# bornhack_stoplicht_ws2812_smd_405_cap_r1.net
KiCad netlist of a schematic drawn in EAGLE
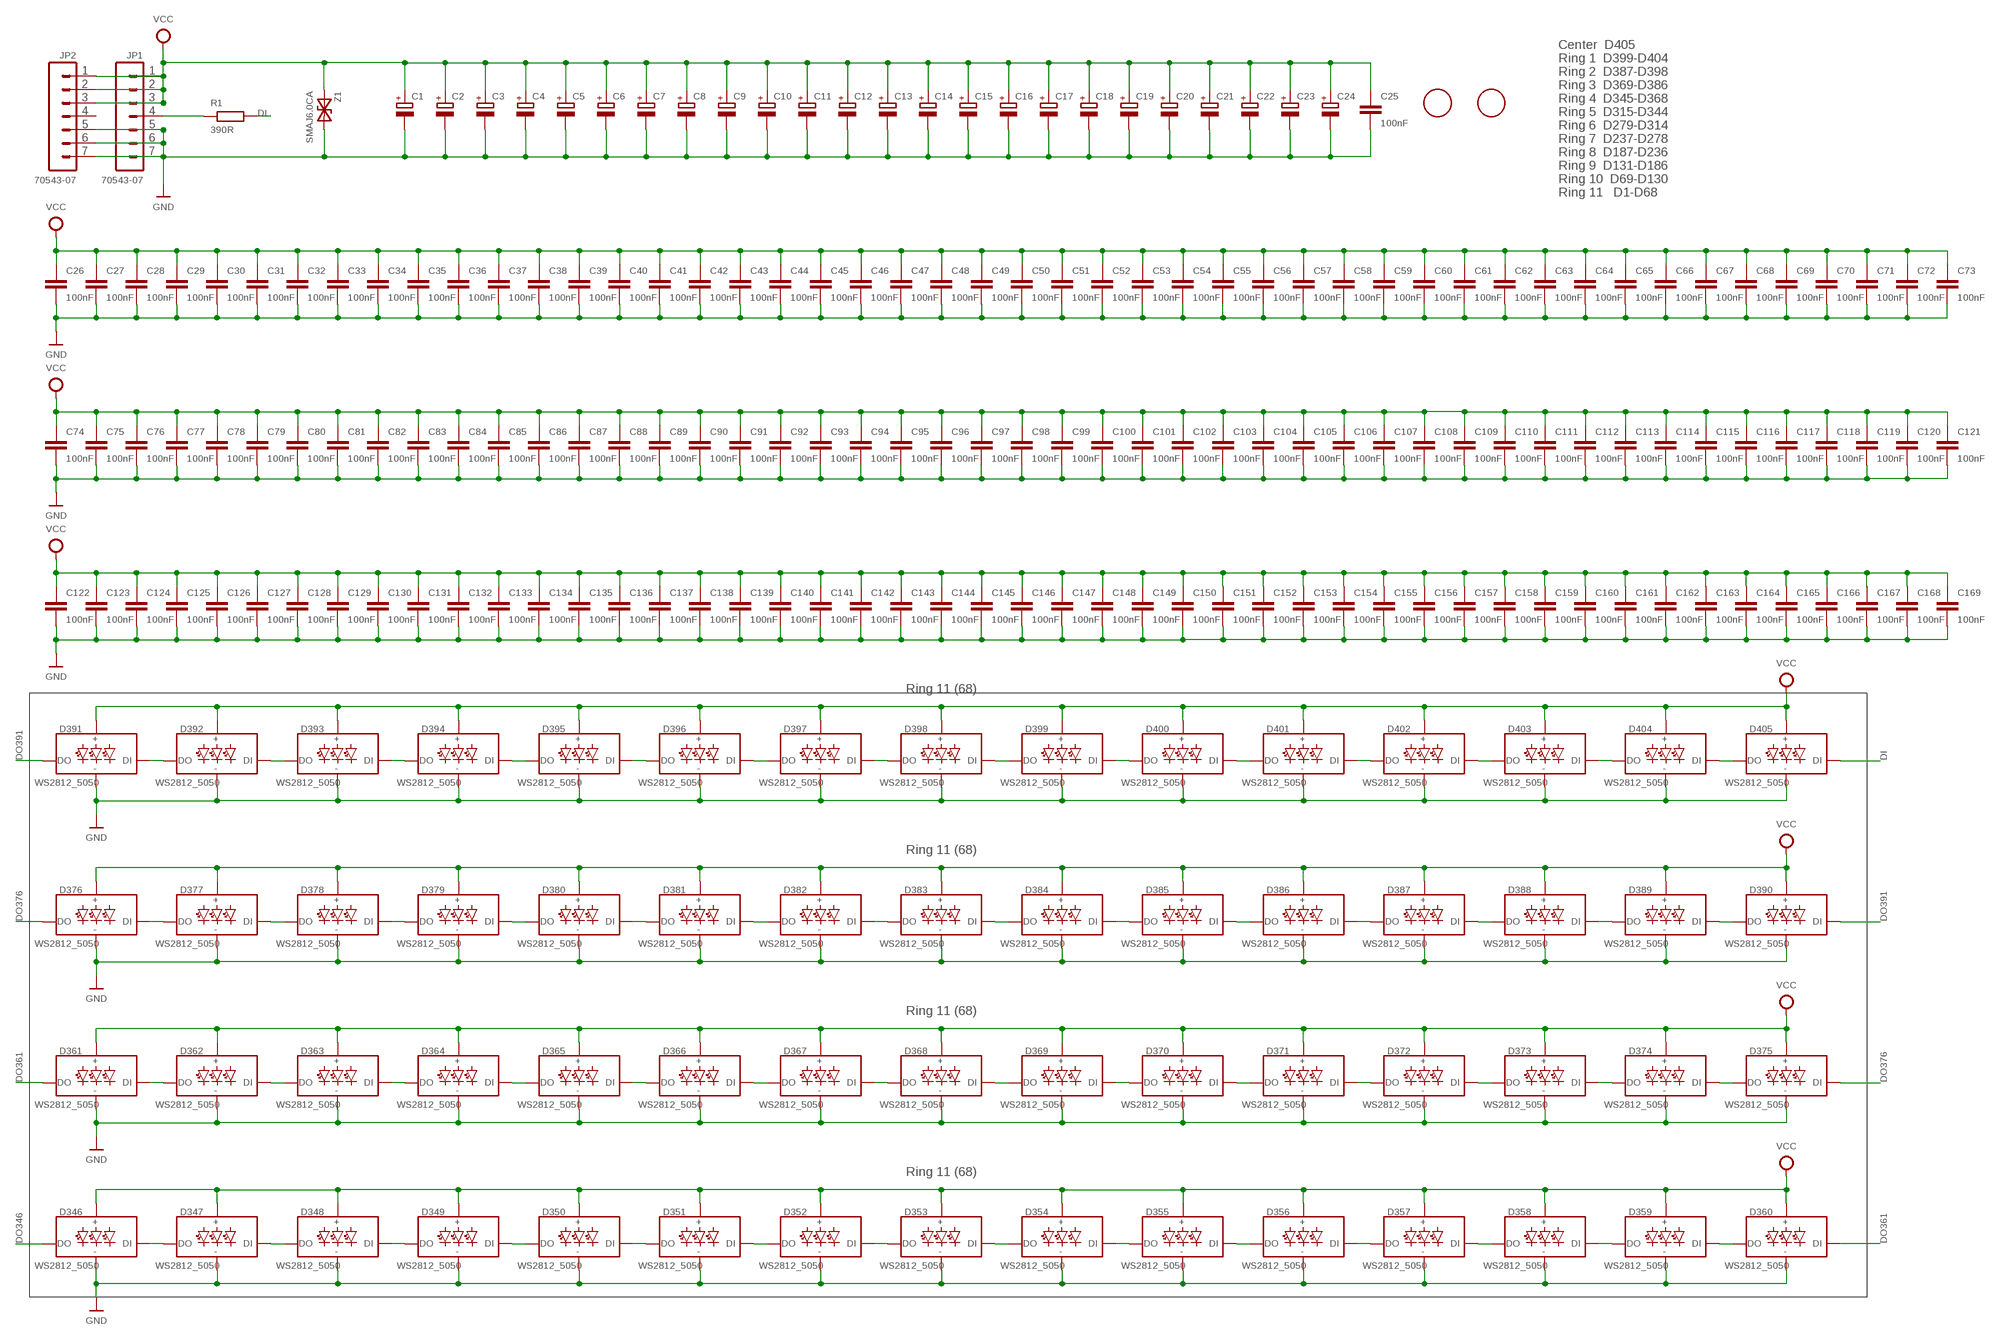
[diagram p0: schematic, sheet 1]
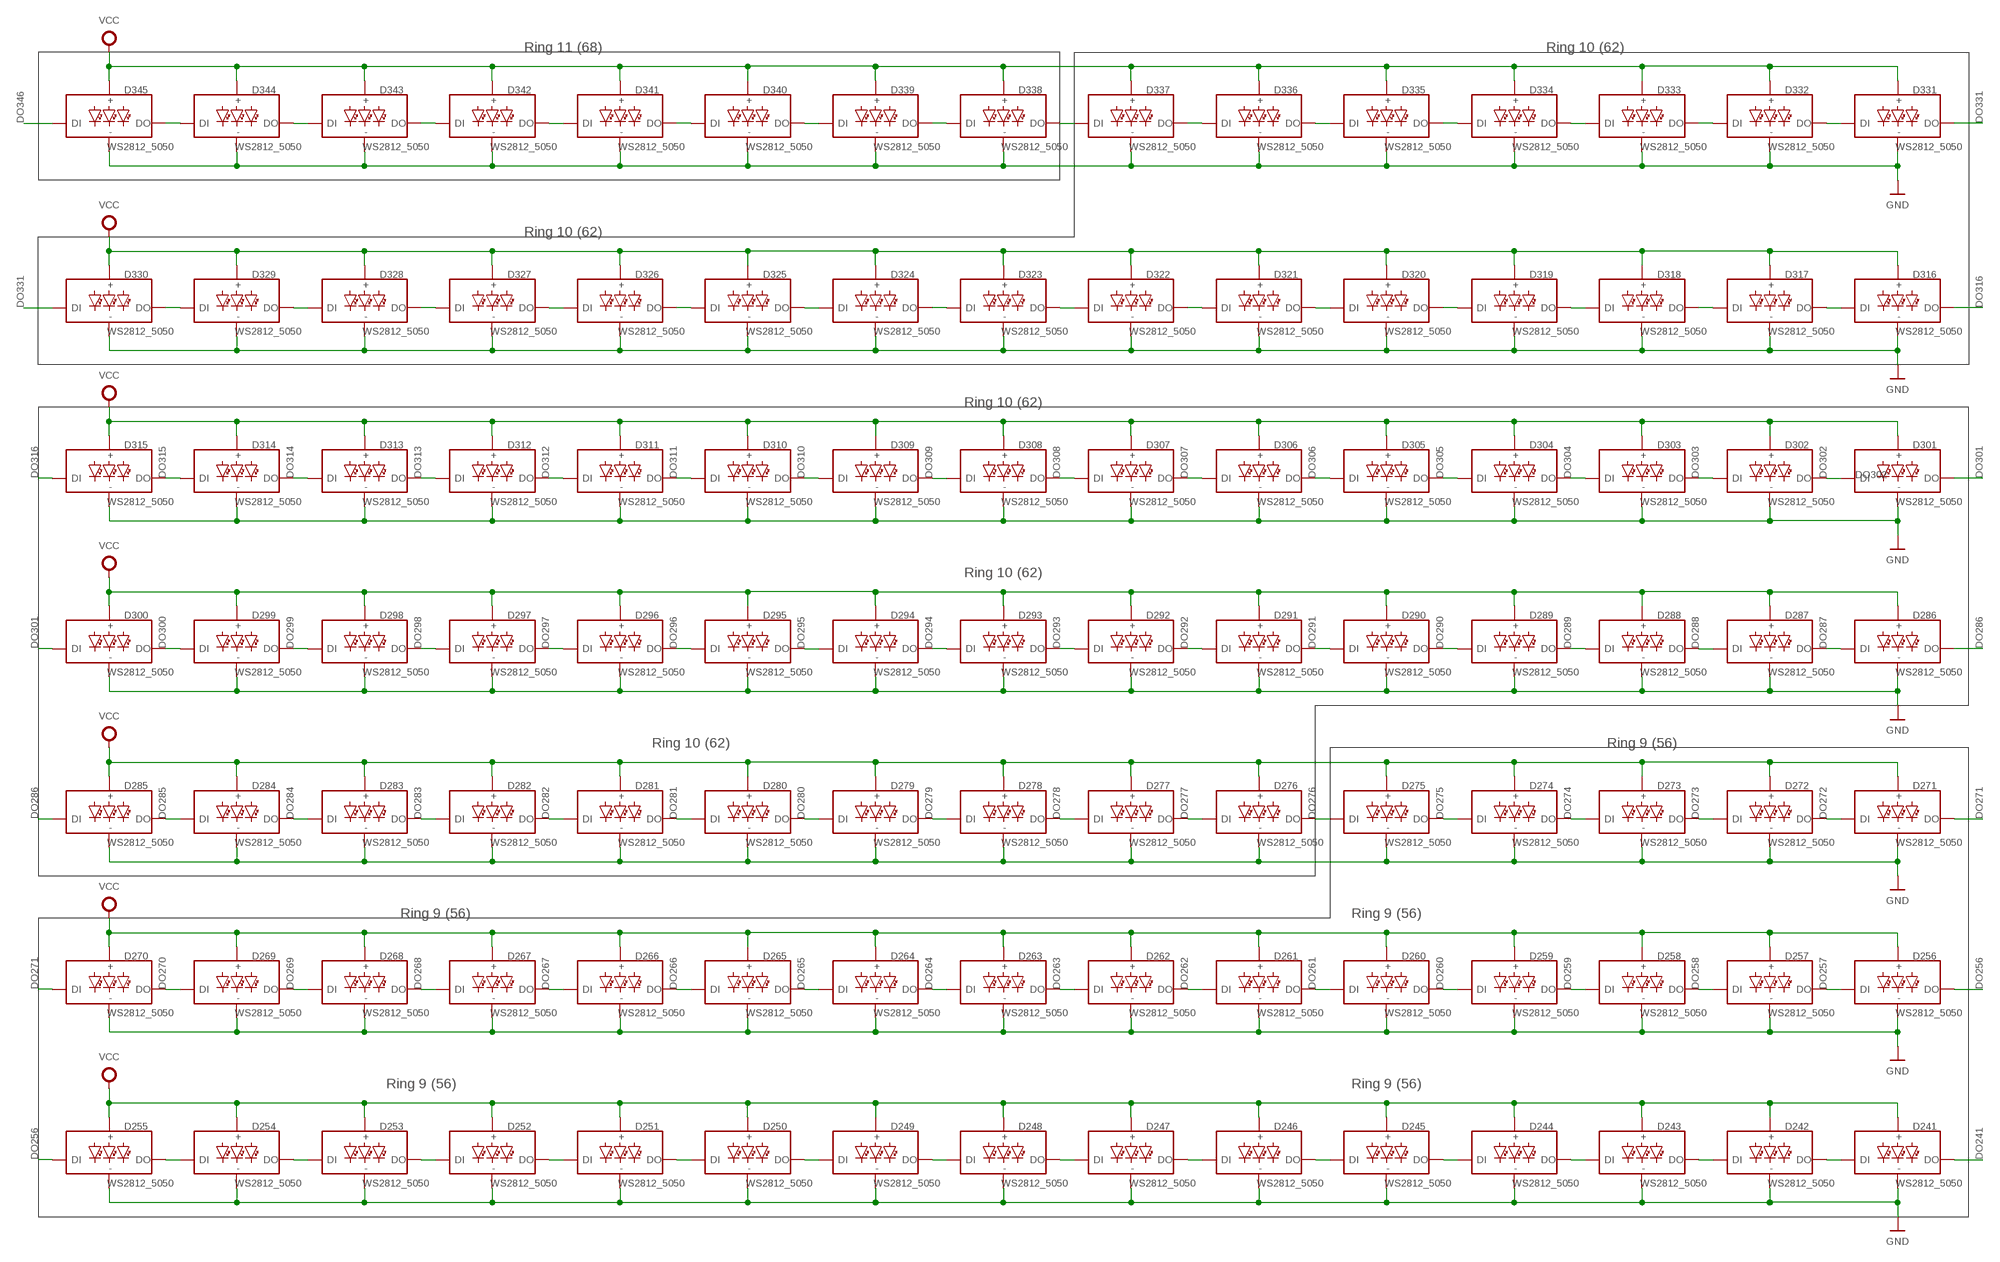
[diagram p1: schematic, sheet 2]
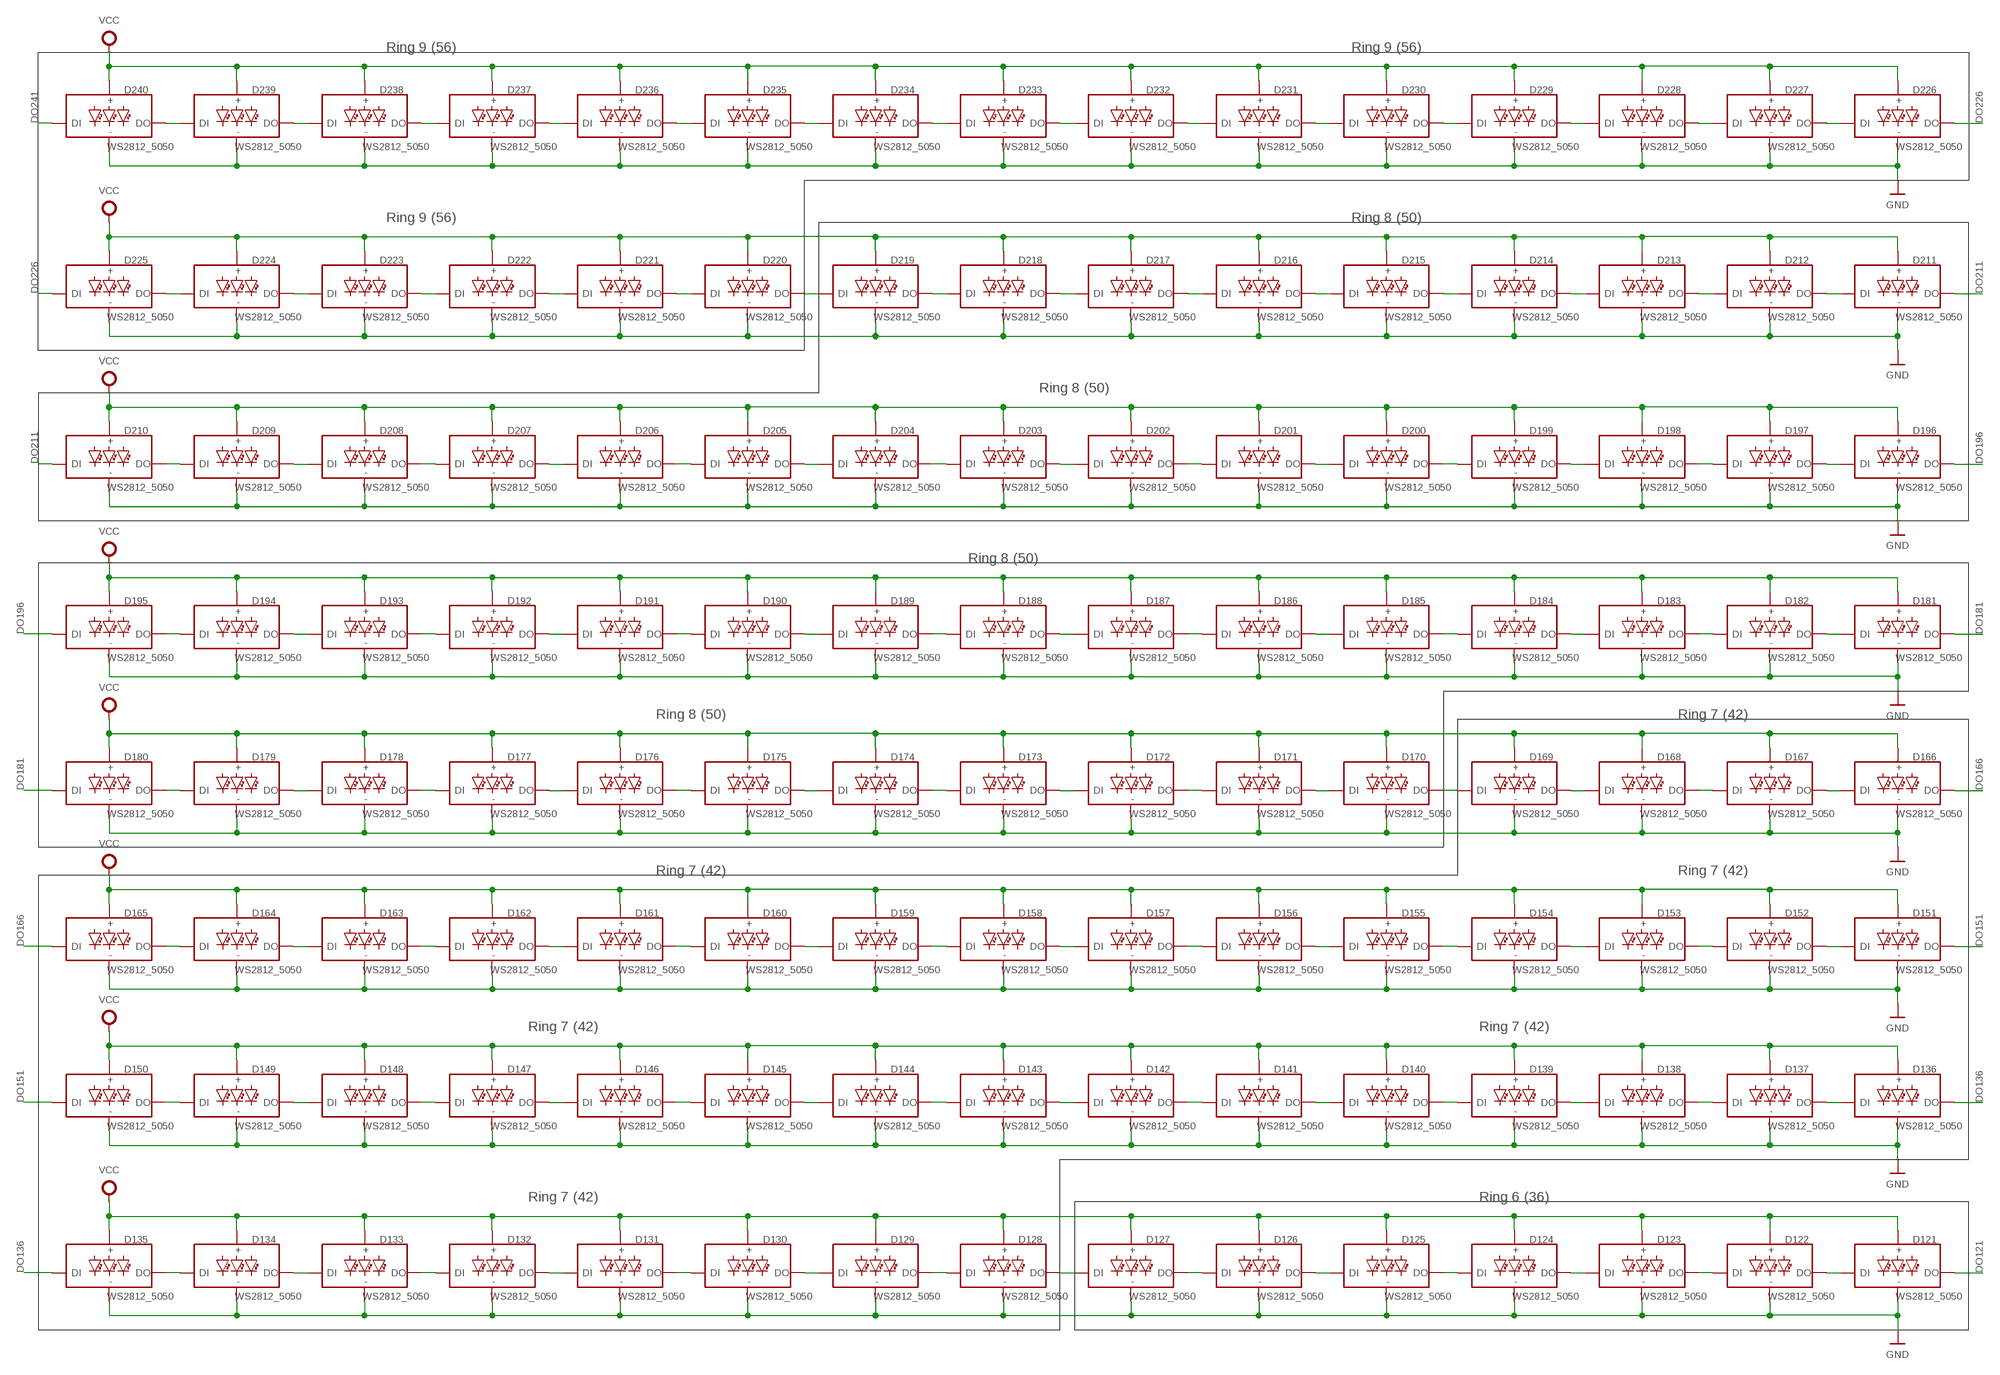
[diagram p2: schematic, sheet 3]
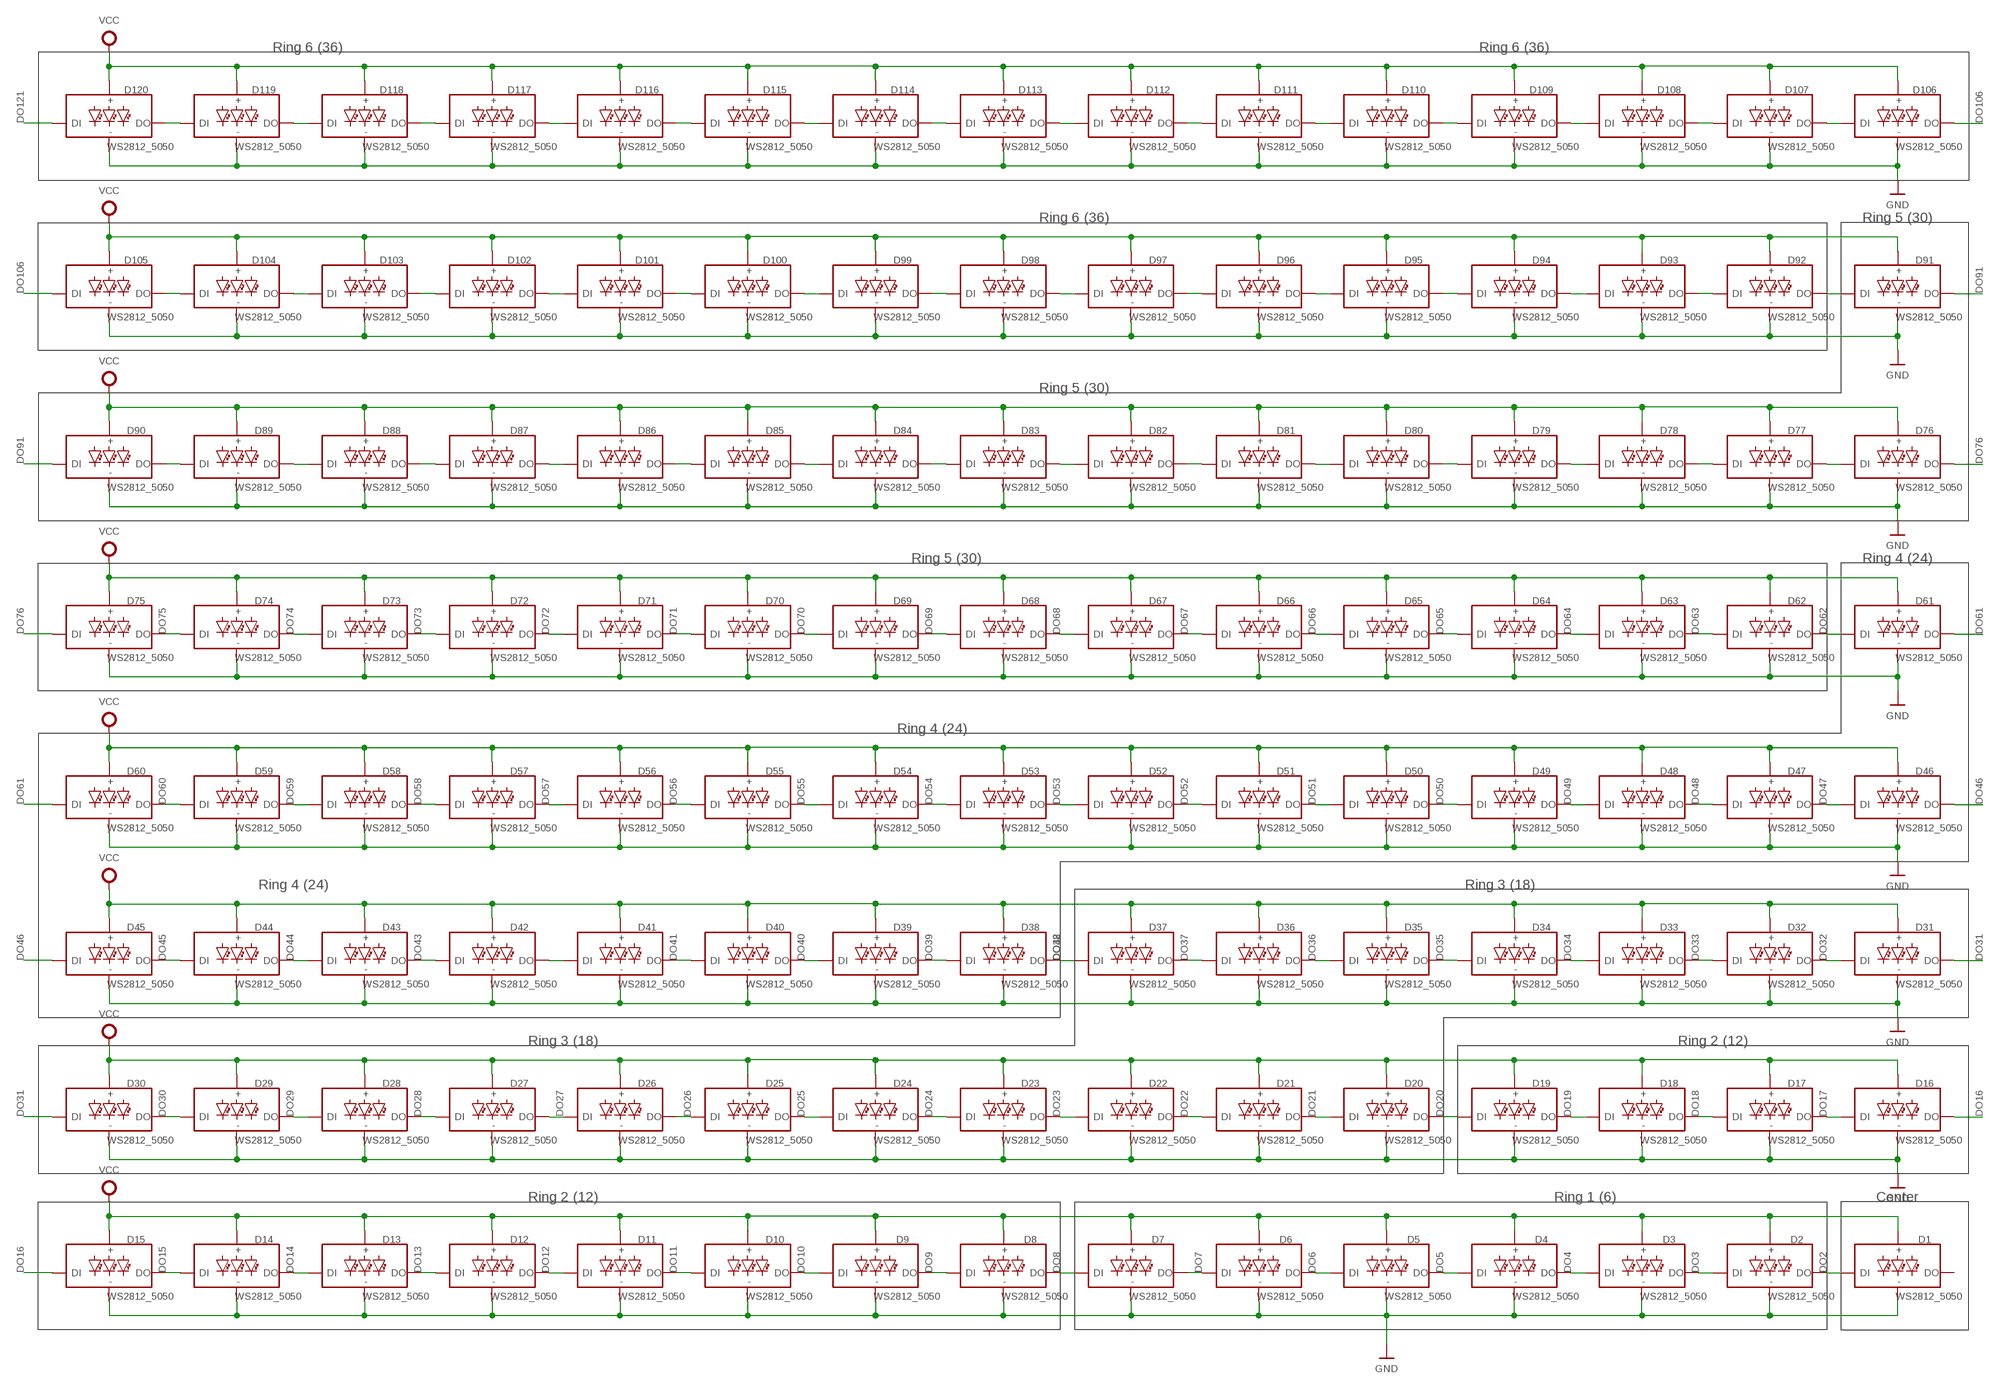
[diagram p3: schematic, sheet 4]

(export (version "E")
  (design (tool "Eeschema 10.0.6"))
  (components
    (comp (ref "C1")
      (value "CPOL-EUE2.5-6")
      (footprint "eagle-import:E2,5-6")
      (libsource (lib "eagle-import") (part "CPOL-EUE2.5-6"))
    )
    (comp (ref "C2")
      (value "CPOL-EUE2.5-6")
      (footprint "eagle-import:E2,5-6")
      (libsource (lib "eagle-import") (part "CPOL-EUE2.5-6"))
    )
    (comp (ref "C3")
      (value "CPOL-EUE2.5-6")
      (footprint "eagle-import:E2,5-6")
      (libsource (lib "eagle-import") (part "CPOL-EUE2.5-6"))
    )
    (comp (ref "C4")
      (value "CPOL-EUE2.5-6")
      (footprint "eagle-import:E2,5-6")
      (libsource (lib "eagle-import") (part "CPOL-EUE2.5-6"))
    )
    (comp (ref "C5")
      (value "CPOL-EUE2.5-6")
      (footprint "eagle-import:E2,5-6")
      (libsource (lib "eagle-import") (part "CPOL-EUE2.5-6"))
    )
    (comp (ref "C6")
      (value "CPOL-EUE2.5-6")
      (footprint "eagle-import:E2,5-6")
      (libsource (lib "eagle-import") (part "CPOL-EUE2.5-6"))
    )
    (comp (ref "C7")
      (value "CPOL-EUE2.5-6")
      (footprint "eagle-import:E2,5-6")
      (libsource (lib "eagle-import") (part "CPOL-EUE2.5-6"))
    )
    (comp (ref "C8")
      (value "CPOL-EUE2.5-6")
      (footprint "eagle-import:E2,5-6")
      (libsource (lib "eagle-import") (part "CPOL-EUE2.5-6"))
    )
    (comp (ref "C9")
      (value "CPOL-EUE2.5-6")
      (footprint "eagle-import:E2,5-6")
      (libsource (lib "eagle-import") (part "CPOL-EUE2.5-6"))
    )
    (comp (ref "C10")
      (value "CPOL-EUE2.5-6")
      (footprint "eagle-import:E2,5-6")
      (libsource (lib "eagle-import") (part "CPOL-EUE2.5-6"))
    )
    (comp (ref "C11")
      (value "CPOL-EUE2.5-6")
      (footprint "eagle-import:E2,5-6")
      (libsource (lib "eagle-import") (part "CPOL-EUE2.5-6"))
    )
    (comp (ref "C12")
      (value "CPOL-EUE2.5-6")
      (footprint "eagle-import:E2,5-6")
      (libsource (lib "eagle-import") (part "CPOL-EUE2.5-6"))
    )
    (comp (ref "C13")
      (value "CPOL-EUE2.5-6")
      (footprint "eagle-import:E2,5-6")
      (libsource (lib "eagle-import") (part "CPOL-EUE2.5-6"))
    )
    (comp (ref "C14")
      (value "CPOL-EUE2.5-6")
      (footprint "eagle-import:E2,5-6")
      (libsource (lib "eagle-import") (part "CPOL-EUE2.5-6"))
    )
    (comp (ref "C15")
      (value "CPOL-EUE2.5-6")
      (footprint "eagle-import:E2,5-6")
      (libsource (lib "eagle-import") (part "CPOL-EUE2.5-6"))
    )
    (comp (ref "C16")
      (value "CPOL-EUE2.5-6")
      (footprint "eagle-import:E2,5-6")
      (libsource (lib "eagle-import") (part "CPOL-EUE2.5-6"))
    )
    (comp (ref "C17")
      (value "CPOL-EUE2.5-6")
      (footprint "eagle-import:E2,5-6")
      (libsource (lib "eagle-import") (part "CPOL-EUE2.5-6"))
    )
    (comp (ref "C18")
      (value "CPOL-EUE2.5-6")
      (footprint "eagle-import:E2,5-6")
      (libsource (lib "eagle-import") (part "CPOL-EUE2.5-6"))
    )
    (comp (ref "C19")
      (value "CPOL-EUE2.5-6")
      (footprint "eagle-import:E2,5-6")
      (libsource (lib "eagle-import") (part "CPOL-EUE2.5-6"))
    )
    (comp (ref "C20")
      (value "CPOL-EUE2.5-6")
      (footprint "eagle-import:E2,5-6")
      (libsource (lib "eagle-import") (part "CPOL-EUE2.5-6"))
    )
    (comp (ref "C21")
      (value "CPOL-EUE2.5-6")
      (footprint "eagle-import:E2,5-6")
      (libsource (lib "eagle-import") (part "CPOL-EUE2.5-6"))
    )
    (comp (ref "C22")
      (value "CPOL-EUE2.5-6")
      (footprint "eagle-import:E2,5-6")
      (libsource (lib "eagle-import") (part "CPOL-EUE2.5-6"))
    )
    (comp (ref "C23")
      (value "CPOL-EUE2.5-6")
      (footprint "eagle-import:E2,5-6")
      (libsource (lib "eagle-import") (part "CPOL-EUE2.5-6"))
    )
    (comp (ref "C24")
      (value "CPOL-EUE2.5-6")
      (footprint "eagle-import:E2,5-6")
      (libsource (lib "eagle-import") (part "CPOL-EUE2.5-6"))
    )
    (comp (ref "C25")
      (value "100nF")
      (footprint "eagle-import:C0603K")
      (libsource (lib "eagle-import") (part "C-EUC0603K"))
    )
    (comp (ref "C26")
      (value "100nF")
      (footprint "eagle-import:C0603K")
      (libsource (lib "eagle-import") (part "C-EUC0603K"))
    )
    (comp (ref "C27")
      (value "100nF")
      (footprint "eagle-import:C0603K")
      (libsource (lib "eagle-import") (part "C-EUC0603K"))
    )
    (comp (ref "C28")
      (value "100nF")
      (footprint "eagle-import:C0603K")
      (libsource (lib "eagle-import") (part "C-EUC0603K"))
    )
    (comp (ref "C29")
      (value "100nF")
      (footprint "eagle-import:C0603K")
      (libsource (lib "eagle-import") (part "C-EUC0603K"))
    )
    (comp (ref "C30")
      (value "100nF")
      (footprint "eagle-import:C0603K")
      (libsource (lib "eagle-import") (part "C-EUC0603K"))
    )
    (comp (ref "C31")
      (value "100nF")
      (footprint "eagle-import:C0603K")
      (libsource (lib "eagle-import") (part "C-EUC0603K"))
    )
    (comp (ref "C32")
      (value "100nF")
      (footprint "eagle-import:C0603K")
      (libsource (lib "eagle-import") (part "C-EUC0603K"))
    )
    (comp (ref "C33")
      (value "100nF")
      (footprint "eagle-import:C0603K")
      (libsource (lib "eagle-import") (part "C-EUC0603K"))
    )
    (comp (ref "C34")
      (value "100nF")
      (footprint "eagle-import:C0603K")
      (libsource (lib "eagle-import") (part "C-EUC0603K"))
    )
    (comp (ref "C35")
      (value "100nF")
      (footprint "eagle-import:C0603K")
      (libsource (lib "eagle-import") (part "C-EUC0603K"))
    )
    (comp (ref "C36")
      (value "100nF")
      (footprint "eagle-import:C0603K")
      (libsource (lib "eagle-import") (part "C-EUC0603K"))
    )
    (comp (ref "C37")
      (value "100nF")
      (footprint "eagle-import:C0603K")
      (libsource (lib "eagle-import") (part "C-EUC0603K"))
    )
    (comp (ref "C38")
      (value "100nF")
      (footprint "eagle-import:C0603K")
      (libsource (lib "eagle-import") (part "C-EUC0603K"))
    )
    (comp (ref "C39")
      (value "100nF")
      (footprint "eagle-import:C0603K")
      (libsource (lib "eagle-import") (part "C-EUC0603K"))
    )
    (comp (ref "C40")
      (value "100nF")
      (footprint "eagle-import:C0603K")
      (libsource (lib "eagle-import") (part "C-EUC0603K"))
    )
    (comp (ref "C41")
      (value "100nF")
      (footprint "eagle-import:C0603K")
      (libsource (lib "eagle-import") (part "C-EUC0603K"))
    )
    (comp (ref "C42")
      (value "100nF")
      (footprint "eagle-import:C0603K")
      (libsource (lib "eagle-import") (part "C-EUC0603K"))
    )
    (comp (ref "C43")
      (value "100nF")
      (footprint "eagle-import:C0603K")
      (libsource (lib "eagle-import") (part "C-EUC0603K"))
    )
    (comp (ref "C44")
      (value "100nF")
      (footprint "eagle-import:C0603K")
      (libsource (lib "eagle-import") (part "C-EUC0603K"))
    )
    (comp (ref "C45")
      (value "100nF")
      (footprint "eagle-import:C0603K")
      (libsource (lib "eagle-import") (part "C-EUC0603K"))
    )
    (comp (ref "C46")
      (value "100nF")
      (footprint "eagle-import:C0603K")
      (libsource (lib "eagle-import") (part "C-EUC0603K"))
    )
    (comp (ref "C47")
      (value "100nF")
      (footprint "eagle-import:C0603K")
      (libsource (lib "eagle-import") (part "C-EUC0603K"))
    )
    (comp (ref "C48")
      (value "100nF")
      (footprint "eagle-import:C0603K")
      (libsource (lib "eagle-import") (part "C-EUC0603K"))
    )
    (comp (ref "C49")
      (value "100nF")
      (footprint "eagle-import:C0603K")
      (libsource (lib "eagle-import") (part "C-EUC0603K"))
    )
    (comp (ref "C50")
      (value "100nF")
      (footprint "eagle-import:C0603K")
      (libsource (lib "eagle-import") (part "C-EUC0603K"))
    )
    (comp (ref "C51")
      (value "100nF")
      (footprint "eagle-import:C0603K")
      (libsource (lib "eagle-import") (part "C-EUC0603K"))
    )
    (comp (ref "C52")
      (value "100nF")
      (footprint "eagle-import:C0603K")
      (libsource (lib "eagle-import") (part "C-EUC0603K"))
    )
    (comp (ref "C53")
      (value "100nF")
      (footprint "eagle-import:C0603K")
      (libsource (lib "eagle-import") (part "C-EUC0603K"))
    )
    (comp (ref "C54")
      (value "100nF")
      (footprint "eagle-import:C0603K")
      (libsource (lib "eagle-import") (part "C-EUC0603K"))
    )
    (comp (ref "C55")
      (value "100nF")
      (footprint "eagle-import:C0603K")
      (libsource (lib "eagle-import") (part "C-EUC0603K"))
    )
    (comp (ref "C56")
      (value "100nF")
      (footprint "eagle-import:C0603K")
      (libsource (lib "eagle-import") (part "C-EUC0603K"))
    )
    (comp (ref "C57")
      (value "100nF")
      (footprint "eagle-import:C0603K")
      (libsource (lib "eagle-import") (part "C-EUC0603K"))
    )
    (comp (ref "C58")
      (value "100nF")
      (footprint "eagle-import:C0603K")
      (libsource (lib "eagle-import") (part "C-EUC0603K"))
    )
    (comp (ref "C59")
      (value "100nF")
      (footprint "eagle-import:C0603K")
      (libsource (lib "eagle-import") (part "C-EUC0603K"))
    )
    (comp (ref "C60")
      (value "100nF")
      (footprint "eagle-import:C0603K")
      (libsource (lib "eagle-import") (part "C-EUC0603K"))
    )
    (comp (ref "C61")
      (value "100nF")
      (footprint "eagle-import:C0603K")
      (libsource (lib "eagle-import") (part "C-EUC0603K"))
    )
    (comp (ref "C62")
      (value "100nF")
      (footprint "eagle-import:C0603K")
      (libsource (lib "eagle-import") (part "C-EUC0603K"))
    )
    (comp (ref "C63")
      (value "100nF")
      (footprint "eagle-import:C0603K")
      (libsource (lib "eagle-import") (part "C-EUC0603K"))
    )
    (comp (ref "C64")
      (value "100nF")
      (footprint "eagle-import:C0603K")
      (libsource (lib "eagle-import") (part "C-EUC0603K"))
    )
    (comp (ref "C65")
      (value "100nF")
      (footprint "eagle-import:C0603K")
      (libsource (lib "eagle-import") (part "C-EUC0603K"))
    )
    (comp (ref "C66")
      (value "100nF")
      (footprint "eagle-import:C0603K")
      (libsource (lib "eagle-import") (part "C-EUC0603K"))
    )
    (comp (ref "C67")
      (value "100nF")
      (footprint "eagle-import:C0603K")
      (libsource (lib "eagle-import") (part "C-EUC0603K"))
    )
    (comp (ref "C68")
      (value "100nF")
      (footprint "eagle-import:C0603K")
      (libsource (lib "eagle-import") (part "C-EUC0603K"))
    )
    (comp (ref "C69")
      (value "100nF")
      (footprint "eagle-import:C0603K")
      (libsource (lib "eagle-import") (part "C-EUC0603K"))
    )
    (comp (ref "C70")
      (value "100nF")
      (footprint "eagle-import:C0603K")
      (libsource (lib "eagle-import") (part "C-EUC0603K"))
    )
    (comp (ref "C71")
      (value "100nF")
      (footprint "eagle-import:C0603K")
      (libsource (lib "eagle-import") (part "C-EUC0603K"))
    )
    (comp (ref "C72")
      (value "100nF")
      (footprint "eagle-import:C0603K")
      (libsource (lib "eagle-import") (part "C-EUC0603K"))
    )
    (comp (ref "C73")
      (value "100nF")
      (footprint "eagle-import:C0603K")
      (libsource (lib "eagle-import") (part "C-EUC0603K"))
    )
    (comp (ref "C74")
      (value "100nF")
      (footprint "eagle-import:C0603K")
      (libsource (lib "eagle-import") (part "C-EUC0603K"))
    )
    (comp (ref "C75")
      (value "100nF")
      (footprint "eagle-import:C0603K")
      (libsource (lib "eagle-import") (part "C-EUC0603K"))
    )
    (comp (ref "C76")
      (value "100nF")
      (footprint "eagle-import:C0603K")
      (libsource (lib "eagle-import") (part "C-EUC0603K"))
    )
    (comp (ref "C77")
      (value "100nF")
      (footprint "eagle-import:C0603K")
      (libsource (lib "eagle-import") (part "C-EUC0603K"))
    )
    (comp (ref "C78")
      (value "100nF")
      (footprint "eagle-import:C0603K")
      (libsource (lib "eagle-import") (part "C-EUC0603K"))
    )
    (comp (ref "C79")
      (value "100nF")
      (footprint "eagle-import:C0603K")
      (libsource (lib "eagle-import") (part "C-EUC0603K"))
    )
    (comp (ref "C80")
      (value "100nF")
      (footprint "eagle-import:C0603K")
      (libsource (lib "eagle-import") (part "C-EUC0603K"))
    )
    (comp (ref "C81")
      (value "100nF")
      (footprint "eagle-import:C0603K")
      (libsource (lib "eagle-import") (part "C-EUC0603K"))
    )
    (comp (ref "C82")
      (value "100nF")
      (footprint "eagle-import:C0603K")
      (libsource (lib "eagle-import") (part "C-EUC0603K"))
    )
    (comp (ref "C83")
      (value "100nF")
      (footprint "eagle-import:C0603K")
      (libsource (lib "eagle-import") (part "C-EUC0603K"))
    )
    (comp (ref "C84")
      (value "100nF")
      (footprint "eagle-import:C0603K")
      (libsource (lib "eagle-import") (part "C-EUC0603K"))
    )
    (comp (ref "C85")
      (value "100nF")
      (footprint "eagle-import:C0603K")
      (libsource (lib "eagle-import") (part "C-EUC0603K"))
    )
    (comp (ref "C86")
      (value "100nF")
      (footprint "eagle-import:C0603K")
      (libsource (lib "eagle-import") (part "C-EUC0603K"))
    )
    (comp (ref "C87")
      (value "100nF")
      (footprint "eagle-import:C0603K")
      (libsource (lib "eagle-import") (part "C-EUC0603K"))
    )
    (comp (ref "C88")
      (value "100nF")
      (footprint "eagle-import:C0603K")
      (libsource (lib "eagle-import") (part "C-EUC0603K"))
    )
    (comp (ref "C89")
      (value "100nF")
      (footprint "eagle-import:C0603K")
      (libsource (lib "eagle-import") (part "C-EUC0603K"))
    )
    (comp (ref "C90")
      (value "100nF")
      (footprint "eagle-import:C0603K")
      (libsource (lib "eagle-import") (part "C-EUC0603K"))
    )
    (comp (ref "C91")
      (value "100nF")
      (footprint "eagle-import:C0603K")
      (libsource (lib "eagle-import") (part "C-EUC0603K"))
    )
    (comp (ref "C92")
      (value "100nF")
      (footprint "eagle-import:C0603K")
      (libsource (lib "eagle-import") (part "C-EUC0603K"))
    )
    (comp (ref "C93")
      (value "100nF")
      (footprint "eagle-import:C0603K")
      (libsource (lib "eagle-import") (part "C-EUC0603K"))
    )
    (comp (ref "C94")
      (value "100nF")
      (footprint "eagle-import:C0603K")
      (libsource (lib "eagle-import") (part "C-EUC0603K"))
    )
    (comp (ref "C95")
      (value "100nF")
      (footprint "eagle-import:C0603K")
      (libsource (lib "eagle-import") (part "C-EUC0603K"))
    )
    (comp (ref "C96")
      (value "100nF")
      (footprint "eagle-import:C0603K")
      (libsource (lib "eagle-import") (part "C-EUC0603K"))
    )
    (comp (ref "C97")
      (value "100nF")
      (footprint "eagle-import:C0603K")
      (libsource (lib "eagle-import") (part "C-EUC0603K"))
    )
    (comp (ref "C98")
      (value "100nF")
      (footprint "eagle-import:C0603K")
      (libsource (lib "eagle-import") (part "C-EUC0603K"))
    )
    (comp (ref "C99")
      (value "100nF")
      (footprint "eagle-import:C0603K")
      (libsource (lib "eagle-import") (part "C-EUC0603K"))
    )
    (comp (ref "C100")
      (value "100nF")
      (footprint "eagle-import:C0603K")
      (libsource (lib "eagle-import") (part "C-EUC0603K"))
    )
    (comp (ref "C101")
      (value "100nF")
      (footprint "eagle-import:C0603K")
      (libsource (lib "eagle-import") (part "C-EUC0603K"))
    )
    (comp (ref "C102")
      (value "100nF")
      (footprint "eagle-import:C0603K")
      (libsource (lib "eagle-import") (part "C-EUC0603K"))
    )
    (comp (ref "C103")
      (value "100nF")
      (footprint "eagle-import:C0603K")
      (libsource (lib "eagle-import") (part "C-EUC0603K"))
    )
    (comp (ref "C104")
      (value "100nF")
      (footprint "eagle-import:C0603K")
      (libsource (lib "eagle-import") (part "C-EUC0603K"))
    )
    (comp (ref "C105")
      (value "100nF")
      (footprint "eagle-import:C0603K")
      (libsource (lib "eagle-import") (part "C-EUC0603K"))
    )
    (comp (ref "C106")
      (value "100nF")
      (footprint "eagle-import:C0603K")
      (libsource (lib "eagle-import") (part "C-EUC0603K"))
    )
    (comp (ref "C107")
      (value "100nF")
      (footprint "eagle-import:C0603K")
      (libsource (lib "eagle-import") (part "C-EUC0603K"))
    )
    (comp (ref "C108")
      (value "100nF")
      (footprint "eagle-import:C0603K")
      (libsource (lib "eagle-import") (part "C-EUC0603K"))
    )
    (comp (ref "C109")
      (value "100nF")
      (footprint "eagle-import:C0603K")
      (libsource (lib "eagle-import") (part "C-EUC0603K"))
    )
    (comp (ref "C110")
      (value "100nF")
      (footprint "eagle-import:C0603K")
      (libsource (lib "eagle-import") (part "C-EUC0603K"))
    )
    (comp (ref "C111")
      (value "100nF")
      (footprint "eagle-import:C0603K")
      (libsource (lib "eagle-import") (part "C-EUC0603K"))
    )
    (comp (ref "C112")
      (value "100nF")
      (footprint "eagle-import:C0603K")
      (libsource (lib "eagle-import") (part "C-EUC0603K"))
    )
    (comp (ref "C113")
      (value "100nF")
      (footprint "eagle-import:C0603K")
      (libsource (lib "eagle-import") (part "C-EUC0603K"))
    )
    (comp (ref "C114")
      (value "100nF")
      (footprint "eagle-import:C0603K")
      (libsource (lib "eagle-import") (part "C-EUC0603K"))
    )
    (comp (ref "C115")
      (value "100nF")
      (footprint "eagle-import:C0603K")
      (libsource (lib "eagle-import") (part "C-EUC0603K"))
    )
    (comp (ref "C116")
      (value "100nF")
      (footprint "eagle-import:C0603K")
      (libsource (lib "eagle-import") (part "C-EUC0603K"))
    )
    (comp (ref "C117")
      (value "100nF")
      (footprint "eagle-import:C0603K")
      (libsource (lib "eagle-import") (part "C-EUC0603K"))
    )
    (comp (ref "C118")
      (value "100nF")
      (footprint "eagle-import:C0603K")
      (libsource (lib "eagle-import") (part "C-EUC0603K"))
    )
    (comp (ref "C119")
      (value "100nF")
      (footprint "eagle-import:C0603K")
      (libsource (lib "eagle-import") (part "C-EUC0603K"))
    )
    (comp (ref "C120")
      (value "100nF")
      (footprint "eagle-import:C0603K")
      (libsource (lib "eagle-import") (part "C-EUC0603K"))
    )
    (comp (ref "C121")
      (value "100nF")
      (footprint "eagle-import:C0603K")
      (libsource (lib "eagle-import") (part "C-EUC0603K"))
    )
    (comp (ref "C122")
      (value "100nF")
      (footprint "eagle-import:C0603K")
      (libsource (lib "eagle-import") (part "C-EUC0603K"))
    )
    (comp (ref "C123")
      (value "100nF")
      (footprint "eagle-import:C0603K")
      (libsource (lib "eagle-import") (part "C-EUC0603K"))
    )
    (comp (ref "C124")
      (value "100nF")
      (footprint "eagle-import:C0603K")
      (libsource (lib "eagle-import") (part "C-EUC0603K"))
    )
    (comp (ref "C125")
      (value "100nF")
      (footprint "eagle-import:C0603K")
      (libsource (lib "eagle-import") (part "C-EUC0603K"))
    )
    (comp (ref "C126")
      (value "100nF")
      (footprint "eagle-import:C0603K")
      (libsource (lib "eagle-import") (part "C-EUC0603K"))
    )
    (comp (ref "C127")
      (value "100nF")
      (footprint "eagle-import:C0603K")
      (libsource (lib "eagle-import") (part "C-EUC0603K"))
    )
    (comp (ref "C128")
      (value "100nF")
      (footprint "eagle-import:C0603K")
      (libsource (lib "eagle-import") (part "C-EUC0603K"))
    )
    (comp (ref "C129")
      (value "100nF")
      (footprint "eagle-import:C0603K")
      (libsource (lib "eagle-import") (part "C-EUC0603K"))
    )
    (comp (ref "C130")
      (value "100nF")
      (footprint "eagle-import:C0603K")
      (libsource (lib "eagle-import") (part "C-EUC0603K"))
    )
    (comp (ref "C131")
      (value "100nF")
      (footprint "eagle-import:C0603K")
      (libsource (lib "eagle-import") (part "C-EUC0603K"))
    )
    (comp (ref "C132")
      (value "100nF")
      (footprint "eagle-import:C0603K")
      (libsource (lib "eagle-import") (part "C-EUC0603K"))
    )
    (comp (ref "C133")
      (value "100nF")
      (footprint "eagle-import:C0603K")
      (libsource (lib "eagle-import") (part "C-EUC0603K"))
    )
    (comp (ref "C134")
      (value "100nF")
      (footprint "eagle-import:C0603K")
      (libsource (lib "eagle-import") (part "C-EUC0603K"))
    )
    (comp (ref "C135")
      (value "100nF")
      (footprint "eagle-import:C0603K")
      (libsource (lib "eagle-import") (part "C-EUC0603K"))
    )
    (comp (ref "C136")
      (value "100nF")
      (footprint "eagle-import:C0603K")
      (libsource (lib "eagle-import") (part "C-EUC0603K"))
    )
    (comp (ref "C137")
      (value "100nF")
      (footprint "eagle-import:C0603K")
      (libsource (lib "eagle-import") (part "C-EUC0603K"))
    )
    (comp (ref "C138")
      (value "100nF")
      (footprint "eagle-import:C0603K")
      (libsource (lib "eagle-import") (part "C-EUC0603K"))
    )
    (comp (ref "C139")
      (value "100nF")
      (footprint "eagle-import:C0603K")
      (libsource (lib "eagle-import") (part "C-EUC0603K"))
    )
    (comp (ref "C140")
      (value "100nF")
      (footprint "eagle-import:C0603K")
      (libsource (lib "eagle-import") (part "C-EUC0603K"))
    )
    (comp (ref "C141")
      (value "100nF")
      (footprint "eagle-import:C0603K")
      (libsource (lib "eagle-import") (part "C-EUC0603K"))
    )
    (comp (ref "C142")
      (value "100nF")
      (footprint "eagle-import:C0603K")
      (libsource (lib "eagle-import") (part "C-EUC0603K"))
    )
    (comp (ref "C143")
      (value "100nF")
      (footprint "eagle-import:C0603K")
      (libsource (lib "eagle-import") (part "C-EUC0603K"))
    )
    (comp (ref "C144")
      (value "100nF")
      (footprint "eagle-import:C0603K")
      (libsource (lib "eagle-import") (part "C-EUC0603K"))
    )
    (comp (ref "C145")
      (value "100nF")
      (footprint "eagle-import:C0603K")
      (libsource (lib "eagle-import") (part "C-EUC0603K"))
    )
    (comp (ref "C146")
      (value "100nF")
      (footprint "eagle-import:C0603K")
      (libsource (lib "eagle-import") (part "C-EUC0603K"))
    )
    (comp (ref "C147")
      (value "100nF")
      (footprint "eagle-import:C0603K")
      (libsource (lib "eagle-import") (part "C-EUC0603K"))
    )
    (comp (ref "C148")
      (value "100nF")
      (footprint "eagle-import:C0603K")
      (libsource (lib "eagle-import") (part "C-EUC0603K"))
    )
    (comp (ref "C149")
      (value "100nF")
      (footprint "eagle-import:C0603K")
      (libsource (lib "eagle-import") (part "C-EUC0603K"))
    )
    (comp (ref "C150")
      (value "100nF")
      (footprint "eagle-import:C0603K")
      (libsource (lib "eagle-import") (part "C-EUC0603K"))
    )
    (comp (ref "C151")
      (value "100nF")
      (footprint "eagle-import:C0603K")
      (libsource (lib "eagle-import") (part "C-EUC0603K"))
    )
    (comp (ref "C152")
      (value "100nF")
      (footprint "eagle-import:C0603K")
      (libsource (lib "eagle-import") (part "C-EUC0603K"))
    )
    (comp (ref "C153")
      (value "100nF")
      (footprint "eagle-import:C0603K")
      (libsource (lib "eagle-import") (part "C-EUC0603K"))
    )
    (comp (ref "C154")
      (value "100nF")
      (footprint "eagle-import:C0603K")
      (libsource (lib "eagle-import") (part "C-EUC0603K"))
    )
    (comp (ref "C155")
      (value "100nF")
      (footprint "eagle-import:C0603K")
      (libsource (lib "eagle-import") (part "C-EUC0603K"))
    )
    (comp (ref "C156")
      (value "100nF")
      (footprint "eagle-import:C0603K")
      (libsource (lib "eagle-import") (part "C-EUC0603K"))
    )
    (comp (ref "C157")
      (value "100nF")
      (footprint "eagle-import:C0603K")
      (libsource (lib "eagle-import") (part "C-EUC0603K"))
    )
    (comp (ref "C158")
      (value "100nF")
      (footprint "eagle-import:C0603K")
      (libsource (lib "eagle-import") (part "C-EUC0603K"))
    )
    (comp (ref "C159")
      (value "100nF")
      (footprint "eagle-import:C0603K")
      (libsource (lib "eagle-import") (part "C-EUC0603K"))
    )
    (comp (ref "C160")
      (value "100nF")
      (footprint "eagle-import:C0603K")
      (libsource (lib "eagle-import") (part "C-EUC0603K"))
    )
    (comp (ref "C161")
      (value "100nF")
      (footprint "eagle-import:C0603K")
      (libsource (lib "eagle-import") (part "C-EUC0603K"))
    )
    (comp (ref "C162")
      (value "100nF")
      (footprint "eagle-import:C0603K")
      (libsource (lib "eagle-import") (part "C-EUC0603K"))
    )
    (comp (ref "C163")
      (value "100nF")
      (footprint "eagle-import:C0603K")
      (libsource (lib "eagle-import") (part "C-EUC0603K"))
    )
    (comp (ref "C164")
      (value "100nF")
      (footprint "eagle-import:C0603K")
      (libsource (lib "eagle-import") (part "C-EUC0603K"))
    )
    (comp (ref "C165")
      (value "100nF")
      (footprint "eagle-import:C0603K")
      (libsource (lib "eagle-import") (part "C-EUC0603K"))
    )
    (comp (ref "C166")
      (value "100nF")
      (footprint "eagle-import:C0603K")
      (libsource (lib "eagle-import") (part "C-EUC0603K"))
    )
    (comp (ref "C167")
      (value "100nF")
      (footprint "eagle-import:C0603K")
      (libsource (lib "eagle-import") (part "C-EUC0603K"))
    )
    (comp (ref "C168")
      (value "100nF")
      (footprint "eagle-import:C0603K")
      (libsource (lib "eagle-import") (part "C-EUC0603K"))
    )
    (comp (ref "C169")
      (value "100nF")
      (footprint "eagle-import:C0603K")
      (libsource (lib "eagle-import") (part "C-EUC0603K"))
    )
    (comp (ref "D346")
      (value "WS2812_5050")
      (footprint "eagle-import:WS2812-5X5-4PIN")
      (libsource (lib "eagle-import") (part "led-rs_WS2812_5050"))
    )
    (comp (ref "D347")
      (value "WS2812_5050")
      (footprint "eagle-import:WS2812-5X5-4PIN")
      (libsource (lib "eagle-import") (part "led-rs_WS2812_5050"))
    )
    (comp (ref "D348")
      (value "WS2812_5050")
      (footprint "eagle-import:WS2812-5X5-4PIN")
      (libsource (lib "eagle-import") (part "led-rs_WS2812_5050"))
    )
    (comp (ref "D349")
      (value "WS2812_5050")
      (footprint "eagle-import:WS2812-5X5-4PIN")
      (libsource (lib "eagle-import") (part "led-rs_WS2812_5050"))
    )
    (comp (ref "D350")
      (value "WS2812_5050")
      (footprint "eagle-import:WS2812-5X5-4PIN")
      (libsource (lib "eagle-import") (part "led-rs_WS2812_5050"))
    )
    (comp (ref "D351")
      (value "WS2812_5050")
      (footprint "eagle-import:WS2812-5X5-4PIN")
      (libsource (lib "eagle-import") (part "led-rs_WS2812_5050"))
    )
    (comp (ref "D352")
      (value "WS2812_5050")
      (footprint "eagle-import:WS2812-5X5-4PIN")
      (libsource (lib "eagle-import") (part "led-rs_WS2812_5050"))
    )
    (comp (ref "D353")
      (value "WS2812_5050")
      (footprint "eagle-import:WS2812-5X5-4PIN")
      (libsource (lib "eagle-import") (part "led-rs_WS2812_5050"))
    )
    (comp (ref "D354")
      (value "WS2812_5050")
      (footprint "eagle-import:WS2812-5X5-4PIN")
      (libsource (lib "eagle-import") (part "led-rs_WS2812_5050"))
    )
    (comp (ref "D355")
      (value "WS2812_5050")
      (footprint "eagle-import:WS2812-5X5-4PIN")
      (libsource (lib "eagle-import") (part "led-rs_WS2812_5050"))
    )
    (comp (ref "D356")
      (value "WS2812_5050")
      (footprint "eagle-import:WS2812-5X5-4PIN")
      (libsource (lib "eagle-import") (part "led-rs_WS2812_5050"))
    )
    (comp (ref "D357")
      (value "WS2812_5050")
      (footprint "eagle-import:WS2812-5X5-4PIN")
      (libsource (lib "eagle-import") (part "led-rs_WS2812_5050"))
    )
    (comp (ref "D358")
      (value "WS2812_5050")
      (footprint "eagle-import:WS2812-5X5-4PIN")
      (libsource (lib "eagle-import") (part "led-rs_WS2812_5050"))
    )
    (comp (ref "D359")
      (value "WS2812_5050")
      (footprint "eagle-import:WS2812-5X5-4PIN")
      (libsource (lib "eagle-import") (part "led-rs_WS2812_5050"))
    )
    (comp (ref "D360")
      (value "WS2812_5050")
      (footprint "eagle-import:WS2812-5X5-4PIN")
      (libsource (lib "eagle-import") (part "led-rs_WS2812_5050"))
    )
    (comp (ref "D361")
      (value "WS2812_5050")
      (footprint "eagle-import:WS2812-5X5-4PIN")
      (libsource (lib "eagle-import") (part "led-rs_WS2812_5050"))
    )
    (comp (ref "D362")
      (value "WS2812_5050")
      (footprint "eagle-import:WS2812-5X5-4PIN")
      (libsource (lib "eagle-import") (part "led-rs_WS2812_5050"))
    )
    (comp (ref "D363")
      (value "WS2812_5050")
      (footprint "eagle-import:WS2812-5X5-4PIN")
      (libsource (lib "eagle-import") (part "led-rs_WS2812_5050"))
    )
    (comp (ref "D364")
      (value "WS2812_5050")
      (footprint "eagle-import:WS2812-5X5-4PIN")
      (libsource (lib "eagle-import") (part "led-rs_WS2812_5050"))
    )
    (comp (ref "D365")
      (value "WS2812_5050")
      (footprint "eagle-import:WS2812-5X5-4PIN")
      (libsource (lib "eagle-import") (part "led-rs_WS2812_5050"))
    )
    (comp (ref "D366")
      (value "WS2812_5050")
      (footprint "eagle-import:WS2812-5X5-4PIN")
      (libsource (lib "eagle-import") (part "led-rs_WS2812_5050"))
    )
    (comp (ref "D367")
      (value "WS2812_5050")
      (footprint "eagle-import:WS2812-5X5-4PIN")
      (libsource (lib "eagle-import") (part "led-rs_WS2812_5050"))
    )
    (comp (ref "D368")
      (value "WS2812_5050")
      (footprint "eagle-import:WS2812-5X5-4PIN")
      (libsource (lib "eagle-import") (part "led-rs_WS2812_5050"))
    )
    (comp (ref "D369")
      (value "WS2812_5050")
      (footprint "eagle-import:WS2812-5X5-4PIN")
      (libsource (lib "eagle-import") (part "led-rs_WS2812_5050"))
    )
    (comp (ref "D370")
      (value "WS2812_5050")
      (footprint "eagle-import:WS2812-5X5-4PIN")
      (libsource (lib "eagle-import") (part "led-rs_WS2812_5050"))
    )
    (comp (ref "D371")
      (value "WS2812_5050")
      (footprint "eagle-import:WS2812-5X5-4PIN")
      (libsource (lib "eagle-import") (part "led-rs_WS2812_5050"))
    )
    (comp (ref "D372")
      (value "WS2812_5050")
      (footprint "eagle-import:WS2812-5X5-4PIN")
      (libsource (lib "eagle-import") (part "led-rs_WS2812_5050"))
    )
    (comp (ref "D373")
      (value "WS2812_5050")
      (footprint "eagle-import:WS2812-5X5-4PIN")
      (libsource (lib "eagle-import") (part "led-rs_WS2812_5050"))
    )
    (comp (ref "D374")
      (value "WS2812_5050")
      (footprint "eagle-import:WS2812-5X5-4PIN")
      (libsource (lib "eagle-import") (part "led-rs_WS2812_5050"))
    )
    (comp (ref "D375")
      (value "WS2812_5050")
      (footprint "eagle-import:WS2812-5X5-4PIN")
      (libsource (lib "eagle-import") (part "led-rs_WS2812_5050"))
    )
    (comp (ref "D376")
      (value "WS2812_5050")
      (footprint "eagle-import:WS2812-5X5-4PIN")
      (libsource (lib "eagle-import") (part "led-rs_WS2812_5050"))
    )
    (comp (ref "D377")
      (value "WS2812_5050")
      (footprint "eagle-import:WS2812-5X5-4PIN")
      (libsource (lib "eagle-import") (part "led-rs_WS2812_5050"))
    )
    (comp (ref "D378")
      (value "WS2812_5050")
      (footprint "eagle-import:WS2812-5X5-4PIN")
      (libsource (lib "eagle-import") (part "led-rs_WS2812_5050"))
    )
    (comp (ref "D379")
      (value "WS2812_5050")
      (footprint "eagle-import:WS2812-5X5-4PIN")
      (libsource (lib "eagle-import") (part "led-rs_WS2812_5050"))
    )
    (comp (ref "D380")
      (value "WS2812_5050")
      (footprint "eagle-import:WS2812-5X5-4PIN")
      (libsource (lib "eagle-import") (part "led-rs_WS2812_5050"))
    )
    (comp (ref "D381")
      (value "WS2812_5050")
      (footprint "eagle-import:WS2812-5X5-4PIN")
      (libsource (lib "eagle-import") (part "led-rs_WS2812_5050"))
    )
    (comp (ref "D382")
      (value "WS2812_5050")
      (footprint "eagle-import:WS2812-5X5-4PIN")
      (libsource (lib "eagle-import") (part "led-rs_WS2812_5050"))
    )
    (comp (ref "D383")
      (value "WS2812_5050")
      (footprint "eagle-import:WS2812-5X5-4PIN")
      (libsource (lib "eagle-import") (part "led-rs_WS2812_5050"))
    )
    (comp (ref "D384")
      (value "WS2812_5050")
      (footprint "eagle-import:WS2812-5X5-4PIN")
      (libsource (lib "eagle-import") (part "led-rs_WS2812_5050"))
    )
    (comp (ref "D385")
      (value "WS2812_5050")
      (footprint "eagle-import:WS2812-5X5-4PIN")
      (libsource (lib "eagle-import") (part "led-rs_WS2812_5050"))
    )
    (comp (ref "D386")
      (value "WS2812_5050")
      (footprint "eagle-import:WS2812-5X5-4PIN")
      (libsource (lib "eagle-import") (part "led-rs_WS2812_5050"))
    )
    (comp (ref "D387")
      (value "WS2812_5050")
      (footprint "eagle-import:WS2812-5X5-4PIN")
      (libsource (lib "eagle-import") (part "led-rs_WS2812_5050"))
    )
    (comp (ref "D388")
      (value "WS2812_5050")
      (footprint "eagle-import:WS2812-5X5-4PIN")
      (libsource (lib "eagle-import") (part "led-rs_WS2812_5050"))
    )
    (comp (ref "D389")
      (value "WS2812_5050")
      (footprint "eagle-import:WS2812-5X5-4PIN")
      (libsource (lib "eagle-import") (part "led-rs_WS2812_5050"))
    )
    (comp (ref "D390")
      (value "WS2812_5050")
      (footprint "eagle-import:WS2812-5X5-4PIN")
      (libsource (lib "eagle-import") (part "led-rs_WS2812_5050"))
    )
    (comp (ref "D391")
      (value "WS2812_5050")
      (footprint "eagle-import:WS2812-5X5-4PIN")
      (libsource (lib "eagle-import") (part "led-rs_WS2812_5050"))
    )
    (comp (ref "D392")
      (value "WS2812_5050")
      (footprint "eagle-import:WS2812-5X5-4PIN")
      (libsource (lib "eagle-import") (part "led-rs_WS2812_5050"))
    )
    (comp (ref "D393")
      (value "WS2812_5050")
      (footprint "eagle-import:WS2812-5X5-4PIN")
      (libsource (lib "eagle-import") (part "led-rs_WS2812_5050"))
    )
    (comp (ref "D394")
      (value "WS2812_5050")
      (footprint "eagle-import:WS2812-5X5-4PIN")
      (libsource (lib "eagle-import") (part "led-rs_WS2812_5050"))
    )
    (comp (ref "D395")
      (value "WS2812_5050")
      (footprint "eagle-import:WS2812-5X5-4PIN")
      (libsource (lib "eagle-import") (part "led-rs_WS2812_5050"))
    )
    (comp (ref "D396")
      (value "WS2812_5050")
      (footprint "eagle-import:WS2812-5X5-4PIN")
      (libsource (lib "eagle-import") (part "led-rs_WS2812_5050"))
    )
    (comp (ref "D397")
      (value "WS2812_5050")
      (footprint "eagle-import:WS2812-5X5-4PIN")
      (libsource (lib "eagle-import") (part "led-rs_WS2812_5050"))
    )
    (comp (ref "D398")
      (value "WS2812_5050")
      (footprint "eagle-import:WS2812-5X5-4PIN")
      (libsource (lib "eagle-import") (part "led-rs_WS2812_5050"))
    )
    (comp (ref "D399")
      (value "WS2812_5050")
      (footprint "eagle-import:WS2812-5X5-4PIN")
      (libsource (lib "eagle-import") (part "led-rs_WS2812_5050"))
    )
    (comp (ref "D400")
      (value "WS2812_5050")
      (footprint "eagle-import:WS2812-5X5-4PIN")
      (libsource (lib "eagle-import") (part "led-rs_WS2812_5050"))
    )
    (comp (ref "D401")
      (value "WS2812_5050")
      (footprint "eagle-import:WS2812-5X5-4PIN")
      (libsource (lib "eagle-import") (part "led-rs_WS2812_5050"))
    )
    (comp (ref "D402")
      (value "WS2812_5050")
      (footprint "eagle-import:WS2812-5X5-4PIN")
      (libsource (lib "eagle-import") (part "led-rs_WS2812_5050"))
    )
    (comp (ref "D403")
      (value "WS2812_5050")
      (footprint "eagle-import:WS2812-5X5-4PIN")
      (libsource (lib "eagle-import") (part "led-rs_WS2812_5050"))
    )
    (comp (ref "D404")
      (value "WS2812_5050")
      (footprint "eagle-import:WS2812-5X5-4PIN")
      (libsource (lib "eagle-import") (part "led-rs_WS2812_5050"))
    )
    (comp (ref "D405")
      (value "WS2812_5050")
      (footprint "eagle-import:WS2812-5X5-4PIN")
      (libsource (lib "eagle-import") (part "led-rs_WS2812_5050"))
    )
    (comp (ref "JP1")
      (value "70543-07")
      (footprint "eagle-import:70543-07")
      (libsource (lib "eagle-import") (part "70543-07"))
    )
    (comp (ref "JP2")
      (value "70543-07")
      (footprint "eagle-import:70543-07")
      (libsource (lib "eagle-import") (part "70543-07"))
    )
    (comp (ref "R1")
      (value "390R")
      (footprint "eagle-import:R0805")
      (libsource (lib "eagle-import") (part "R-EUR0805"))
    )
    (comp (ref "U2")
      (value "FIDUCIAL")
      (footprint "eagle-import:FIDUCIAL_1MM")
      (libsource (lib "eagle-import") (part "FIDUCIAL"))
    )
    (comp (ref "U4")
      (value "FIDUCIAL")
      (footprint "eagle-import:FIDUCIAL_1MM")
      (libsource (lib "eagle-import") (part "FIDUCIAL"))
    )
    (comp (ref "Z1")
      (value "SMAJ6.0CA")
      (footprint "eagle-import:DO214AC")
      (libsource (lib "eagle-import") (part "SMAJCA6.0"))
    )
    (comp (ref "D241")
      (value "WS2812_5050")
      (footprint "eagle-import:WS2812-5X5-4PIN")
      (libsource (lib "eagle-import") (part "led-rs_WS2812_5050"))
    )
    (comp (ref "D242")
      (value "WS2812_5050")
      (footprint "eagle-import:WS2812-5X5-4PIN")
      (libsource (lib "eagle-import") (part "led-rs_WS2812_5050"))
    )
    (comp (ref "D243")
      (value "WS2812_5050")
      (footprint "eagle-import:WS2812-5X5-4PIN")
      (libsource (lib "eagle-import") (part "led-rs_WS2812_5050"))
    )
    (comp (ref "D244")
      (value "WS2812_5050")
      (footprint "eagle-import:WS2812-5X5-4PIN")
      (libsource (lib "eagle-import") (part "led-rs_WS2812_5050"))
    )
    (comp (ref "D245")
      (value "WS2812_5050")
      (footprint "eagle-import:WS2812-5X5-4PIN")
      (libsource (lib "eagle-import") (part "led-rs_WS2812_5050"))
    )
    (comp (ref "D246")
      (value "WS2812_5050")
      (footprint "eagle-import:WS2812-5X5-4PIN")
      (libsource (lib "eagle-import") (part "led-rs_WS2812_5050"))
    )
    (comp (ref "D247")
      (value "WS2812_5050")
      (footprint "eagle-import:WS2812-5X5-4PIN")
      (libsource (lib "eagle-import") (part "led-rs_WS2812_5050"))
    )
    (comp (ref "D248")
      (value "WS2812_5050")
      (footprint "eagle-import:WS2812-5X5-4PIN")
      (libsource (lib "eagle-import") (part "led-rs_WS2812_5050"))
    )
    (comp (ref "D249")
      (value "WS2812_5050")
      (footprint "eagle-import:WS2812-5X5-4PIN")
      (libsource (lib "eagle-import") (part "led-rs_WS2812_5050"))
    )
    (comp (ref "D250")
      (value "WS2812_5050")
      (footprint "eagle-import:WS2812-5X5-4PIN")
      (libsource (lib "eagle-import") (part "led-rs_WS2812_5050"))
    )
    (comp (ref "D251")
      (value "WS2812_5050")
      (footprint "eagle-import:WS2812-5X5-4PIN")
      (libsource (lib "eagle-import") (part "led-rs_WS2812_5050"))
    )
    (comp (ref "D252")
      (value "WS2812_5050")
      (footprint "eagle-import:WS2812-5X5-4PIN")
      (libsource (lib "eagle-import") (part "led-rs_WS2812_5050"))
    )
    (comp (ref "D253")
      (value "WS2812_5050")
      (footprint "eagle-import:WS2812-5X5-4PIN")
      (libsource (lib "eagle-import") (part "led-rs_WS2812_5050"))
    )
    (comp (ref "D254")
      (value "WS2812_5050")
      (footprint "eagle-import:WS2812-5X5-4PIN")
      (libsource (lib "eagle-import") (part "led-rs_WS2812_5050"))
    )
    (comp (ref "D255")
      (value "WS2812_5050")
      (footprint "eagle-import:WS2812-5X5-4PIN")
      (libsource (lib "eagle-import") (part "led-rs_WS2812_5050"))
    )
    (comp (ref "D256")
      (value "WS2812_5050")
      (footprint "eagle-import:WS2812-5X5-4PIN")
      (libsource (lib "eagle-import") (part "led-rs_WS2812_5050"))
    )
    (comp (ref "D257")
      (value "WS2812_5050")
      (footprint "eagle-import:WS2812-5X5-4PIN")
      (libsource (lib "eagle-import") (part "led-rs_WS2812_5050"))
    )
    (comp (ref "D258")
      (value "WS2812_5050")
      (footprint "eagle-import:WS2812-5X5-4PIN")
      (libsource (lib "eagle-import") (part "led-rs_WS2812_5050"))
    )
    (comp (ref "D259")
      (value "WS2812_5050")
      (footprint "eagle-import:WS2812-5X5-4PIN")
      (libsource (lib "eagle-import") (part "led-rs_WS2812_5050"))
    )
    (comp (ref "D260")
      (value "WS2812_5050")
      (footprint "eagle-import:WS2812-5X5-4PIN")
      (libsource (lib "eagle-import") (part "led-rs_WS2812_5050"))
    )
    (comp (ref "D261")
      (value "WS2812_5050")
      (footprint "eagle-import:WS2812-5X5-4PIN")
      (libsource (lib "eagle-import") (part "led-rs_WS2812_5050"))
    )
    (comp (ref "D262")
      (value "WS2812_5050")
      (footprint "eagle-import:WS2812-5X5-4PIN")
      (libsource (lib "eagle-import") (part "led-rs_WS2812_5050"))
    )
    (comp (ref "D263")
      (value "WS2812_5050")
      (footprint "eagle-import:WS2812-5X5-4PIN")
      (libsource (lib "eagle-import") (part "led-rs_WS2812_5050"))
    )
    (comp (ref "D264")
      (value "WS2812_5050")
      (footprint "eagle-import:WS2812-5X5-4PIN")
      (libsource (lib "eagle-import") (part "led-rs_WS2812_5050"))
    )
    (comp (ref "D265")
      (value "WS2812_5050")
      (footprint "eagle-import:WS2812-5X5-4PIN")
      (libsource (lib "eagle-import") (part "led-rs_WS2812_5050"))
    )
    (comp (ref "D266")
      (value "WS2812_5050")
      (footprint "eagle-import:WS2812-5X5-4PIN")
      (libsource (lib "eagle-import") (part "led-rs_WS2812_5050"))
    )
    (comp (ref "D267")
      (value "WS2812_5050")
      (footprint "eagle-import:WS2812-5X5-4PIN")
      (libsource (lib "eagle-import") (part "led-rs_WS2812_5050"))
    )
    (comp (ref "D268")
      (value "WS2812_5050")
      (footprint "eagle-import:WS2812-5X5-4PIN")
      (libsource (lib "eagle-import") (part "led-rs_WS2812_5050"))
    )
    (comp (ref "D269")
      (value "WS2812_5050")
      (footprint "eagle-import:WS2812-5X5-4PIN")
      (libsource (lib "eagle-import") (part "led-rs_WS2812_5050"))
    )
    (comp (ref "D270")
      (value "WS2812_5050")
      (footprint "eagle-import:WS2812-5X5-4PIN")
      (libsource (lib "eagle-import") (part "led-rs_WS2812_5050"))
    )
    (comp (ref "D271")
      (value "WS2812_5050")
      (footprint "eagle-import:WS2812-5X5-4PIN")
      (libsource (lib "eagle-import") (part "led-rs_WS2812_5050"))
    )
    (comp (ref "D272")
      (value "WS2812_5050")
      (footprint "eagle-import:WS2812-5X5-4PIN")
      (libsource (lib "eagle-import") (part "led-rs_WS2812_5050"))
    )
    (comp (ref "D273")
      (value "WS2812_5050")
      (footprint "eagle-import:WS2812-5X5-4PIN")
      (libsource (lib "eagle-import") (part "led-rs_WS2812_5050"))
    )
    (comp (ref "D274")
      (value "WS2812_5050")
      (footprint "eagle-import:WS2812-5X5-4PIN")
      (libsource (lib "eagle-import") (part "led-rs_WS2812_5050"))
    )
    (comp (ref "D275")
      (value "WS2812_5050")
      (footprint "eagle-import:WS2812-5X5-4PIN")
      (libsource (lib "eagle-import") (part "led-rs_WS2812_5050"))
    )
    (comp (ref "D276")
      (value "WS2812_5050")
      (footprint "eagle-import:WS2812-5X5-4PIN")
      (libsource (lib "eagle-import") (part "led-rs_WS2812_5050"))
    )
    (comp (ref "D277")
      (value "WS2812_5050")
      (footprint "eagle-import:WS2812-5X5-4PIN")
      (libsource (lib "eagle-import") (part "led-rs_WS2812_5050"))
    )
    (comp (ref "D278")
      (value "WS2812_5050")
      (footprint "eagle-import:WS2812-5X5-4PIN")
      (libsource (lib "eagle-import") (part "led-rs_WS2812_5050"))
    )
    (comp (ref "D279")
      (value "WS2812_5050")
      (footprint "eagle-import:WS2812-5X5-4PIN")
      (libsource (lib "eagle-import") (part "led-rs_WS2812_5050"))
    )
    (comp (ref "D280")
      (value "WS2812_5050")
      (footprint "eagle-import:WS2812-5X5-4PIN")
      (libsource (lib "eagle-import") (part "led-rs_WS2812_5050"))
    )
    (comp (ref "D281")
      (value "WS2812_5050")
      (footprint "eagle-import:WS2812-5X5-4PIN")
      (libsource (lib "eagle-import") (part "led-rs_WS2812_5050"))
    )
    (comp (ref "D282")
      (value "WS2812_5050")
      (footprint "eagle-import:WS2812-5X5-4PIN")
      (libsource (lib "eagle-import") (part "led-rs_WS2812_5050"))
    )
    (comp (ref "D283")
      (value "WS2812_5050")
      (footprint "eagle-import:WS2812-5X5-4PIN")
      (libsource (lib "eagle-import") (part "led-rs_WS2812_5050"))
    )
    (comp (ref "D284")
      (value "WS2812_5050")
      (footprint "eagle-import:WS2812-5X5-4PIN")
      (libsource (lib "eagle-import") (part "led-rs_WS2812_5050"))
    )
    (comp (ref "D285")
      (value "WS2812_5050")
      (footprint "eagle-import:WS2812-5X5-4PIN")
      (libsource (lib "eagle-import") (part "led-rs_WS2812_5050"))
    )
    (comp (ref "D286")
      (value "WS2812_5050")
      (footprint "eagle-import:WS2812-5X5-4PIN")
      (libsource (lib "eagle-import") (part "led-rs_WS2812_5050"))
    )
    (comp (ref "D287")
      (value "WS2812_5050")
      (footprint "eagle-import:WS2812-5X5-4PIN")
      (libsource (lib "eagle-import") (part "led-rs_WS2812_5050"))
    )
    (comp (ref "D288")
      (value "WS2812_5050")
      (footprint "eagle-import:WS2812-5X5-4PIN")
      (libsource (lib "eagle-import") (part "led-rs_WS2812_5050"))
    )
    (comp (ref "D289")
      (value "WS2812_5050")
      (footprint "eagle-import:WS2812-5X5-4PIN")
      (libsource (lib "eagle-import") (part "led-rs_WS2812_5050"))
    )
    (comp (ref "D290")
      (value "WS2812_5050")
      (footprint "eagle-import:WS2812-5X5-4PIN")
      (libsource (lib "eagle-import") (part "led-rs_WS2812_5050"))
    )
    (comp (ref "D291")
      (value "WS2812_5050")
      (footprint "eagle-import:WS2812-5X5-4PIN")
      (libsource (lib "eagle-import") (part "led-rs_WS2812_5050"))
    )
    (comp (ref "D292")
      (value "WS2812_5050")
      (footprint "eagle-import:WS2812-5X5-4PIN")
      (libsource (lib "eagle-import") (part "led-rs_WS2812_5050"))
    )
    (comp (ref "D293")
      (value "WS2812_5050")
      (footprint "eagle-import:WS2812-5X5-4PIN")
      (libsource (lib "eagle-import") (part "led-rs_WS2812_5050"))
    )
    (comp (ref "D294")
      (value "WS2812_5050")
      (footprint "eagle-import:WS2812-5X5-4PIN")
      (libsource (lib "eagle-import") (part "led-rs_WS2812_5050"))
    )
    (comp (ref "D295")
      (value "WS2812_5050")
      (footprint "eagle-import:WS2812-5X5-4PIN")
      (libsource (lib "eagle-import") (part "led-rs_WS2812_5050"))
    )
    (comp (ref "D296")
      (value "WS2812_5050")
      (footprint "eagle-import:WS2812-5X5-4PIN")
      (libsource (lib "eagle-import") (part "led-rs_WS2812_5050"))
    )
    (comp (ref "D297")
      (value "WS2812_5050")
      (footprint "eagle-import:WS2812-5X5-4PIN")
      (libsource (lib "eagle-import") (part "led-rs_WS2812_5050"))
    )
    (comp (ref "D298")
      (value "WS2812_5050")
      (footprint "eagle-import:WS2812-5X5-4PIN")
      (libsource (lib "eagle-import") (part "led-rs_WS2812_5050"))
    )
    (comp (ref "D299")
      (value "WS2812_5050")
      (footprint "eagle-import:WS2812-5X5-4PIN")
      (libsource (lib "eagle-import") (part "led-rs_WS2812_5050"))
    )
    (comp (ref "D300")
      (value "WS2812_5050")
      (footprint "eagle-import:WS2812-5X5-4PIN")
      (libsource (lib "eagle-import") (part "led-rs_WS2812_5050"))
    )
    (comp (ref "D301")
      (value "WS2812_5050")
      (footprint "eagle-import:WS2812-5X5-4PIN")
      (libsource (lib "eagle-import") (part "led-rs_WS2812_5050"))
    )
    (comp (ref "D302")
      (value "WS2812_5050")
      (footprint "eagle-import:WS2812-5X5-4PIN")
      (libsource (lib "eagle-import") (part "led-rs_WS2812_5050"))
    )
    (comp (ref "D303")
      (value "WS2812_5050")
      (footprint "eagle-import:WS2812-5X5-4PIN")
      (libsource (lib "eagle-import") (part "led-rs_WS2812_5050"))
    )
    (comp (ref "D304")
      (value "WS2812_5050")
      (footprint "eagle-import:WS2812-5X5-4PIN")
      (libsource (lib "eagle-import") (part "led-rs_WS2812_5050"))
    )
    (comp (ref "D305")
      (value "WS2812_5050")
      (footprint "eagle-import:WS2812-5X5-4PIN")
      (libsource (lib "eagle-import") (part "led-rs_WS2812_5050"))
    )
    (comp (ref "D306")
      (value "WS2812_5050")
      (footprint "eagle-import:WS2812-5X5-4PIN")
      (libsource (lib "eagle-import") (part "led-rs_WS2812_5050"))
    )
    (comp (ref "D307")
      (value "WS2812_5050")
      (footprint "eagle-import:WS2812-5X5-4PIN")
      (libsource (lib "eagle-import") (part "led-rs_WS2812_5050"))
    )
    (comp (ref "D308")
      (value "WS2812_5050")
      (footprint "eagle-import:WS2812-5X5-4PIN")
      (libsource (lib "eagle-import") (part "led-rs_WS2812_5050"))
    )
    (comp (ref "D309")
      (value "WS2812_5050")
      (footprint "eagle-import:WS2812-5X5-4PIN")
      (libsource (lib "eagle-import") (part "led-rs_WS2812_5050"))
    )
    (comp (ref "D310")
      (value "WS2812_5050")
      (footprint "eagle-import:WS2812-5X5-4PIN")
      (libsource (lib "eagle-import") (part "led-rs_WS2812_5050"))
    )
    (comp (ref "D311")
      (value "WS2812_5050")
      (footprint "eagle-import:WS2812-5X5-4PIN")
      (libsource (lib "eagle-import") (part "led-rs_WS2812_5050"))
    )
    (comp (ref "D312")
      (value "WS2812_5050")
      (footprint "eagle-import:WS2812-5X5-4PIN")
      (libsource (lib "eagle-import") (part "led-rs_WS2812_5050"))
    )
    (comp (ref "D313")
      (value "WS2812_5050")
      (footprint "eagle-import:WS2812-5X5-4PIN")
      (libsource (lib "eagle-import") (part "led-rs_WS2812_5050"))
    )
    (comp (ref "D314")
      (value "WS2812_5050")
      (footprint "eagle-import:WS2812-5X5-4PIN")
      (libsource (lib "eagle-import") (part "led-rs_WS2812_5050"))
    )
    (comp (ref "D315")
      (value "WS2812_5050")
      (footprint "eagle-import:WS2812-5X5-4PIN")
      (libsource (lib "eagle-import") (part "led-rs_WS2812_5050"))
    )
    (comp (ref "D316")
      (value "WS2812_5050")
      (footprint "eagle-import:WS2812-5X5-4PIN")
      (libsource (lib "eagle-import") (part "led-rs_WS2812_5050"))
    )
    (comp (ref "D317")
      (value "WS2812_5050")
      (footprint "eagle-import:WS2812-5X5-4PIN")
      (libsource (lib "eagle-import") (part "led-rs_WS2812_5050"))
    )
    (comp (ref "D318")
      (value "WS2812_5050")
      (footprint "eagle-import:WS2812-5X5-4PIN")
      (libsource (lib "eagle-import") (part "led-rs_WS2812_5050"))
    )
    (comp (ref "D319")
      (value "WS2812_5050")
      (footprint "eagle-import:WS2812-5X5-4PIN")
      (libsource (lib "eagle-import") (part "led-rs_WS2812_5050"))
    )
    (comp (ref "D320")
      (value "WS2812_5050")
      (footprint "eagle-import:WS2812-5X5-4PIN")
      (libsource (lib "eagle-import") (part "led-rs_WS2812_5050"))
    )
    (comp (ref "D321")
      (value "WS2812_5050")
      (footprint "eagle-import:WS2812-5X5-4PIN")
      (libsource (lib "eagle-import") (part "led-rs_WS2812_5050"))
    )
    (comp (ref "D322")
      (value "WS2812_5050")
      (footprint "eagle-import:WS2812-5X5-4PIN")
      (libsource (lib "eagle-import") (part "led-rs_WS2812_5050"))
    )
    (comp (ref "D323")
      (value "WS2812_5050")
      (footprint "eagle-import:WS2812-5X5-4PIN")
      (libsource (lib "eagle-import") (part "led-rs_WS2812_5050"))
    )
    (comp (ref "D324")
      (value "WS2812_5050")
      (footprint "eagle-import:WS2812-5X5-4PIN")
      (libsource (lib "eagle-import") (part "led-rs_WS2812_5050"))
    )
    (comp (ref "D325")
      (value "WS2812_5050")
      (footprint "eagle-import:WS2812-5X5-4PIN")
      (libsource (lib "eagle-import") (part "led-rs_WS2812_5050"))
    )
    (comp (ref "D326")
      (value "WS2812_5050")
      (footprint "eagle-import:WS2812-5X5-4PIN")
      (libsource (lib "eagle-import") (part "led-rs_WS2812_5050"))
    )
    (comp (ref "D327")
      (value "WS2812_5050")
      (footprint "eagle-import:WS2812-5X5-4PIN")
      (libsource (lib "eagle-import") (part "led-rs_WS2812_5050"))
    )
    (comp (ref "D328")
      (value "WS2812_5050")
      (footprint "eagle-import:WS2812-5X5-4PIN")
      (libsource (lib "eagle-import") (part "led-rs_WS2812_5050"))
    )
    (comp (ref "D329")
      (value "WS2812_5050")
      (footprint "eagle-import:WS2812-5X5-4PIN")
      (libsource (lib "eagle-import") (part "led-rs_WS2812_5050"))
    )
    (comp (ref "D330")
      (value "WS2812_5050")
      (footprint "eagle-import:WS2812-5X5-4PIN")
      (libsource (lib "eagle-import") (part "led-rs_WS2812_5050"))
    )
    (comp (ref "D331")
      (value "WS2812_5050")
      (footprint "eagle-import:WS2812-5X5-4PIN")
      (libsource (lib "eagle-import") (part "led-rs_WS2812_5050"))
    )
    (comp (ref "D332")
      (value "WS2812_5050")
      (footprint "eagle-import:WS2812-5X5-4PIN")
      (libsource (lib "eagle-import") (part "led-rs_WS2812_5050"))
    )
    (comp (ref "D333")
      (value "WS2812_5050")
      (footprint "eagle-import:WS2812-5X5-4PIN")
      (libsource (lib "eagle-import") (part "led-rs_WS2812_5050"))
    )
    (comp (ref "D334")
      (value "WS2812_5050")
      (footprint "eagle-import:WS2812-5X5-4PIN")
      (libsource (lib "eagle-import") (part "led-rs_WS2812_5050"))
    )
    (comp (ref "D335")
      (value "WS2812_5050")
      (footprint "eagle-import:WS2812-5X5-4PIN")
      (libsource (lib "eagle-import") (part "led-rs_WS2812_5050"))
    )
    (comp (ref "D336")
      (value "WS2812_5050")
      (footprint "eagle-import:WS2812-5X5-4PIN")
      (libsource (lib "eagle-import") (part "led-rs_WS2812_5050"))
    )
    (comp (ref "D337")
      (value "WS2812_5050")
      (footprint "eagle-import:WS2812-5X5-4PIN")
      (libsource (lib "eagle-import") (part "led-rs_WS2812_5050"))
    )
    (comp (ref "D338")
      (value "WS2812_5050")
      (footprint "eagle-import:WS2812-5X5-4PIN")
      (libsource (lib "eagle-import") (part "led-rs_WS2812_5050"))
    )
    (comp (ref "D339")
      (value "WS2812_5050")
      (footprint "eagle-import:WS2812-5X5-4PIN")
      (libsource (lib "eagle-import") (part "led-rs_WS2812_5050"))
    )
    (comp (ref "D340")
      (value "WS2812_5050")
      (footprint "eagle-import:WS2812-5X5-4PIN")
      (libsource (lib "eagle-import") (part "led-rs_WS2812_5050"))
    )
    (comp (ref "D341")
      (value "WS2812_5050")
      (footprint "eagle-import:WS2812-5X5-4PIN")
      (libsource (lib "eagle-import") (part "led-rs_WS2812_5050"))
    )
    (comp (ref "D342")
      (value "WS2812_5050")
      (footprint "eagle-import:WS2812-5X5-4PIN")
      (libsource (lib "eagle-import") (part "led-rs_WS2812_5050"))
    )
    (comp (ref "D343")
      (value "WS2812_5050")
      (footprint "eagle-import:WS2812-5X5-4PIN")
      (libsource (lib "eagle-import") (part "led-rs_WS2812_5050"))
    )
    (comp (ref "D344")
      (value "WS2812_5050")
      (footprint "eagle-import:WS2812-5X5-4PIN")
      (libsource (lib "eagle-import") (part "led-rs_WS2812_5050"))
    )
    (comp (ref "D345")
      (value "WS2812_5050")
      (footprint "eagle-import:WS2812-5X5-4PIN")
      (libsource (lib "eagle-import") (part "led-rs_WS2812_5050"))
    )
    (comp (ref "D121")
      (value "WS2812_5050")
      (footprint "eagle-import:WS2812-5X5-4PIN")
      (libsource (lib "eagle-import") (part "led-rs_WS2812_5050"))
    )
    (comp (ref "D122")
      (value "WS2812_5050")
      (footprint "eagle-import:WS2812-5X5-4PIN")
      (libsource (lib "eagle-import") (part "led-rs_WS2812_5050"))
    )
    (comp (ref "D123")
      (value "WS2812_5050")
      (footprint "eagle-import:WS2812-5X5-4PIN")
      (libsource (lib "eagle-import") (part "led-rs_WS2812_5050"))
    )
    (comp (ref "D124")
      (value "WS2812_5050")
      (footprint "eagle-import:WS2812-5X5-4PIN")
      (libsource (lib "eagle-import") (part "led-rs_WS2812_5050"))
    )
    (comp (ref "D125")
      (value "WS2812_5050")
      (footprint "eagle-import:WS2812-5X5-4PIN")
      (libsource (lib "eagle-import") (part "led-rs_WS2812_5050"))
    )
    (comp (ref "D126")
      (value "WS2812_5050")
      (footprint "eagle-import:WS2812-5X5-4PIN")
      (libsource (lib "eagle-import") (part "led-rs_WS2812_5050"))
    )
    (comp (ref "D127")
      (value "WS2812_5050")
      (footprint "eagle-import:WS2812-5X5-4PIN")
      (libsource (lib "eagle-import") (part "led-rs_WS2812_5050"))
    )
    (comp (ref "D128")
      (value "WS2812_5050")
      (footprint "eagle-import:WS2812-5X5-4PIN")
      (libsource (lib "eagle-import") (part "led-rs_WS2812_5050"))
    )
    (comp (ref "D129")
      (value "WS2812_5050")
      (footprint "eagle-import:WS2812-5X5-4PIN")
      (libsource (lib "eagle-import") (part "led-rs_WS2812_5050"))
    )
    (comp (ref "D130")
      (value "WS2812_5050")
      (footprint "eagle-import:WS2812-5X5-4PIN")
      (libsource (lib "eagle-import") (part "led-rs_WS2812_5050"))
    )
    (comp (ref "D131")
      (value "WS2812_5050")
      (footprint "eagle-import:WS2812-5X5-4PIN")
      (libsource (lib "eagle-import") (part "led-rs_WS2812_5050"))
    )
    (comp (ref "D132")
      (value "WS2812_5050")
      (footprint "eagle-import:WS2812-5X5-4PIN")
      (libsource (lib "eagle-import") (part "led-rs_WS2812_5050"))
    )
    (comp (ref "D133")
      (value "WS2812_5050")
      (footprint "eagle-import:WS2812-5X5-4PIN")
      (libsource (lib "eagle-import") (part "led-rs_WS2812_5050"))
    )
    (comp (ref "D134")
      (value "WS2812_5050")
      (footprint "eagle-import:WS2812-5X5-4PIN")
      (libsource (lib "eagle-import") (part "led-rs_WS2812_5050"))
    )
    (comp (ref "D135")
      (value "WS2812_5050")
      (footprint "eagle-import:WS2812-5X5-4PIN")
      (libsource (lib "eagle-import") (part "led-rs_WS2812_5050"))
    )
    (comp (ref "D136")
      (value "WS2812_5050")
      (footprint "eagle-import:WS2812-5X5-4PIN")
      (libsource (lib "eagle-import") (part "led-rs_WS2812_5050"))
    )
    (comp (ref "D137")
      (value "WS2812_5050")
      (footprint "eagle-import:WS2812-5X5-4PIN")
      (libsource (lib "eagle-import") (part "led-rs_WS2812_5050"))
    )
    (comp (ref "D138")
      (value "WS2812_5050")
      (footprint "eagle-import:WS2812-5X5-4PIN")
      (libsource (lib "eagle-import") (part "led-rs_WS2812_5050"))
    )
    (comp (ref "D139")
      (value "WS2812_5050")
      (footprint "eagle-import:WS2812-5X5-4PIN")
      (libsource (lib "eagle-import") (part "led-rs_WS2812_5050"))
    )
    (comp (ref "D140")
      (value "WS2812_5050")
      (footprint "eagle-import:WS2812-5X5-4PIN")
      (libsource (lib "eagle-import") (part "led-rs_WS2812_5050"))
    )
    (comp (ref "D141")
      (value "WS2812_5050")
      (footprint "eagle-import:WS2812-5X5-4PIN")
      (libsource (lib "eagle-import") (part "led-rs_WS2812_5050"))
    )
    (comp (ref "D142")
      (value "WS2812_5050")
      (footprint "eagle-import:WS2812-5X5-4PIN")
      (libsource (lib "eagle-import") (part "led-rs_WS2812_5050"))
    )
    (comp (ref "D143")
      (value "WS2812_5050")
      (footprint "eagle-import:WS2812-5X5-4PIN")
      (libsource (lib "eagle-import") (part "led-rs_WS2812_5050"))
    )
    (comp (ref "D144")
      (value "WS2812_5050")
      (footprint "eagle-import:WS2812-5X5-4PIN")
      (libsource (lib "eagle-import") (part "led-rs_WS2812_5050"))
    )
    (comp (ref "D145")
      (value "WS2812_5050")
      (footprint "eagle-import:WS2812-5X5-4PIN")
      (libsource (lib "eagle-import") (part "led-rs_WS2812_5050"))
    )
    (comp (ref "D146")
      (value "WS2812_5050")
      (footprint "eagle-import:WS2812-5X5-4PIN")
      (libsource (lib "eagle-import") (part "led-rs_WS2812_5050"))
    )
    (comp (ref "D147")
      (value "WS2812_5050")
      (footprint "eagle-import:WS2812-5X5-4PIN")
      (libsource (lib "eagle-import") (part "led-rs_WS2812_5050"))
    )
    (comp (ref "D148")
      (value "WS2812_5050")
      (footprint "eagle-import:WS2812-5X5-4PIN")
      (libsource (lib "eagle-import") (part "led-rs_WS2812_5050"))
    )
    (comp (ref "D149")
      (value "WS2812_5050")
      (footprint "eagle-import:WS2812-5X5-4PIN")
      (libsource (lib "eagle-import") (part "led-rs_WS2812_5050"))
    )
    (comp (ref "D150")
      (value "WS2812_5050")
      (footprint "eagle-import:WS2812-5X5-4PIN")
      (libsource (lib "eagle-import") (part "led-rs_WS2812_5050"))
    )
    (comp (ref "D151")
      (value "WS2812_5050")
      (footprint "eagle-import:WS2812-5X5-4PIN")
      (libsource (lib "eagle-import") (part "led-rs_WS2812_5050"))
    )
    (comp (ref "D152")
      (value "WS2812_5050")
      (footprint "eagle-import:WS2812-5X5-4PIN")
      (libsource (lib "eagle-import") (part "led-rs_WS2812_5050"))
    )
    (comp (ref "D153")
      (value "WS2812_5050")
      (footprint "eagle-import:WS2812-5X5-4PIN")
      (libsource (lib "eagle-import") (part "led-rs_WS2812_5050"))
    )
    (comp (ref "D154")
      (value "WS2812_5050")
      (footprint "eagle-import:WS2812-5X5-4PIN")
      (libsource (lib "eagle-import") (part "led-rs_WS2812_5050"))
    )
    (comp (ref "D155")
      (value "WS2812_5050")
      (footprint "eagle-import:WS2812-5X5-4PIN")
      (libsource (lib "eagle-import") (part "led-rs_WS2812_5050"))
    )
    (comp (ref "D156")
      (value "WS2812_5050")
      (footprint "eagle-import:WS2812-5X5-4PIN")
      (libsource (lib "eagle-import") (part "led-rs_WS2812_5050"))
    )
    (comp (ref "D157")
      (value "WS2812_5050")
      (footprint "eagle-import:WS2812-5X5-4PIN")
      (libsource (lib "eagle-import") (part "led-rs_WS2812_5050"))
    )
    (comp (ref "D158")
      (value "WS2812_5050")
      (footprint "eagle-import:WS2812-5X5-4PIN")
      (libsource (lib "eagle-import") (part "led-rs_WS2812_5050"))
    )
    (comp (ref "D159")
      (value "WS2812_5050")
      (footprint "eagle-import:WS2812-5X5-4PIN")
      (libsource (lib "eagle-import") (part "led-rs_WS2812_5050"))
    )
    (comp (ref "D160")
      (value "WS2812_5050")
      (footprint "eagle-import:WS2812-5X5-4PIN")
      (libsource (lib "eagle-import") (part "led-rs_WS2812_5050"))
    )
    (comp (ref "D161")
      (value "WS2812_5050")
      (footprint "eagle-import:WS2812-5X5-4PIN")
      (libsource (lib "eagle-import") (part "led-rs_WS2812_5050"))
    )
    (comp (ref "D162")
      (value "WS2812_5050")
      (footprint "eagle-import:WS2812-5X5-4PIN")
      (libsource (lib "eagle-import") (part "led-rs_WS2812_5050"))
    )
    (comp (ref "D163")
      (value "WS2812_5050")
      (footprint "eagle-import:WS2812-5X5-4PIN")
      (libsource (lib "eagle-import") (part "led-rs_WS2812_5050"))
    )
    (comp (ref "D164")
      (value "WS2812_5050")
      (footprint "eagle-import:WS2812-5X5-4PIN")
      (libsource (lib "eagle-import") (part "led-rs_WS2812_5050"))
    )
    (comp (ref "D165")
      (value "WS2812_5050")
      (footprint "eagle-import:WS2812-5X5-4PIN")
      (libsource (lib "eagle-import") (part "led-rs_WS2812_5050"))
    )
    (comp (ref "D166")
      (value "WS2812_5050")
      (footprint "eagle-import:WS2812-5X5-4PIN")
      (libsource (lib "eagle-import") (part "led-rs_WS2812_5050"))
    )
    (comp (ref "D167")
      (value "WS2812_5050")
      (footprint "eagle-import:WS2812-5X5-4PIN")
      (libsource (lib "eagle-import") (part "led-rs_WS2812_5050"))
    )
    (comp (ref "D168")
      (value "WS2812_5050")
      (footprint "eagle-import:WS2812-5X5-4PIN")
      (libsource (lib "eagle-import") (part "led-rs_WS2812_5050"))
    )
    (comp (ref "D169")
      (value "WS2812_5050")
      (footprint "eagle-import:WS2812-5X5-4PIN")
      (libsource (lib "eagle-import") (part "led-rs_WS2812_5050"))
    )
    (comp (ref "D170")
      (value "WS2812_5050")
      (footprint "eagle-import:WS2812-5X5-4PIN")
      (libsource (lib "eagle-import") (part "led-rs_WS2812_5050"))
    )
    (comp (ref "D171")
      (value "WS2812_5050")
      (footprint "eagle-import:WS2812-5X5-4PIN")
      (libsource (lib "eagle-import") (part "led-rs_WS2812_5050"))
    )
    (comp (ref "D172")
      (value "WS2812_5050")
      (footprint "eagle-import:WS2812-5X5-4PIN")
      (libsource (lib "eagle-import") (part "led-rs_WS2812_5050"))
    )
    (comp (ref "D173")
      (value "WS2812_5050")
      (footprint "eagle-import:WS2812-5X5-4PIN")
      (libsource (lib "eagle-import") (part "led-rs_WS2812_5050"))
    )
    (comp (ref "D174")
      (value "WS2812_5050")
      (footprint "eagle-import:WS2812-5X5-4PIN")
      (libsource (lib "eagle-import") (part "led-rs_WS2812_5050"))
    )
    (comp (ref "D175")
      (value "WS2812_5050")
      (footprint "eagle-import:WS2812-5X5-4PIN")
      (libsource (lib "eagle-import") (part "led-rs_WS2812_5050"))
    )
    (comp (ref "D176")
      (value "WS2812_5050")
      (footprint "eagle-import:WS2812-5X5-4PIN")
      (libsource (lib "eagle-import") (part "led-rs_WS2812_5050"))
    )
    (comp (ref "D177")
      (value "WS2812_5050")
      (footprint "eagle-import:WS2812-5X5-4PIN")
      (libsource (lib "eagle-import") (part "led-rs_WS2812_5050"))
    )
    (comp (ref "D178")
      (value "WS2812_5050")
      (footprint "eagle-import:WS2812-5X5-4PIN")
      (libsource (lib "eagle-import") (part "led-rs_WS2812_5050"))
    )
    (comp (ref "D179")
      (value "WS2812_5050")
      (footprint "eagle-import:WS2812-5X5-4PIN")
      (libsource (lib "eagle-import") (part "led-rs_WS2812_5050"))
    )
    (comp (ref "D180")
      (value "WS2812_5050")
      (footprint "eagle-import:WS2812-5X5-4PIN")
      (libsource (lib "eagle-import") (part "led-rs_WS2812_5050"))
    )
    (comp (ref "D181")
      (value "WS2812_5050")
      (footprint "eagle-import:WS2812-5X5-4PIN")
      (libsource (lib "eagle-import") (part "led-rs_WS2812_5050"))
    )
    (comp (ref "D182")
      (value "WS2812_5050")
      (footprint "eagle-import:WS2812-5X5-4PIN")
      (libsource (lib "eagle-import") (part "led-rs_WS2812_5050"))
    )
    (comp (ref "D183")
      (value "WS2812_5050")
      (footprint "eagle-import:WS2812-5X5-4PIN")
      (libsource (lib "eagle-import") (part "led-rs_WS2812_5050"))
    )
    (comp (ref "D184")
      (value "WS2812_5050")
      (footprint "eagle-import:WS2812-5X5-4PIN")
      (libsource (lib "eagle-import") (part "led-rs_WS2812_5050"))
    )
    (comp (ref "D185")
      (value "WS2812_5050")
      (footprint "eagle-import:WS2812-5X5-4PIN")
      (libsource (lib "eagle-import") (part "led-rs_WS2812_5050"))
    )
    (comp (ref "D186")
      (value "WS2812_5050")
      (footprint "eagle-import:WS2812-5X5-4PIN")
      (libsource (lib "eagle-import") (part "led-rs_WS2812_5050"))
    )
    (comp (ref "D187")
      (value "WS2812_5050")
      (footprint "eagle-import:WS2812-5X5-4PIN")
      (libsource (lib "eagle-import") (part "led-rs_WS2812_5050"))
    )
    (comp (ref "D188")
      (value "WS2812_5050")
      (footprint "eagle-import:WS2812-5X5-4PIN")
      (libsource (lib "eagle-import") (part "led-rs_WS2812_5050"))
    )
    (comp (ref "D189")
      (value "WS2812_5050")
      (footprint "eagle-import:WS2812-5X5-4PIN")
      (libsource (lib "eagle-import") (part "led-rs_WS2812_5050"))
    )
    (comp (ref "D190")
      (value "WS2812_5050")
      (footprint "eagle-import:WS2812-5X5-4PIN")
      (libsource (lib "eagle-import") (part "led-rs_WS2812_5050"))
    )
    (comp (ref "D191")
      (value "WS2812_5050")
      (footprint "eagle-import:WS2812-5X5-4PIN")
      (libsource (lib "eagle-import") (part "led-rs_WS2812_5050"))
    )
    (comp (ref "D192")
      (value "WS2812_5050")
      (footprint "eagle-import:WS2812-5X5-4PIN")
      (libsource (lib "eagle-import") (part "led-rs_WS2812_5050"))
    )
    (comp (ref "D193")
      (value "WS2812_5050")
      (footprint "eagle-import:WS2812-5X5-4PIN")
      (libsource (lib "eagle-import") (part "led-rs_WS2812_5050"))
    )
    (comp (ref "D194")
      (value "WS2812_5050")
      (footprint "eagle-import:WS2812-5X5-4PIN")
      (libsource (lib "eagle-import") (part "led-rs_WS2812_5050"))
    )
    (comp (ref "D195")
      (value "WS2812_5050")
      (footprint "eagle-import:WS2812-5X5-4PIN")
      (libsource (lib "eagle-import") (part "led-rs_WS2812_5050"))
    )
    (comp (ref "D196")
      (value "WS2812_5050")
      (footprint "eagle-import:WS2812-5X5-4PIN")
      (libsource (lib "eagle-import") (part "led-rs_WS2812_5050"))
    )
    (comp (ref "D197")
      (value "WS2812_5050")
      (footprint "eagle-import:WS2812-5X5-4PIN")
      (libsource (lib "eagle-import") (part "led-rs_WS2812_5050"))
    )
    (comp (ref "D198")
      (value "WS2812_5050")
      (footprint "eagle-import:WS2812-5X5-4PIN")
      (libsource (lib "eagle-import") (part "led-rs_WS2812_5050"))
    )
    (comp (ref "D199")
      (value "WS2812_5050")
      (footprint "eagle-import:WS2812-5X5-4PIN")
      (libsource (lib "eagle-import") (part "led-rs_WS2812_5050"))
    )
    (comp (ref "D200")
      (value "WS2812_5050")
      (footprint "eagle-import:WS2812-5X5-4PIN")
      (libsource (lib "eagle-import") (part "led-rs_WS2812_5050"))
    )
    (comp (ref "D201")
      (value "WS2812_5050")
      (footprint "eagle-import:WS2812-5X5-4PIN")
      (libsource (lib "eagle-import") (part "led-rs_WS2812_5050"))
    )
    (comp (ref "D202")
      (value "WS2812_5050")
      (footprint "eagle-import:WS2812-5X5-4PIN")
      (libsource (lib "eagle-import") (part "led-rs_WS2812_5050"))
    )
    (comp (ref "D203")
      (value "WS2812_5050")
      (footprint "eagle-import:WS2812-5X5-4PIN")
      (libsource (lib "eagle-import") (part "led-rs_WS2812_5050"))
    )
    (comp (ref "D204")
      (value "WS2812_5050")
      (footprint "eagle-import:WS2812-5X5-4PIN")
      (libsource (lib "eagle-import") (part "led-rs_WS2812_5050"))
    )
    (comp (ref "D205")
      (value "WS2812_5050")
      (footprint "eagle-import:WS2812-5X5-4PIN")
      (libsource (lib "eagle-import") (part "led-rs_WS2812_5050"))
    )
    (comp (ref "D206")
      (value "WS2812_5050")
      (footprint "eagle-import:WS2812-5X5-4PIN")
      (libsource (lib "eagle-import") (part "led-rs_WS2812_5050"))
    )
    (comp (ref "D207")
      (value "WS2812_5050")
      (footprint "eagle-import:WS2812-5X5-4PIN")
      (libsource (lib "eagle-import") (part "led-rs_WS2812_5050"))
    )
    (comp (ref "D208")
      (value "WS2812_5050")
      (footprint "eagle-import:WS2812-5X5-4PIN")
      (libsource (lib "eagle-import") (part "led-rs_WS2812_5050"))
    )
    (comp (ref "D209")
      (value "WS2812_5050")
      (footprint "eagle-import:WS2812-5X5-4PIN")
      (libsource (lib "eagle-import") (part "led-rs_WS2812_5050"))
    )
    (comp (ref "D210")
      (value "WS2812_5050")
      (footprint "eagle-import:WS2812-5X5-4PIN")
      (libsource (lib "eagle-import") (part "led-rs_WS2812_5050"))
    )
    (comp (ref "D211")
      (value "WS2812_5050")
      (footprint "eagle-import:WS2812-5X5-4PIN")
      (libsource (lib "eagle-import") (part "led-rs_WS2812_5050"))
    )
    (comp (ref "D212")
      (value "WS2812_5050")
      (footprint "eagle-import:WS2812-5X5-4PIN")
      (libsource (lib "eagle-import") (part "led-rs_WS2812_5050"))
    )
    (comp (ref "D213")
      (value "WS2812_5050")
      (footprint "eagle-import:WS2812-5X5-4PIN")
      (libsource (lib "eagle-import") (part "led-rs_WS2812_5050"))
    )
    (comp (ref "D214")
      (value "WS2812_5050")
      (footprint "eagle-import:WS2812-5X5-4PIN")
      (libsource (lib "eagle-import") (part "led-rs_WS2812_5050"))
    )
    (comp (ref "D215")
      (value "WS2812_5050")
      (footprint "eagle-import:WS2812-5X5-4PIN")
      (libsource (lib "eagle-import") (part "led-rs_WS2812_5050"))
    )
    (comp (ref "D216")
      (value "WS2812_5050")
      (footprint "eagle-import:WS2812-5X5-4PIN")
      (libsource (lib "eagle-import") (part "led-rs_WS2812_5050"))
    )
    (comp (ref "D217")
      (value "WS2812_5050")
      (footprint "eagle-import:WS2812-5X5-4PIN")
      (libsource (lib "eagle-import") (part "led-rs_WS2812_5050"))
    )
    (comp (ref "D218")
      (value "WS2812_5050")
      (footprint "eagle-import:WS2812-5X5-4PIN")
      (libsource (lib "eagle-import") (part "led-rs_WS2812_5050"))
    )
    (comp (ref "D219")
      (value "WS2812_5050")
      (footprint "eagle-import:WS2812-5X5-4PIN")
      (libsource (lib "eagle-import") (part "led-rs_WS2812_5050"))
    )
    (comp (ref "D220")
      (value "WS2812_5050")
      (footprint "eagle-import:WS2812-5X5-4PIN")
      (libsource (lib "eagle-import") (part "led-rs_WS2812_5050"))
    )
    (comp (ref "D221")
      (value "WS2812_5050")
      (footprint "eagle-import:WS2812-5X5-4PIN")
      (libsource (lib "eagle-import") (part "led-rs_WS2812_5050"))
    )
    (comp (ref "D222")
      (value "WS2812_5050")
      (footprint "eagle-import:WS2812-5X5-4PIN")
      (libsource (lib "eagle-import") (part "led-rs_WS2812_5050"))
    )
    (comp (ref "D223")
      (value "WS2812_5050")
      (footprint "eagle-import:WS2812-5X5-4PIN")
      (libsource (lib "eagle-import") (part "led-rs_WS2812_5050"))
    )
    (comp (ref "D224")
      (value "WS2812_5050")
      (footprint "eagle-import:WS2812-5X5-4PIN")
      (libsource (lib "eagle-import") (part "led-rs_WS2812_5050"))
    )
    (comp (ref "D225")
      (value "WS2812_5050")
      (footprint "eagle-import:WS2812-5X5-4PIN")
      (libsource (lib "eagle-import") (part "led-rs_WS2812_5050"))
    )
    (comp (ref "D226")
      (value "WS2812_5050")
      (footprint "eagle-import:WS2812-5X5-4PIN")
      (libsource (lib "eagle-import") (part "led-rs_WS2812_5050"))
    )
    (comp (ref "D227")
      (value "WS2812_5050")
      (footprint "eagle-import:WS2812-5X5-4PIN")
      (libsource (lib "eagle-import") (part "led-rs_WS2812_5050"))
    )
    (comp (ref "D228")
      (value "WS2812_5050")
      (footprint "eagle-import:WS2812-5X5-4PIN")
      (libsource (lib "eagle-import") (part "led-rs_WS2812_5050"))
    )
    (comp (ref "D229")
      (value "WS2812_5050")
      (footprint "eagle-import:WS2812-5X5-4PIN")
      (libsource (lib "eagle-import") (part "led-rs_WS2812_5050"))
    )
    (comp (ref "D230")
      (value "WS2812_5050")
      (footprint "eagle-import:WS2812-5X5-4PIN")
      (libsource (lib "eagle-import") (part "led-rs_WS2812_5050"))
    )
    (comp (ref "D231")
      (value "WS2812_5050")
      (footprint "eagle-import:WS2812-5X5-4PIN")
      (libsource (lib "eagle-import") (part "led-rs_WS2812_5050"))
    )
    (comp (ref "D232")
      (value "WS2812_5050")
      (footprint "eagle-import:WS2812-5X5-4PIN")
      (libsource (lib "eagle-import") (part "led-rs_WS2812_5050"))
    )
    (comp (ref "D233")
      (value "WS2812_5050")
      (footprint "eagle-import:WS2812-5X5-4PIN")
      (libsource (lib "eagle-import") (part "led-rs_WS2812_5050"))
    )
    (comp (ref "D234")
      (value "WS2812_5050")
      (footprint "eagle-import:WS2812-5X5-4PIN")
      (libsource (lib "eagle-import") (part "led-rs_WS2812_5050"))
    )
    (comp (ref "D235")
      (value "WS2812_5050")
      (footprint "eagle-import:WS2812-5X5-4PIN")
      (libsource (lib "eagle-import") (part "led-rs_WS2812_5050"))
    )
    (comp (ref "D236")
      (value "WS2812_5050")
      (footprint "eagle-import:WS2812-5X5-4PIN")
      (libsource (lib "eagle-import") (part "led-rs_WS2812_5050"))
    )
    (comp (ref "D237")
      (value "WS2812_5050")
      (footprint "eagle-import:WS2812-5X5-4PIN")
      (libsource (lib "eagle-import") (part "led-rs_WS2812_5050"))
    )
    (comp (ref "D238")
      (value "WS2812_5050")
      (footprint "eagle-import:WS2812-5X5-4PIN")
      (libsource (lib "eagle-import") (part "led-rs_WS2812_5050"))
    )
    (comp (ref "D239")
      (value "WS2812_5050")
      (footprint "eagle-import:WS2812-5X5-4PIN")
      (libsource (lib "eagle-import") (part "led-rs_WS2812_5050"))
    )
    (comp (ref "D240")
      (value "WS2812_5050")
      (footprint "eagle-import:WS2812-5X5-4PIN")
      (libsource (lib "eagle-import") (part "led-rs_WS2812_5050"))
    )
    (comp (ref "D1")
      (value "WS2812_5050")
      (footprint "eagle-import:WS2812-5X5-4PIN")
      (libsource (lib "eagle-import") (part "led-rs_WS2812_5050"))
    )
    (comp (ref "D2")
      (value "WS2812_5050")
      (footprint "eagle-import:WS2812-5X5-4PIN")
      (libsource (lib "eagle-import") (part "led-rs_WS2812_5050"))
    )
    (comp (ref "D3")
      (value "WS2812_5050")
      (footprint "eagle-import:WS2812-5X5-4PIN")
      (libsource (lib "eagle-import") (part "led-rs_WS2812_5050"))
    )
    (comp (ref "D4")
      (value "WS2812_5050")
      (footprint "eagle-import:WS2812-5X5-4PIN")
      (libsource (lib "eagle-import") (part "led-rs_WS2812_5050"))
    )
    (comp (ref "D5")
      (value "WS2812_5050")
      (footprint "eagle-import:WS2812-5X5-4PIN")
      (libsource (lib "eagle-import") (part "led-rs_WS2812_5050"))
    )
    (comp (ref "D6")
      (value "WS2812_5050")
      (footprint "eagle-import:WS2812-5X5-4PIN")
      (libsource (lib "eagle-import") (part "led-rs_WS2812_5050"))
    )
    (comp (ref "D7")
      (value "WS2812_5050")
      (footprint "eagle-import:WS2812-5X5-4PIN")
      (libsource (lib "eagle-import") (part "led-rs_WS2812_5050"))
    )
    (comp (ref "D8")
      (value "WS2812_5050")
      (footprint "eagle-import:WS2812-5X5-4PIN")
      (libsource (lib "eagle-import") (part "led-rs_WS2812_5050"))
    )
    (comp (ref "D9")
      (value "WS2812_5050")
      (footprint "eagle-import:WS2812-5X5-4PIN")
      (libsource (lib "eagle-import") (part "led-rs_WS2812_5050"))
    )
    (comp (ref "D10")
      (value "WS2812_5050")
      (footprint "eagle-import:WS2812-5X5-4PIN")
      (libsource (lib "eagle-import") (part "led-rs_WS2812_5050"))
    )
    (comp (ref "D11")
      (value "WS2812_5050")
      (footprint "eagle-import:WS2812-5X5-4PIN")
      (libsource (lib "eagle-import") (part "led-rs_WS2812_5050"))
    )
    (comp (ref "D12")
      (value "WS2812_5050")
      (footprint "eagle-import:WS2812-5X5-4PIN")
      (libsource (lib "eagle-import") (part "led-rs_WS2812_5050"))
    )
    (comp (ref "D13")
      (value "WS2812_5050")
      (footprint "eagle-import:WS2812-5X5-4PIN")
      (libsource (lib "eagle-import") (part "led-rs_WS2812_5050"))
    )
    (comp (ref "D14")
      (value "WS2812_5050")
      (footprint "eagle-import:WS2812-5X5-4PIN")
      (libsource (lib "eagle-import") (part "led-rs_WS2812_5050"))
    )
    (comp (ref "D15")
      (value "WS2812_5050")
      (footprint "eagle-import:WS2812-5X5-4PIN")
      (libsource (lib "eagle-import") (part "led-rs_WS2812_5050"))
    )
    (comp (ref "D16")
      (value "WS2812_5050")
      (footprint "eagle-import:WS2812-5X5-4PIN")
      (libsource (lib "eagle-import") (part "led-rs_WS2812_5050"))
    )
    (comp (ref "D17")
      (value "WS2812_5050")
      (footprint "eagle-import:WS2812-5X5-4PIN")
      (libsource (lib "eagle-import") (part "led-rs_WS2812_5050"))
    )
    (comp (ref "D18")
      (value "WS2812_5050")
      (footprint "eagle-import:WS2812-5X5-4PIN")
      (libsource (lib "eagle-import") (part "led-rs_WS2812_5050"))
    )
    (comp (ref "D19")
      (value "WS2812_5050")
      (footprint "eagle-import:WS2812-5X5-4PIN")
      (libsource (lib "eagle-import") (part "led-rs_WS2812_5050"))
    )
    (comp (ref "D20")
      (value "WS2812_5050")
      (footprint "eagle-import:WS2812-5X5-4PIN")
      (libsource (lib "eagle-import") (part "led-rs_WS2812_5050"))
    )
    (comp (ref "D21")
      (value "WS2812_5050")
      (footprint "eagle-import:WS2812-5X5-4PIN")
      (libsource (lib "eagle-import") (part "led-rs_WS2812_5050"))
    )
    (comp (ref "D22")
      (value "WS2812_5050")
      (footprint "eagle-import:WS2812-5X5-4PIN")
      (libsource (lib "eagle-import") (part "led-rs_WS2812_5050"))
    )
    (comp (ref "D23")
      (value "WS2812_5050")
      (footprint "eagle-import:WS2812-5X5-4PIN")
      (libsource (lib "eagle-import") (part "led-rs_WS2812_5050"))
    )
    (comp (ref "D24")
      (value "WS2812_5050")
      (footprint "eagle-import:WS2812-5X5-4PIN")
      (libsource (lib "eagle-import") (part "led-rs_WS2812_5050"))
    )
    (comp (ref "D25")
      (value "WS2812_5050")
      (footprint "eagle-import:WS2812-5X5-4PIN")
      (libsource (lib "eagle-import") (part "led-rs_WS2812_5050"))
    )
    (comp (ref "D26")
      (value "WS2812_5050")
      (footprint "eagle-import:WS2812-5X5-4PIN")
      (libsource (lib "eagle-import") (part "led-rs_WS2812_5050"))
    )
    (comp (ref "D27")
      (value "WS2812_5050")
      (footprint "eagle-import:WS2812-5X5-4PIN")
      (libsource (lib "eagle-import") (part "led-rs_WS2812_5050"))
    )
    (comp (ref "D28")
      (value "WS2812_5050")
      (footprint "eagle-import:WS2812-5X5-4PIN")
      (libsource (lib "eagle-import") (part "led-rs_WS2812_5050"))
    )
    (comp (ref "D29")
      (value "WS2812_5050")
      (footprint "eagle-import:WS2812-5X5-4PIN")
      (libsource (lib "eagle-import") (part "led-rs_WS2812_5050"))
    )
    (comp (ref "D30")
      (value "WS2812_5050")
      (footprint "eagle-import:WS2812-5X5-4PIN")
      (libsource (lib "eagle-import") (part "led-rs_WS2812_5050"))
    )
    (comp (ref "D31")
      (value "WS2812_5050")
      (footprint "eagle-import:WS2812-5X5-4PIN")
      (libsource (lib "eagle-import") (part "led-rs_WS2812_5050"))
    )
    (comp (ref "D32")
      (value "WS2812_5050")
      (footprint "eagle-import:WS2812-5X5-4PIN")
      (libsource (lib "eagle-import") (part "led-rs_WS2812_5050"))
    )
    (comp (ref "D33")
      (value "WS2812_5050")
      (footprint "eagle-import:WS2812-5X5-4PIN")
      (libsource (lib "eagle-import") (part "led-rs_WS2812_5050"))
    )
    (comp (ref "D34")
      (value "WS2812_5050")
      (footprint "eagle-import:WS2812-5X5-4PIN")
      (libsource (lib "eagle-import") (part "led-rs_WS2812_5050"))
    )
    (comp (ref "D35")
      (value "WS2812_5050")
      (footprint "eagle-import:WS2812-5X5-4PIN")
      (libsource (lib "eagle-import") (part "led-rs_WS2812_5050"))
    )
    (comp (ref "D36")
      (value "WS2812_5050")
      (footprint "eagle-import:WS2812-5X5-4PIN")
      (libsource (lib "eagle-import") (part "led-rs_WS2812_5050"))
    )
    (comp (ref "D37")
      (value "WS2812_5050")
      (footprint "eagle-import:WS2812-5X5-4PIN")
      (libsource (lib "eagle-import") (part "led-rs_WS2812_5050"))
    )
    (comp (ref "D38")
      (value "WS2812_5050")
      (footprint "eagle-import:WS2812-5X5-4PIN")
      (libsource (lib "eagle-import") (part "led-rs_WS2812_5050"))
    )
    (comp (ref "D39")
      (value "WS2812_5050")
      (footprint "eagle-import:WS2812-5X5-4PIN")
      (libsource (lib "eagle-import") (part "led-rs_WS2812_5050"))
    )
    (comp (ref "D40")
      (value "WS2812_5050")
      (footprint "eagle-import:WS2812-5X5-4PIN")
      (libsource (lib "eagle-import") (part "led-rs_WS2812_5050"))
    )
    (comp (ref "D41")
      (value "WS2812_5050")
      (footprint "eagle-import:WS2812-5X5-4PIN")
      (libsource (lib "eagle-import") (part "led-rs_WS2812_5050"))
    )
    (comp (ref "D42")
      (value "WS2812_5050")
      (footprint "eagle-import:WS2812-5X5-4PIN")
      (libsource (lib "eagle-import") (part "led-rs_WS2812_5050"))
    )
    (comp (ref "D43")
      (value "WS2812_5050")
      (footprint "eagle-import:WS2812-5X5-4PIN")
      (libsource (lib "eagle-import") (part "led-rs_WS2812_5050"))
    )
    (comp (ref "D44")
      (value "WS2812_5050")
      (footprint "eagle-import:WS2812-5X5-4PIN")
      (libsource (lib "eagle-import") (part "led-rs_WS2812_5050"))
    )
    (comp (ref "D45")
      (value "WS2812_5050")
      (footprint "eagle-import:WS2812-5X5-4PIN")
      (libsource (lib "eagle-import") (part "led-rs_WS2812_5050"))
    )
    (comp (ref "D46")
      (value "WS2812_5050")
      (footprint "eagle-import:WS2812-5X5-4PIN")
      (libsource (lib "eagle-import") (part "led-rs_WS2812_5050"))
    )
    (comp (ref "D47")
      (value "WS2812_5050")
      (footprint "eagle-import:WS2812-5X5-4PIN")
      (libsource (lib "eagle-import") (part "led-rs_WS2812_5050"))
    )
    (comp (ref "D48")
      (value "WS2812_5050")
      (footprint "eagle-import:WS2812-5X5-4PIN")
      (libsource (lib "eagle-import") (part "led-rs_WS2812_5050"))
    )
    (comp (ref "D49")
      (value "WS2812_5050")
      (footprint "eagle-import:WS2812-5X5-4PIN")
      (libsource (lib "eagle-import") (part "led-rs_WS2812_5050"))
    )
    (comp (ref "D50")
      (value "WS2812_5050")
      (footprint "eagle-import:WS2812-5X5-4PIN")
      (libsource (lib "eagle-import") (part "led-rs_WS2812_5050"))
    )
    (comp (ref "D51")
      (value "WS2812_5050")
      (footprint "eagle-import:WS2812-5X5-4PIN")
      (libsource (lib "eagle-import") (part "led-rs_WS2812_5050"))
    )
    (comp (ref "D52")
      (value "WS2812_5050")
      (footprint "eagle-import:WS2812-5X5-4PIN")
      (libsource (lib "eagle-import") (part "led-rs_WS2812_5050"))
    )
    (comp (ref "D53")
      (value "WS2812_5050")
      (footprint "eagle-import:WS2812-5X5-4PIN")
      (libsource (lib "eagle-import") (part "led-rs_WS2812_5050"))
    )
    (comp (ref "D54")
      (value "WS2812_5050")
      (footprint "eagle-import:WS2812-5X5-4PIN")
      (libsource (lib "eagle-import") (part "led-rs_WS2812_5050"))
    )
    (comp (ref "D55")
      (value "WS2812_5050")
      (footprint "eagle-import:WS2812-5X5-4PIN")
      (libsource (lib "eagle-import") (part "led-rs_WS2812_5050"))
    )
    (comp (ref "D56")
      (value "WS2812_5050")
      (footprint "eagle-import:WS2812-5X5-4PIN")
      (libsource (lib "eagle-import") (part "led-rs_WS2812_5050"))
    )
    (comp (ref "D57")
      (value "WS2812_5050")
      (footprint "eagle-import:WS2812-5X5-4PIN")
      (libsource (lib "eagle-import") (part "led-rs_WS2812_5050"))
    )
    (comp (ref "D58")
      (value "WS2812_5050")
      (footprint "eagle-import:WS2812-5X5-4PIN")
      (libsource (lib "eagle-import") (part "led-rs_WS2812_5050"))
    )
    (comp (ref "D59")
      (value "WS2812_5050")
      (footprint "eagle-import:WS2812-5X5-4PIN")
      (libsource (lib "eagle-import") (part "led-rs_WS2812_5050"))
    )
    (comp (ref "D60")
      (value "WS2812_5050")
      (footprint "eagle-import:WS2812-5X5-4PIN")
      (libsource (lib "eagle-import") (part "led-rs_WS2812_5050"))
    )
    (comp (ref "D61")
      (value "WS2812_5050")
      (footprint "eagle-import:WS2812-5X5-4PIN")
      (libsource (lib "eagle-import") (part "led-rs_WS2812_5050"))
    )
    (comp (ref "D62")
      (value "WS2812_5050")
      (footprint "eagle-import:WS2812-5X5-4PIN")
      (libsource (lib "eagle-import") (part "led-rs_WS2812_5050"))
    )
    (comp (ref "D63")
      (value "WS2812_5050")
      (footprint "eagle-import:WS2812-5X5-4PIN")
      (libsource (lib "eagle-import") (part "led-rs_WS2812_5050"))
    )
    (comp (ref "D64")
      (value "WS2812_5050")
      (footprint "eagle-import:WS2812-5X5-4PIN")
      (libsource (lib "eagle-import") (part "led-rs_WS2812_5050"))
    )
    (comp (ref "D65")
      (value "WS2812_5050")
      (footprint "eagle-import:WS2812-5X5-4PIN")
      (libsource (lib "eagle-import") (part "led-rs_WS2812_5050"))
    )
    (comp (ref "D66")
      (value "WS2812_5050")
      (footprint "eagle-import:WS2812-5X5-4PIN")
      (libsource (lib "eagle-import") (part "led-rs_WS2812_5050"))
    )
    (comp (ref "D67")
      (value "WS2812_5050")
      (footprint "eagle-import:WS2812-5X5-4PIN")
      (libsource (lib "eagle-import") (part "led-rs_WS2812_5050"))
    )
    (comp (ref "D68")
      (value "WS2812_5050")
      (footprint "eagle-import:WS2812-5X5-4PIN")
      (libsource (lib "eagle-import") (part "led-rs_WS2812_5050"))
    )
    (comp (ref "D69")
      (value "WS2812_5050")
      (footprint "eagle-import:WS2812-5X5-4PIN")
      (libsource (lib "eagle-import") (part "led-rs_WS2812_5050"))
    )
    (comp (ref "D70")
      (value "WS2812_5050")
      (footprint "eagle-import:WS2812-5X5-4PIN")
      (libsource (lib "eagle-import") (part "led-rs_WS2812_5050"))
    )
    (comp (ref "D71")
      (value "WS2812_5050")
      (footprint "eagle-import:WS2812-5X5-4PIN")
      (libsource (lib "eagle-import") (part "led-rs_WS2812_5050"))
    )
    (comp (ref "D72")
      (value "WS2812_5050")
      (footprint "eagle-import:WS2812-5X5-4PIN")
      (libsource (lib "eagle-import") (part "led-rs_WS2812_5050"))
    )
    (comp (ref "D73")
      (value "WS2812_5050")
      (footprint "eagle-import:WS2812-5X5-4PIN")
      (libsource (lib "eagle-import") (part "led-rs_WS2812_5050"))
    )
    (comp (ref "D74")
      (value "WS2812_5050")
      (footprint "eagle-import:WS2812-5X5-4PIN")
      (libsource (lib "eagle-import") (part "led-rs_WS2812_5050"))
    )
    (comp (ref "D75")
      (value "WS2812_5050")
      (footprint "eagle-import:WS2812-5X5-4PIN")
      (libsource (lib "eagle-import") (part "led-rs_WS2812_5050"))
    )
    (comp (ref "D76")
      (value "WS2812_5050")
      (footprint "eagle-import:WS2812-5X5-4PIN")
      (libsource (lib "eagle-import") (part "led-rs_WS2812_5050"))
    )
    (comp (ref "D77")
      (value "WS2812_5050")
      (footprint "eagle-import:WS2812-5X5-4PIN")
      (libsource (lib "eagle-import") (part "led-rs_WS2812_5050"))
    )
    (comp (ref "D78")
      (value "WS2812_5050")
      (footprint "eagle-import:WS2812-5X5-4PIN")
      (libsource (lib "eagle-import") (part "led-rs_WS2812_5050"))
    )
    (comp (ref "D79")
      (value "WS2812_5050")
      (footprint "eagle-import:WS2812-5X5-4PIN")
      (libsource (lib "eagle-import") (part "led-rs_WS2812_5050"))
    )
    (comp (ref "D80")
      (value "WS2812_5050")
      (footprint "eagle-import:WS2812-5X5-4PIN")
      (libsource (lib "eagle-import") (part "led-rs_WS2812_5050"))
    )
    (comp (ref "D81")
      (value "WS2812_5050")
      (footprint "eagle-import:WS2812-5X5-4PIN")
      (libsource (lib "eagle-import") (part "led-rs_WS2812_5050"))
    )
    (comp (ref "D82")
      (value "WS2812_5050")
      (footprint "eagle-import:WS2812-5X5-4PIN")
      (libsource (lib "eagle-import") (part "led-rs_WS2812_5050"))
    )
    (comp (ref "D83")
      (value "WS2812_5050")
      (footprint "eagle-import:WS2812-5X5-4PIN")
      (libsource (lib "eagle-import") (part "led-rs_WS2812_5050"))
    )
    (comp (ref "D84")
      (value "WS2812_5050")
      (footprint "eagle-import:WS2812-5X5-4PIN")
      (libsource (lib "eagle-import") (part "led-rs_WS2812_5050"))
    )
    (comp (ref "D85")
      (value "WS2812_5050")
      (footprint "eagle-import:WS2812-5X5-4PIN")
      (libsource (lib "eagle-import") (part "led-rs_WS2812_5050"))
    )
    (comp (ref "D86")
      (value "WS2812_5050")
      (footprint "eagle-import:WS2812-5X5-4PIN")
      (libsource (lib "eagle-import") (part "led-rs_WS2812_5050"))
    )
    (comp (ref "D87")
      (value "WS2812_5050")
      (footprint "eagle-import:WS2812-5X5-4PIN")
      (libsource (lib "eagle-import") (part "led-rs_WS2812_5050"))
    )
    (comp (ref "D88")
      (value "WS2812_5050")
      (footprint "eagle-import:WS2812-5X5-4PIN")
      (libsource (lib "eagle-import") (part "led-rs_WS2812_5050"))
    )
    (comp (ref "D89")
      (value "WS2812_5050")
      (footprint "eagle-import:WS2812-5X5-4PIN")
      (libsource (lib "eagle-import") (part "led-rs_WS2812_5050"))
    )
    (comp (ref "D90")
      (value "WS2812_5050")
      (footprint "eagle-import:WS2812-5X5-4PIN")
      (libsource (lib "eagle-import") (part "led-rs_WS2812_5050"))
    )
    (comp (ref "D91")
      (value "WS2812_5050")
      (footprint "eagle-import:WS2812-5X5-4PIN")
      (libsource (lib "eagle-import") (part "led-rs_WS2812_5050"))
    )
    (comp (ref "D92")
      (value "WS2812_5050")
      (footprint "eagle-import:WS2812-5X5-4PIN")
      (libsource (lib "eagle-import") (part "led-rs_WS2812_5050"))
    )
    (comp (ref "D93")
      (value "WS2812_5050")
      (footprint "eagle-import:WS2812-5X5-4PIN")
      (libsource (lib "eagle-import") (part "led-rs_WS2812_5050"))
    )
    (comp (ref "D94")
      (value "WS2812_5050")
      (footprint "eagle-import:WS2812-5X5-4PIN")
      (libsource (lib "eagle-import") (part "led-rs_WS2812_5050"))
    )
    (comp (ref "D95")
      (value "WS2812_5050")
      (footprint "eagle-import:WS2812-5X5-4PIN")
      (libsource (lib "eagle-import") (part "led-rs_WS2812_5050"))
    )
    (comp (ref "D96")
      (value "WS2812_5050")
      (footprint "eagle-import:WS2812-5X5-4PIN")
      (libsource (lib "eagle-import") (part "led-rs_WS2812_5050"))
    )
    (comp (ref "D97")
      (value "WS2812_5050")
      (footprint "eagle-import:WS2812-5X5-4PIN")
      (libsource (lib "eagle-import") (part "led-rs_WS2812_5050"))
    )
    (comp (ref "D98")
      (value "WS2812_5050")
      (footprint "eagle-import:WS2812-5X5-4PIN")
      (libsource (lib "eagle-import") (part "led-rs_WS2812_5050"))
    )
    (comp (ref "D99")
      (value "WS2812_5050")
      (footprint "eagle-import:WS2812-5X5-4PIN")
      (libsource (lib "eagle-import") (part "led-rs_WS2812_5050"))
    )
    (comp (ref "D100")
      (value "WS2812_5050")
      (footprint "eagle-import:WS2812-5X5-4PIN")
      (libsource (lib "eagle-import") (part "led-rs_WS2812_5050"))
    )
    (comp (ref "D101")
      (value "WS2812_5050")
      (footprint "eagle-import:WS2812-5X5-4PIN")
      (libsource (lib "eagle-import") (part "led-rs_WS2812_5050"))
    )
    (comp (ref "D102")
      (value "WS2812_5050")
      (footprint "eagle-import:WS2812-5X5-4PIN")
      (libsource (lib "eagle-import") (part "led-rs_WS2812_5050"))
    )
    (comp (ref "D103")
      (value "WS2812_5050")
      (footprint "eagle-import:WS2812-5X5-4PIN")
      (libsource (lib "eagle-import") (part "led-rs_WS2812_5050"))
    )
    (comp (ref "D104")
      (value "WS2812_5050")
      (footprint "eagle-import:WS2812-5X5-4PIN")
      (libsource (lib "eagle-import") (part "led-rs_WS2812_5050"))
    )
    (comp (ref "D105")
      (value "WS2812_5050")
      (footprint "eagle-import:WS2812-5X5-4PIN")
      (libsource (lib "eagle-import") (part "led-rs_WS2812_5050"))
    )
    (comp (ref "D106")
      (value "WS2812_5050")
      (footprint "eagle-import:WS2812-5X5-4PIN")
      (libsource (lib "eagle-import") (part "led-rs_WS2812_5050"))
    )
    (comp (ref "D107")
      (value "WS2812_5050")
      (footprint "eagle-import:WS2812-5X5-4PIN")
      (libsource (lib "eagle-import") (part "led-rs_WS2812_5050"))
    )
    (comp (ref "D108")
      (value "WS2812_5050")
      (footprint "eagle-import:WS2812-5X5-4PIN")
      (libsource (lib "eagle-import") (part "led-rs_WS2812_5050"))
    )
    (comp (ref "D109")
      (value "WS2812_5050")
      (footprint "eagle-import:WS2812-5X5-4PIN")
      (libsource (lib "eagle-import") (part "led-rs_WS2812_5050"))
    )
    (comp (ref "D110")
      (value "WS2812_5050")
      (footprint "eagle-import:WS2812-5X5-4PIN")
      (libsource (lib "eagle-import") (part "led-rs_WS2812_5050"))
    )
    (comp (ref "D111")
      (value "WS2812_5050")
      (footprint "eagle-import:WS2812-5X5-4PIN")
      (libsource (lib "eagle-import") (part "led-rs_WS2812_5050"))
    )
    (comp (ref "D112")
      (value "WS2812_5050")
      (footprint "eagle-import:WS2812-5X5-4PIN")
      (libsource (lib "eagle-import") (part "led-rs_WS2812_5050"))
    )
    (comp (ref "D113")
      (value "WS2812_5050")
      (footprint "eagle-import:WS2812-5X5-4PIN")
      (libsource (lib "eagle-import") (part "led-rs_WS2812_5050"))
    )
    (comp (ref "D114")
      (value "WS2812_5050")
      (footprint "eagle-import:WS2812-5X5-4PIN")
      (libsource (lib "eagle-import") (part "led-rs_WS2812_5050"))
    )
    (comp (ref "D115")
      (value "WS2812_5050")
      (footprint "eagle-import:WS2812-5X5-4PIN")
      (libsource (lib "eagle-import") (part "led-rs_WS2812_5050"))
    )
    (comp (ref "D116")
      (value "WS2812_5050")
      (footprint "eagle-import:WS2812-5X5-4PIN")
      (libsource (lib "eagle-import") (part "led-rs_WS2812_5050"))
    )
    (comp (ref "D117")
      (value "WS2812_5050")
      (footprint "eagle-import:WS2812-5X5-4PIN")
      (libsource (lib "eagle-import") (part "led-rs_WS2812_5050"))
    )
    (comp (ref "D118")
      (value "WS2812_5050")
      (footprint "eagle-import:WS2812-5X5-4PIN")
      (libsource (lib "eagle-import") (part "led-rs_WS2812_5050"))
    )
    (comp (ref "D119")
      (value "WS2812_5050")
      (footprint "eagle-import:WS2812-5X5-4PIN")
      (libsource (lib "eagle-import") (part "led-rs_WS2812_5050"))
    )
    (comp (ref "D120")
      (value "WS2812_5050")
      (footprint "eagle-import:WS2812-5X5-4PIN")
      (libsource (lib "eagle-import") (part "led-rs_WS2812_5050"))
    )
  )
  (nets
    (net (code "1") (name "DI") (class "Default")
      (node (ref "D405") (pin "DI") (pinfunction "DI_DI") (pintype "input"))
      (node (ref "R1") (pin "2") (pinfunction "2_2") (pintype "passive"))
    )
    (net (code "2") (name "DO2") (class "Default")
      (node (ref "D1") (pin "DI") (pinfunction "DI_DI") (pintype "input"))
      (node (ref "D2") (pin "DO") (pinfunction "DO_DO") (pintype "output"))
    )
    (net (code "3") (name "DO3") (class "Default")
      (node (ref "D2") (pin "DI") (pinfunction "DI_DI") (pintype "input"))
      (node (ref "D3") (pin "DO") (pinfunction "DO_DO") (pintype "output"))
    )
    (net (code "4") (name "DO4") (class "Default")
      (node (ref "D3") (pin "DI") (pinfunction "DI_DI") (pintype "input"))
      (node (ref "D4") (pin "DO") (pinfunction "DO_DO") (pintype "output"))
    )
    (net (code "5") (name "DO5") (class "Default")
      (node (ref "D4") (pin "DI") (pinfunction "DI_DI") (pintype "input"))
      (node (ref "D5") (pin "DO") (pinfunction "DO_DO") (pintype "output"))
    )
    (net (code "6") (name "DO6") (class "Default")
      (node (ref "D5") (pin "DI") (pinfunction "DI_DI") (pintype "input"))
      (node (ref "D6") (pin "DO") (pinfunction "DO_DO") (pintype "output"))
    )
    (net (code "7") (name "DO7") (class "Default")
      (node (ref "D6") (pin "DI") (pinfunction "DI_DI") (pintype "input"))
      (node (ref "D7") (pin "DO") (pinfunction "DO_DO") (pintype "output"))
    )
    (net (code "8") (name "DO8") (class "Default")
      (node (ref "D7") (pin "DI") (pinfunction "DI_DI") (pintype "input"))
      (node (ref "D8") (pin "DO") (pinfunction "DO_DO") (pintype "output"))
    )
    (net (code "9") (name "DO9") (class "Default")
      (node (ref "D8") (pin "DI") (pinfunction "DI_DI") (pintype "input"))
      (node (ref "D9") (pin "DO") (pinfunction "DO_DO") (pintype "output"))
    )
    (net (code "10") (name "DO10") (class "Default")
      (node (ref "D10") (pin "DO") (pinfunction "DO_DO") (pintype "output"))
      (node (ref "D9") (pin "DI") (pinfunction "DI_DI") (pintype "input"))
    )
    (net (code "11") (name "DO11") (class "Default")
      (node (ref "D10") (pin "DI") (pinfunction "DI_DI") (pintype "input"))
      (node (ref "D11") (pin "DO") (pinfunction "DO_DO") (pintype "output"))
    )
    (net (code "12") (name "DO12") (class "Default")
      (node (ref "D11") (pin "DI") (pinfunction "DI_DI") (pintype "input"))
      (node (ref "D12") (pin "DO") (pinfunction "DO_DO") (pintype "output"))
    )
    (net (code "13") (name "DO13") (class "Default")
      (node (ref "D12") (pin "DI") (pinfunction "DI_DI") (pintype "input"))
      (node (ref "D13") (pin "DO") (pinfunction "DO_DO") (pintype "output"))
    )
    (net (code "14") (name "DO14") (class "Default")
      (node (ref "D13") (pin "DI") (pinfunction "DI_DI") (pintype "input"))
      (node (ref "D14") (pin "DO") (pinfunction "DO_DO") (pintype "output"))
    )
    (net (code "15") (name "DO15") (class "Default")
      (node (ref "D14") (pin "DI") (pinfunction "DI_DI") (pintype "input"))
      (node (ref "D15") (pin "DO") (pinfunction "DO_DO") (pintype "output"))
    )
    (net (code "16") (name "DO16") (class "Default")
      (node (ref "D15") (pin "DI") (pinfunction "DI_DI") (pintype "input"))
      (node (ref "D16") (pin "DO") (pinfunction "DO_DO") (pintype "output"))
    )
    (net (code "17") (name "DO17") (class "Default")
      (node (ref "D16") (pin "DI") (pinfunction "DI_DI") (pintype "input"))
      (node (ref "D17") (pin "DO") (pinfunction "DO_DO") (pintype "output"))
    )
    (net (code "18") (name "DO18") (class "Default")
      (node (ref "D17") (pin "DI") (pinfunction "DI_DI") (pintype "input"))
      (node (ref "D18") (pin "DO") (pinfunction "DO_DO") (pintype "output"))
    )
    (net (code "19") (name "DO19") (class "Default")
      (node (ref "D18") (pin "DI") (pinfunction "DI_DI") (pintype "input"))
      (node (ref "D19") (pin "DO") (pinfunction "DO_DO") (pintype "output"))
    )
    (net (code "20") (name "DO20") (class "Default")
      (node (ref "D19") (pin "DI") (pinfunction "DI_DI") (pintype "input"))
      (node (ref "D20") (pin "DO") (pinfunction "DO_DO") (pintype "output"))
    )
    (net (code "21") (name "DO21") (class "Default")
      (node (ref "D20") (pin "DI") (pinfunction "DI_DI") (pintype "input"))
      (node (ref "D21") (pin "DO") (pinfunction "DO_DO") (pintype "output"))
    )
    (net (code "22") (name "DO22") (class "Default")
      (node (ref "D21") (pin "DI") (pinfunction "DI_DI") (pintype "input"))
      (node (ref "D22") (pin "DO") (pinfunction "DO_DO") (pintype "output"))
    )
    (net (code "23") (name "DO23") (class "Default")
      (node (ref "D22") (pin "DI") (pinfunction "DI_DI") (pintype "input"))
      (node (ref "D23") (pin "DO") (pinfunction "DO_DO") (pintype "output"))
    )
    (net (code "24") (name "DO24") (class "Default")
      (node (ref "D23") (pin "DI") (pinfunction "DI_DI") (pintype "input"))
      (node (ref "D24") (pin "DO") (pinfunction "DO_DO") (pintype "output"))
    )
    (net (code "25") (name "DO25") (class "Default")
      (node (ref "D24") (pin "DI") (pinfunction "DI_DI") (pintype "input"))
      (node (ref "D25") (pin "DO") (pinfunction "DO_DO") (pintype "output"))
    )
    (net (code "26") (name "DO26") (class "Default")
      (node (ref "D25") (pin "DI") (pinfunction "DI_DI") (pintype "input"))
      (node (ref "D26") (pin "DO") (pinfunction "DO_DO") (pintype "output"))
    )
    (net (code "27") (name "DO27") (class "Default")
      (node (ref "D26") (pin "DI") (pinfunction "DI_DI") (pintype "input"))
      (node (ref "D27") (pin "DO") (pinfunction "DO_DO") (pintype "output"))
    )
    (net (code "28") (name "DO28") (class "Default")
      (node (ref "D27") (pin "DI") (pinfunction "DI_DI") (pintype "input"))
      (node (ref "D28") (pin "DO") (pinfunction "DO_DO") (pintype "output"))
    )
    (net (code "29") (name "DO29") (class "Default")
      (node (ref "D28") (pin "DI") (pinfunction "DI_DI") (pintype "input"))
      (node (ref "D29") (pin "DO") (pinfunction "DO_DO") (pintype "output"))
    )
    (net (code "30") (name "DO30") (class "Default")
      (node (ref "D29") (pin "DI") (pinfunction "DI_DI") (pintype "input"))
      (node (ref "D30") (pin "DO") (pinfunction "DO_DO") (pintype "output"))
    )
    (net (code "31") (name "DO31") (class "Default")
      (node (ref "D30") (pin "DI") (pinfunction "DI_DI") (pintype "input"))
      (node (ref "D31") (pin "DO") (pinfunction "DO_DO") (pintype "output"))
    )
    (net (code "32") (name "DO32") (class "Default")
      (node (ref "D31") (pin "DI") (pinfunction "DI_DI") (pintype "input"))
      (node (ref "D32") (pin "DO") (pinfunction "DO_DO") (pintype "output"))
    )
    (net (code "33") (name "DO33") (class "Default")
      (node (ref "D32") (pin "DI") (pinfunction "DI_DI") (pintype "input"))
      (node (ref "D33") (pin "DO") (pinfunction "DO_DO") (pintype "output"))
    )
    (net (code "34") (name "DO34") (class "Default")
      (node (ref "D33") (pin "DI") (pinfunction "DI_DI") (pintype "input"))
      (node (ref "D34") (pin "DO") (pinfunction "DO_DO") (pintype "output"))
    )
    (net (code "35") (name "DO35") (class "Default")
      (node (ref "D34") (pin "DI") (pinfunction "DI_DI") (pintype "input"))
      (node (ref "D35") (pin "DO") (pinfunction "DO_DO") (pintype "output"))
    )
    (net (code "36") (name "DO36") (class "Default")
      (node (ref "D35") (pin "DI") (pinfunction "DI_DI") (pintype "input"))
      (node (ref "D36") (pin "DO") (pinfunction "DO_DO") (pintype "output"))
    )
    (net (code "37") (name "DO37") (class "Default")
      (node (ref "D36") (pin "DI") (pinfunction "DI_DI") (pintype "input"))
      (node (ref "D37") (pin "DO") (pinfunction "DO_DO") (pintype "output"))
    )
    (net (code "38") (name "DO38") (class "Default")
      (node (ref "D37") (pin "DI") (pinfunction "DI_DI") (pintype "input"))
      (node (ref "D38") (pin "DO") (pinfunction "DO_DO") (pintype "output"))
    )
    (net (code "39") (name "DO39") (class "Default")
      (node (ref "D38") (pin "DI") (pinfunction "DI_DI") (pintype "input"))
      (node (ref "D39") (pin "DO") (pinfunction "DO_DO") (pintype "output"))
    )
    (net (code "40") (name "DO40") (class "Default")
      (node (ref "D39") (pin "DI") (pinfunction "DI_DI") (pintype "input"))
      (node (ref "D40") (pin "DO") (pinfunction "DO_DO") (pintype "output"))
    )
    (net (code "41") (name "DO41") (class "Default")
      (node (ref "D40") (pin "DI") (pinfunction "DI_DI") (pintype "input"))
      (node (ref "D41") (pin "DO") (pinfunction "DO_DO") (pintype "output"))
    )
    (net (code "42") (name "DO42") (class "Default")
      (node (ref "D41") (pin "DI") (pinfunction "DI_DI") (pintype "input"))
      (node (ref "D42") (pin "DO") (pinfunction "DO_DO") (pintype "output"))
    )
    (net (code "43") (name "DO43") (class "Default")
      (node (ref "D42") (pin "DI") (pinfunction "DI_DI") (pintype "input"))
      (node (ref "D43") (pin "DO") (pinfunction "DO_DO") (pintype "output"))
    )
    (net (code "44") (name "DO44") (class "Default")
      (node (ref "D43") (pin "DI") (pinfunction "DI_DI") (pintype "input"))
      (node (ref "D44") (pin "DO") (pinfunction "DO_DO") (pintype "output"))
    )
    (net (code "45") (name "DO45") (class "Default")
      (node (ref "D44") (pin "DI") (pinfunction "DI_DI") (pintype "input"))
      (node (ref "D45") (pin "DO") (pinfunction "DO_DO") (pintype "output"))
    )
    (net (code "46") (name "DO46") (class "Default")
      (node (ref "D45") (pin "DI") (pinfunction "DI_DI") (pintype "input"))
      (node (ref "D46") (pin "DO") (pinfunction "DO_DO") (pintype "output"))
    )
    (net (code "47") (name "DO47") (class "Default")
      (node (ref "D46") (pin "DI") (pinfunction "DI_DI") (pintype "input"))
      (node (ref "D47") (pin "DO") (pinfunction "DO_DO") (pintype "output"))
    )
    (net (code "48") (name "DO48") (class "Default")
      (node (ref "D47") (pin "DI") (pinfunction "DI_DI") (pintype "input"))
      (node (ref "D48") (pin "DO") (pinfunction "DO_DO") (pintype "output"))
    )
    (net (code "49") (name "DO49") (class "Default")
      (node (ref "D48") (pin "DI") (pinfunction "DI_DI") (pintype "input"))
      (node (ref "D49") (pin "DO") (pinfunction "DO_DO") (pintype "output"))
    )
    (net (code "50") (name "DO50") (class "Default")
      (node (ref "D49") (pin "DI") (pinfunction "DI_DI") (pintype "input"))
      (node (ref "D50") (pin "DO") (pinfunction "DO_DO") (pintype "output"))
    )
    (net (code "51") (name "DO51") (class "Default")
      (node (ref "D50") (pin "DI") (pinfunction "DI_DI") (pintype "input"))
      (node (ref "D51") (pin "DO") (pinfunction "DO_DO") (pintype "output"))
    )
    (net (code "52") (name "DO52") (class "Default")
      (node (ref "D51") (pin "DI") (pinfunction "DI_DI") (pintype "input"))
      (node (ref "D52") (pin "DO") (pinfunction "DO_DO") (pintype "output"))
    )
    (net (code "53") (name "DO53") (class "Default")
      (node (ref "D52") (pin "DI") (pinfunction "DI_DI") (pintype "input"))
      (node (ref "D53") (pin "DO") (pinfunction "DO_DO") (pintype "output"))
    )
    (net (code "54") (name "DO54") (class "Default")
      (node (ref "D53") (pin "DI") (pinfunction "DI_DI") (pintype "input"))
      (node (ref "D54") (pin "DO") (pinfunction "DO_DO") (pintype "output"))
    )
    (net (code "55") (name "DO55") (class "Default")
      (node (ref "D54") (pin "DI") (pinfunction "DI_DI") (pintype "input"))
      (node (ref "D55") (pin "DO") (pinfunction "DO_DO") (pintype "output"))
    )
    (net (code "56") (name "DO56") (class "Default")
      (node (ref "D55") (pin "DI") (pinfunction "DI_DI") (pintype "input"))
      (node (ref "D56") (pin "DO") (pinfunction "DO_DO") (pintype "output"))
    )
    (net (code "57") (name "DO57") (class "Default")
      (node (ref "D56") (pin "DI") (pinfunction "DI_DI") (pintype "input"))
      (node (ref "D57") (pin "DO") (pinfunction "DO_DO") (pintype "output"))
    )
    (net (code "58") (name "DO58") (class "Default")
      (node (ref "D57") (pin "DI") (pinfunction "DI_DI") (pintype "input"))
      (node (ref "D58") (pin "DO") (pinfunction "DO_DO") (pintype "output"))
    )
    (net (code "59") (name "DO59") (class "Default")
      (node (ref "D58") (pin "DI") (pinfunction "DI_DI") (pintype "input"))
      (node (ref "D59") (pin "DO") (pinfunction "DO_DO") (pintype "output"))
    )
    (net (code "60") (name "DO60") (class "Default")
      (node (ref "D59") (pin "DI") (pinfunction "DI_DI") (pintype "input"))
      (node (ref "D60") (pin "DO") (pinfunction "DO_DO") (pintype "output"))
    )
    (net (code "61") (name "DO61") (class "Default")
      (node (ref "D60") (pin "DI") (pinfunction "DI_DI") (pintype "input"))
      (node (ref "D61") (pin "DO") (pinfunction "DO_DO") (pintype "output"))
    )
    (net (code "62") (name "DO62") (class "Default")
      (node (ref "D61") (pin "DI") (pinfunction "DI_DI") (pintype "input"))
      (node (ref "D62") (pin "DO") (pinfunction "DO_DO") (pintype "output"))
    )
    (net (code "63") (name "DO63") (class "Default")
      (node (ref "D62") (pin "DI") (pinfunction "DI_DI") (pintype "input"))
      (node (ref "D63") (pin "DO") (pinfunction "DO_DO") (pintype "output"))
    )
    (net (code "64") (name "DO64") (class "Default")
      (node (ref "D63") (pin "DI") (pinfunction "DI_DI") (pintype "input"))
      (node (ref "D64") (pin "DO") (pinfunction "DO_DO") (pintype "output"))
    )
    (net (code "65") (name "DO65") (class "Default")
      (node (ref "D64") (pin "DI") (pinfunction "DI_DI") (pintype "input"))
      (node (ref "D65") (pin "DO") (pinfunction "DO_DO") (pintype "output"))
    )
    (net (code "66") (name "DO66") (class "Default")
      (node (ref "D65") (pin "DI") (pinfunction "DI_DI") (pintype "input"))
      (node (ref "D66") (pin "DO") (pinfunction "DO_DO") (pintype "output"))
    )
    (net (code "67") (name "DO67") (class "Default")
      (node (ref "D66") (pin "DI") (pinfunction "DI_DI") (pintype "input"))
      (node (ref "D67") (pin "DO") (pinfunction "DO_DO") (pintype "output"))
    )
    (net (code "68") (name "DO68") (class "Default")
      (node (ref "D67") (pin "DI") (pinfunction "DI_DI") (pintype "input"))
      (node (ref "D68") (pin "DO") (pinfunction "DO_DO") (pintype "output"))
    )
    (net (code "69") (name "DO69") (class "Default")
      (node (ref "D68") (pin "DI") (pinfunction "DI_DI") (pintype "input"))
      (node (ref "D69") (pin "DO") (pinfunction "DO_DO") (pintype "output"))
    )
    (net (code "70") (name "DO70") (class "Default")
      (node (ref "D69") (pin "DI") (pinfunction "DI_DI") (pintype "input"))
      (node (ref "D70") (pin "DO") (pinfunction "DO_DO") (pintype "output"))
    )
    (net (code "71") (name "DO71") (class "Default")
      (node (ref "D70") (pin "DI") (pinfunction "DI_DI") (pintype "input"))
      (node (ref "D71") (pin "DO") (pinfunction "DO_DO") (pintype "output"))
    )
    (net (code "72") (name "DO72") (class "Default")
      (node (ref "D71") (pin "DI") (pinfunction "DI_DI") (pintype "input"))
      (node (ref "D72") (pin "DO") (pinfunction "DO_DO") (pintype "output"))
    )
    (net (code "73") (name "DO73") (class "Default")
      (node (ref "D72") (pin "DI") (pinfunction "DI_DI") (pintype "input"))
      (node (ref "D73") (pin "DO") (pinfunction "DO_DO") (pintype "output"))
    )
    (net (code "74") (name "DO74") (class "Default")
      (node (ref "D73") (pin "DI") (pinfunction "DI_DI") (pintype "input"))
      (node (ref "D74") (pin "DO") (pinfunction "DO_DO") (pintype "output"))
    )
    (net (code "75") (name "DO75") (class "Default")
      (node (ref "D74") (pin "DI") (pinfunction "DI_DI") (pintype "input"))
      (node (ref "D75") (pin "DO") (pinfunction "DO_DO") (pintype "output"))
    )
    (net (code "76") (name "DO76") (class "Default")
      (node (ref "D75") (pin "DI") (pinfunction "DI_DI") (pintype "input"))
      (node (ref "D76") (pin "DO") (pinfunction "DO_DO") (pintype "output"))
    )
    (net (code "77") (name "DO91") (class "Default")
      (node (ref "D90") (pin "DI") (pinfunction "DI_DI") (pintype "input"))
      (node (ref "D91") (pin "DO") (pinfunction "DO_DO") (pintype "output"))
    )
    (net (code "78") (name "DO106") (class "Default")
      (node (ref "D105") (pin "DI") (pinfunction "DI_DI") (pintype "input"))
      (node (ref "D106") (pin "DO") (pinfunction "DO_DO") (pintype "output"))
    )
    (net (code "79") (name "DO121") (class "Default")
      (node (ref "D120") (pin "DI") (pinfunction "DI_DI") (pintype "input"))
      (node (ref "D121") (pin "DO") (pinfunction "DO_DO") (pintype "output"))
    )
    (net (code "80") (name "DO136") (class "Default")
      (node (ref "D135") (pin "DI") (pinfunction "DI_DI") (pintype "input"))
      (node (ref "D136") (pin "DO") (pinfunction "DO_DO") (pintype "output"))
    )
    (net (code "81") (name "DO151") (class "Default")
      (node (ref "D150") (pin "DI") (pinfunction "DI_DI") (pintype "input"))
      (node (ref "D151") (pin "DO") (pinfunction "DO_DO") (pintype "output"))
    )
    (net (code "82") (name "DO166") (class "Default")
      (node (ref "D165") (pin "DI") (pinfunction "DI_DI") (pintype "input"))
      (node (ref "D166") (pin "DO") (pinfunction "DO_DO") (pintype "output"))
    )
    (net (code "83") (name "DO181") (class "Default")
      (node (ref "D180") (pin "DI") (pinfunction "DI_DI") (pintype "input"))
      (node (ref "D181") (pin "DO") (pinfunction "DO_DO") (pintype "output"))
    )
    (net (code "84") (name "DO196") (class "Default")
      (node (ref "D195") (pin "DI") (pinfunction "DI_DI") (pintype "input"))
      (node (ref "D196") (pin "DO") (pinfunction "DO_DO") (pintype "output"))
    )
    (net (code "85") (name "DO211") (class "Default")
      (node (ref "D210") (pin "DI") (pinfunction "DI_DI") (pintype "input"))
      (node (ref "D211") (pin "DO") (pinfunction "DO_DO") (pintype "output"))
    )
    (net (code "86") (name "DO226") (class "Default")
      (node (ref "D225") (pin "DI") (pinfunction "DI_DI") (pintype "input"))
      (node (ref "D226") (pin "DO") (pinfunction "DO_DO") (pintype "output"))
    )
    (net (code "87") (name "DO241") (class "Default")
      (node (ref "D240") (pin "DI") (pinfunction "DI_DI") (pintype "input"))
      (node (ref "D241") (pin "DO") (pinfunction "DO_DO") (pintype "output"))
    )
    (net (code "88") (name "DO256") (class "Default")
      (node (ref "D255") (pin "DI") (pinfunction "DI_DI") (pintype "input"))
      (node (ref "D256") (pin "DO") (pinfunction "DO_DO") (pintype "output"))
    )
    (net (code "89") (name "DO257") (class "Default")
      (node (ref "D256") (pin "DI") (pinfunction "DI_DI") (pintype "input"))
      (node (ref "D257") (pin "DO") (pinfunction "DO_DO") (pintype "output"))
    )
    (net (code "90") (name "DO258") (class "Default")
      (node (ref "D257") (pin "DI") (pinfunction "DI_DI") (pintype "input"))
      (node (ref "D258") (pin "DO") (pinfunction "DO_DO") (pintype "output"))
    )
    (net (code "91") (name "DO259") (class "Default")
      (node (ref "D258") (pin "DI") (pinfunction "DI_DI") (pintype "input"))
      (node (ref "D259") (pin "DO") (pinfunction "DO_DO") (pintype "output"))
    )
    (net (code "92") (name "DO260") (class "Default")
      (node (ref "D259") (pin "DI") (pinfunction "DI_DI") (pintype "input"))
      (node (ref "D260") (pin "DO") (pinfunction "DO_DO") (pintype "output"))
    )
    (net (code "93") (name "DO261") (class "Default")
      (node (ref "D260") (pin "DI") (pinfunction "DI_DI") (pintype "input"))
      (node (ref "D261") (pin "DO") (pinfunction "DO_DO") (pintype "output"))
    )
    (net (code "94") (name "DO262") (class "Default")
      (node (ref "D261") (pin "DI") (pinfunction "DI_DI") (pintype "input"))
      (node (ref "D262") (pin "DO") (pinfunction "DO_DO") (pintype "output"))
    )
    (net (code "95") (name "DO263") (class "Default")
      (node (ref "D262") (pin "DI") (pinfunction "DI_DI") (pintype "input"))
      (node (ref "D263") (pin "DO") (pinfunction "DO_DO") (pintype "output"))
    )
    (net (code "96") (name "DO264") (class "Default")
      (node (ref "D263") (pin "DI") (pinfunction "DI_DI") (pintype "input"))
      (node (ref "D264") (pin "DO") (pinfunction "DO_DO") (pintype "output"))
    )
    (net (code "97") (name "DO265") (class "Default")
      (node (ref "D264") (pin "DI") (pinfunction "DI_DI") (pintype "input"))
      (node (ref "D265") (pin "DO") (pinfunction "DO_DO") (pintype "output"))
    )
    (net (code "98") (name "DO266") (class "Default")
      (node (ref "D265") (pin "DI") (pinfunction "DI_DI") (pintype "input"))
      (node (ref "D266") (pin "DO") (pinfunction "DO_DO") (pintype "output"))
    )
    (net (code "99") (name "DO267") (class "Default")
      (node (ref "D266") (pin "DI") (pinfunction "DI_DI") (pintype "input"))
      (node (ref "D267") (pin "DO") (pinfunction "DO_DO") (pintype "output"))
    )
    (net (code "100") (name "DO268") (class "Default")
      (node (ref "D267") (pin "DI") (pinfunction "DI_DI") (pintype "input"))
      (node (ref "D268") (pin "DO") (pinfunction "DO_DO") (pintype "output"))
    )
    (net (code "101") (name "DO269") (class "Default")
      (node (ref "D268") (pin "DI") (pinfunction "DI_DI") (pintype "input"))
      (node (ref "D269") (pin "DO") (pinfunction "DO_DO") (pintype "output"))
    )
    (net (code "102") (name "DO270") (class "Default")
      (node (ref "D269") (pin "DI") (pinfunction "DI_DI") (pintype "input"))
      (node (ref "D270") (pin "DO") (pinfunction "DO_DO") (pintype "output"))
    )
    (net (code "103") (name "DO271") (class "Default")
      (node (ref "D270") (pin "DI") (pinfunction "DI_DI") (pintype "input"))
      (node (ref "D271") (pin "DO") (pinfunction "DO_DO") (pintype "output"))
    )
    (net (code "104") (name "DO272") (class "Default")
      (node (ref "D271") (pin "DI") (pinfunction "DI_DI") (pintype "input"))
      (node (ref "D272") (pin "DO") (pinfunction "DO_DO") (pintype "output"))
    )
    (net (code "105") (name "DO273") (class "Default")
      (node (ref "D272") (pin "DI") (pinfunction "DI_DI") (pintype "input"))
      (node (ref "D273") (pin "DO") (pinfunction "DO_DO") (pintype "output"))
    )
    (net (code "106") (name "DO274") (class "Default")
      (node (ref "D273") (pin "DI") (pinfunction "DI_DI") (pintype "input"))
      (node (ref "D274") (pin "DO") (pinfunction "DO_DO") (pintype "output"))
    )
    (net (code "107") (name "DO275") (class "Default")
      (node (ref "D274") (pin "DI") (pinfunction "DI_DI") (pintype "input"))
      (node (ref "D275") (pin "DO") (pinfunction "DO_DO") (pintype "output"))
    )
    (net (code "108") (name "DO276") (class "Default")
      (node (ref "D275") (pin "DI") (pinfunction "DI_DI") (pintype "input"))
      (node (ref "D276") (pin "DO") (pinfunction "DO_DO") (pintype "output"))
    )
    (net (code "109") (name "DO277") (class "Default")
      (node (ref "D276") (pin "DI") (pinfunction "DI_DI") (pintype "input"))
      (node (ref "D277") (pin "DO") (pinfunction "DO_DO") (pintype "output"))
    )
    (net (code "110") (name "DO278") (class "Default")
      (node (ref "D277") (pin "DI") (pinfunction "DI_DI") (pintype "input"))
      (node (ref "D278") (pin "DO") (pinfunction "DO_DO") (pintype "output"))
    )
    (net (code "111") (name "DO279") (class "Default")
      (node (ref "D278") (pin "DI") (pinfunction "DI_DI") (pintype "input"))
      (node (ref "D279") (pin "DO") (pinfunction "DO_DO") (pintype "output"))
    )
    (net (code "112") (name "DO280") (class "Default")
      (node (ref "D279") (pin "DI") (pinfunction "DI_DI") (pintype "input"))
      (node (ref "D280") (pin "DO") (pinfunction "DO_DO") (pintype "output"))
    )
    (net (code "113") (name "DO281") (class "Default")
      (node (ref "D280") (pin "DI") (pinfunction "DI_DI") (pintype "input"))
      (node (ref "D281") (pin "DO") (pinfunction "DO_DO") (pintype "output"))
    )
    (net (code "114") (name "DO282") (class "Default")
      (node (ref "D281") (pin "DI") (pinfunction "DI_DI") (pintype "input"))
      (node (ref "D282") (pin "DO") (pinfunction "DO_DO") (pintype "output"))
    )
    (net (code "115") (name "DO283") (class "Default")
      (node (ref "D282") (pin "DI") (pinfunction "DI_DI") (pintype "input"))
      (node (ref "D283") (pin "DO") (pinfunction "DO_DO") (pintype "output"))
    )
    (net (code "116") (name "DO284") (class "Default")
      (node (ref "D283") (pin "DI") (pinfunction "DI_DI") (pintype "input"))
      (node (ref "D284") (pin "DO") (pinfunction "DO_DO") (pintype "output"))
    )
    (net (code "117") (name "DO285") (class "Default")
      (node (ref "D284") (pin "DI") (pinfunction "DI_DI") (pintype "input"))
      (node (ref "D285") (pin "DO") (pinfunction "DO_DO") (pintype "output"))
    )
    (net (code "118") (name "DO286") (class "Default")
      (node (ref "D285") (pin "DI") (pinfunction "DI_DI") (pintype "input"))
      (node (ref "D286") (pin "DO") (pinfunction "DO_DO") (pintype "output"))
    )
    (net (code "119") (name "DO287") (class "Default")
      (node (ref "D286") (pin "DI") (pinfunction "DI_DI") (pintype "input"))
      (node (ref "D287") (pin "DO") (pinfunction "DO_DO") (pintype "output"))
    )
    (net (code "120") (name "DO288") (class "Default")
      (node (ref "D287") (pin "DI") (pinfunction "DI_DI") (pintype "input"))
      (node (ref "D288") (pin "DO") (pinfunction "DO_DO") (pintype "output"))
    )
    (net (code "121") (name "DO289") (class "Default")
      (node (ref "D288") (pin "DI") (pinfunction "DI_DI") (pintype "input"))
      (node (ref "D289") (pin "DO") (pinfunction "DO_DO") (pintype "output"))
    )
    (net (code "122") (name "DO290") (class "Default")
      (node (ref "D289") (pin "DI") (pinfunction "DI_DI") (pintype "input"))
      (node (ref "D290") (pin "DO") (pinfunction "DO_DO") (pintype "output"))
    )
    (net (code "123") (name "DO291") (class "Default")
      (node (ref "D290") (pin "DI") (pinfunction "DI_DI") (pintype "input"))
      (node (ref "D291") (pin "DO") (pinfunction "DO_DO") (pintype "output"))
    )
    (net (code "124") (name "DO292") (class "Default")
      (node (ref "D291") (pin "DI") (pinfunction "DI_DI") (pintype "input"))
      (node (ref "D292") (pin "DO") (pinfunction "DO_DO") (pintype "output"))
    )
    (net (code "125") (name "DO293") (class "Default")
      (node (ref "D292") (pin "DI") (pinfunction "DI_DI") (pintype "input"))
      (node (ref "D293") (pin "DO") (pinfunction "DO_DO") (pintype "output"))
    )
    (net (code "126") (name "DO294") (class "Default")
      (node (ref "D293") (pin "DI") (pinfunction "DI_DI") (pintype "input"))
      (node (ref "D294") (pin "DO") (pinfunction "DO_DO") (pintype "output"))
    )
    (net (code "127") (name "DO295") (class "Default")
      (node (ref "D294") (pin "DI") (pinfunction "DI_DI") (pintype "input"))
      (node (ref "D295") (pin "DO") (pinfunction "DO_DO") (pintype "output"))
    )
    (net (code "128") (name "DO296") (class "Default")
      (node (ref "D295") (pin "DI") (pinfunction "DI_DI") (pintype "input"))
      (node (ref "D296") (pin "DO") (pinfunction "DO_DO") (pintype "output"))
    )
    (net (code "129") (name "DO297") (class "Default")
      (node (ref "D296") (pin "DI") (pinfunction "DI_DI") (pintype "input"))
      (node (ref "D297") (pin "DO") (pinfunction "DO_DO") (pintype "output"))
    )
    (net (code "130") (name "DO298") (class "Default")
      (node (ref "D297") (pin "DI") (pinfunction "DI_DI") (pintype "input"))
      (node (ref "D298") (pin "DO") (pinfunction "DO_DO") (pintype "output"))
    )
    (net (code "131") (name "DO299") (class "Default")
      (node (ref "D298") (pin "DI") (pinfunction "DI_DI") (pintype "input"))
      (node (ref "D299") (pin "DO") (pinfunction "DO_DO") (pintype "output"))
    )
    (net (code "132") (name "DO300") (class "Default")
      (node (ref "D299") (pin "DI") (pinfunction "DI_DI") (pintype "input"))
      (node (ref "D300") (pin "DO") (pinfunction "DO_DO") (pintype "output"))
    )
    (net (code "133") (name "DO301") (class "Default")
      (node (ref "D300") (pin "DI") (pinfunction "DI_DI") (pintype "input"))
      (node (ref "D301") (pin "DO") (pinfunction "DO_DO") (pintype "output"))
    )
    (net (code "134") (name "DO302") (class "Default")
      (node (ref "D301") (pin "DI") (pinfunction "DI_DI") (pintype "input"))
      (node (ref "D302") (pin "DO") (pinfunction "DO_DO") (pintype "output"))
    )
    (net (code "135") (name "DO303") (class "Default")
      (node (ref "D302") (pin "DI") (pinfunction "DI_DI") (pintype "input"))
      (node (ref "D303") (pin "DO") (pinfunction "DO_DO") (pintype "output"))
    )
    (net (code "136") (name "DO304") (class "Default")
      (node (ref "D303") (pin "DI") (pinfunction "DI_DI") (pintype "input"))
      (node (ref "D304") (pin "DO") (pinfunction "DO_DO") (pintype "output"))
    )
    (net (code "137") (name "DO305") (class "Default")
      (node (ref "D304") (pin "DI") (pinfunction "DI_DI") (pintype "input"))
      (node (ref "D305") (pin "DO") (pinfunction "DO_DO") (pintype "output"))
    )
    (net (code "138") (name "DO306") (class "Default")
      (node (ref "D305") (pin "DI") (pinfunction "DI_DI") (pintype "input"))
      (node (ref "D306") (pin "DO") (pinfunction "DO_DO") (pintype "output"))
    )
    (net (code "139") (name "DO307") (class "Default")
      (node (ref "D306") (pin "DI") (pinfunction "DI_DI") (pintype "input"))
      (node (ref "D307") (pin "DO") (pinfunction "DO_DO") (pintype "output"))
    )
    (net (code "140") (name "DO308") (class "Default")
      (node (ref "D307") (pin "DI") (pinfunction "DI_DI") (pintype "input"))
      (node (ref "D308") (pin "DO") (pinfunction "DO_DO") (pintype "output"))
    )
    (net (code "141") (name "DO309") (class "Default")
      (node (ref "D308") (pin "DI") (pinfunction "DI_DI") (pintype "input"))
      (node (ref "D309") (pin "DO") (pinfunction "DO_DO") (pintype "output"))
    )
    (net (code "142") (name "DO310") (class "Default")
      (node (ref "D309") (pin "DI") (pinfunction "DI_DI") (pintype "input"))
      (node (ref "D310") (pin "DO") (pinfunction "DO_DO") (pintype "output"))
    )
    (net (code "143") (name "DO311") (class "Default")
      (node (ref "D310") (pin "DI") (pinfunction "DI_DI") (pintype "input"))
      (node (ref "D311") (pin "DO") (pinfunction "DO_DO") (pintype "output"))
    )
    (net (code "144") (name "DO312") (class "Default")
      (node (ref "D311") (pin "DI") (pinfunction "DI_DI") (pintype "input"))
      (node (ref "D312") (pin "DO") (pinfunction "DO_DO") (pintype "output"))
    )
    (net (code "145") (name "DO313") (class "Default")
      (node (ref "D312") (pin "DI") (pinfunction "DI_DI") (pintype "input"))
      (node (ref "D313") (pin "DO") (pinfunction "DO_DO") (pintype "output"))
    )
    (net (code "146") (name "DO314") (class "Default")
      (node (ref "D313") (pin "DI") (pinfunction "DI_DI") (pintype "input"))
      (node (ref "D314") (pin "DO") (pinfunction "DO_DO") (pintype "output"))
    )
    (net (code "147") (name "DO315") (class "Default")
      (node (ref "D314") (pin "DI") (pinfunction "DI_DI") (pintype "input"))
      (node (ref "D315") (pin "DO") (pinfunction "DO_DO") (pintype "output"))
    )
    (net (code "148") (name "DO316") (class "Default")
      (node (ref "D315") (pin "DI") (pinfunction "DI_DI") (pintype "input"))
      (node (ref "D316") (pin "DO") (pinfunction "DO_DO") (pintype "output"))
    )
    (net (code "149") (name "DO331") (class "Default")
      (node (ref "D330") (pin "DI") (pinfunction "DI_DI") (pintype "input"))
      (node (ref "D331") (pin "DO") (pinfunction "DO_DO") (pintype "output"))
    )
    (net (code "150") (name "DO346") (class "Default")
      (node (ref "D345") (pin "DI") (pinfunction "DI_DI") (pintype "input"))
      (node (ref "D346") (pin "DO") (pinfunction "DO_DO") (pintype "output"))
    )
    (net (code "151") (name "DO361") (class "Default")
      (node (ref "D360") (pin "DI") (pinfunction "DI_DI") (pintype "input"))
      (node (ref "D361") (pin "DO") (pinfunction "DO_DO") (pintype "output"))
    )
    (net (code "152") (name "DO376") (class "Default")
      (node (ref "D375") (pin "DI") (pinfunction "DI_DI") (pintype "input"))
      (node (ref "D376") (pin "DO") (pinfunction "DO_DO") (pintype "output"))
    )
    (net (code "153") (name "DO391") (class "Default")
      (node (ref "D390") (pin "DI") (pinfunction "DI_DI") (pintype "input"))
      (node (ref "D391") (pin "DO") (pinfunction "DO_DO") (pintype "output"))
    )
    (net (code "154") (name "GND") (class "Default")
      (node (ref "C1") (pin "-") (pinfunction "-_-") (pintype "passive"))
      (node (ref "C10") (pin "-") (pinfunction "-_-") (pintype "passive"))
      (node (ref "C100") (pin "2") (pinfunction "2_2") (pintype "passive"))
      (node (ref "C101") (pin "2") (pinfunction "2_2") (pintype "passive"))
      (node (ref "C102") (pin "2") (pinfunction "2_2") (pintype "passive"))
      (node (ref "C103") (pin "2") (pinfunction "2_2") (pintype "passive"))
      (node (ref "C104") (pin "2") (pinfunction "2_2") (pintype "passive"))
      (node (ref "C105") (pin "2") (pinfunction "2_2") (pintype "passive"))
      (node (ref "C106") (pin "2") (pinfunction "2_2") (pintype "passive"))
      (node (ref "C107") (pin "2") (pinfunction "2_2") (pintype "passive"))
      (node (ref "C108") (pin "2") (pinfunction "2_2") (pintype "passive"))
      (node (ref "C109") (pin "2") (pinfunction "2_2") (pintype "passive"))
      (node (ref "C11") (pin "-") (pinfunction "-_-") (pintype "passive"))
      (node (ref "C110") (pin "2") (pinfunction "2_2") (pintype "passive"))
      (node (ref "C111") (pin "2") (pinfunction "2_2") (pintype "passive"))
      (node (ref "C112") (pin "2") (pinfunction "2_2") (pintype "passive"))
      (node (ref "C113") (pin "2") (pinfunction "2_2") (pintype "passive"))
      (node (ref "C114") (pin "2") (pinfunction "2_2") (pintype "passive"))
      (node (ref "C115") (pin "2") (pinfunction "2_2") (pintype "passive"))
      (node (ref "C116") (pin "2") (pinfunction "2_2") (pintype "passive"))
      (node (ref "C117") (pin "2") (pinfunction "2_2") (pintype "passive"))
      (node (ref "C118") (pin "2") (pinfunction "2_2") (pintype "passive"))
      (node (ref "C119") (pin "2") (pinfunction "2_2") (pintype "passive"))
      (node (ref "C12") (pin "-") (pinfunction "-_-") (pintype "passive"))
      (node (ref "C120") (pin "2") (pinfunction "2_2") (pintype "passive"))
      (node (ref "C121") (pin "2") (pinfunction "2_2") (pintype "passive"))
      (node (ref "C122") (pin "2") (pinfunction "2_2") (pintype "passive"))
      (node (ref "C123") (pin "2") (pinfunction "2_2") (pintype "passive"))
      (node (ref "C124") (pin "2") (pinfunction "2_2") (pintype "passive"))
      (node (ref "C125") (pin "2") (pinfunction "2_2") (pintype "passive"))
      (node (ref "C126") (pin "2") (pinfunction "2_2") (pintype "passive"))
      (node (ref "C127") (pin "2") (pinfunction "2_2") (pintype "passive"))
      (node (ref "C128") (pin "2") (pinfunction "2_2") (pintype "passive"))
      (node (ref "C129") (pin "2") (pinfunction "2_2") (pintype "passive"))
      (node (ref "C13") (pin "-") (pinfunction "-_-") (pintype "passive"))
      (node (ref "C130") (pin "2") (pinfunction "2_2") (pintype "passive"))
      (node (ref "C131") (pin "2") (pinfunction "2_2") (pintype "passive"))
      (node (ref "C132") (pin "2") (pinfunction "2_2") (pintype "passive"))
      (node (ref "C133") (pin "2") (pinfunction "2_2") (pintype "passive"))
      (node (ref "C134") (pin "2") (pinfunction "2_2") (pintype "passive"))
      (node (ref "C135") (pin "2") (pinfunction "2_2") (pintype "passive"))
      (node (ref "C136") (pin "2") (pinfunction "2_2") (pintype "passive"))
      (node (ref "C137") (pin "2") (pinfunction "2_2") (pintype "passive"))
      (node (ref "C138") (pin "2") (pinfunction "2_2") (pintype "passive"))
      (node (ref "C139") (pin "2") (pinfunction "2_2") (pintype "passive"))
      (node (ref "C14") (pin "-") (pinfunction "-_-") (pintype "passive"))
      (node (ref "C140") (pin "2") (pinfunction "2_2") (pintype "passive"))
      (node (ref "C141") (pin "2") (pinfunction "2_2") (pintype "passive"))
      (node (ref "C142") (pin "2") (pinfunction "2_2") (pintype "passive"))
      (node (ref "C143") (pin "2") (pinfunction "2_2") (pintype "passive"))
      (node (ref "C144") (pin "2") (pinfunction "2_2") (pintype "passive"))
      (node (ref "C145") (pin "2") (pinfunction "2_2") (pintype "passive"))
      (node (ref "C146") (pin "2") (pinfunction "2_2") (pintype "passive"))
      (node (ref "C147") (pin "2") (pinfunction "2_2") (pintype "passive"))
      (node (ref "C148") (pin "2") (pinfunction "2_2") (pintype "passive"))
      (node (ref "C149") (pin "2") (pinfunction "2_2") (pintype "passive"))
      (node (ref "C15") (pin "-") (pinfunction "-_-") (pintype "passive"))
      (node (ref "C150") (pin "2") (pinfunction "2_2") (pintype "passive"))
      (node (ref "C151") (pin "2") (pinfunction "2_2") (pintype "passive"))
      (node (ref "C152") (pin "2") (pinfunction "2_2") (pintype "passive"))
      (node (ref "C153") (pin "2") (pinfunction "2_2") (pintype "passive"))
      (node (ref "C154") (pin "2") (pinfunction "2_2") (pintype "passive"))
      (node (ref "C155") (pin "2") (pinfunction "2_2") (pintype "passive"))
      (node (ref "C156") (pin "2") (pinfunction "2_2") (pintype "passive"))
      (node (ref "C157") (pin "2") (pinfunction "2_2") (pintype "passive"))
      (node (ref "C158") (pin "2") (pinfunction "2_2") (pintype "passive"))
      (node (ref "C159") (pin "2") (pinfunction "2_2") (pintype "passive"))
      (node (ref "C16") (pin "-") (pinfunction "-_-") (pintype "passive"))
      (node (ref "C160") (pin "2") (pinfunction "2_2") (pintype "passive"))
      (node (ref "C161") (pin "2") (pinfunction "2_2") (pintype "passive"))
      (node (ref "C162") (pin "2") (pinfunction "2_2") (pintype "passive"))
      (node (ref "C163") (pin "2") (pinfunction "2_2") (pintype "passive"))
      (node (ref "C164") (pin "2") (pinfunction "2_2") (pintype "passive"))
      (node (ref "C165") (pin "2") (pinfunction "2_2") (pintype "passive"))
      (node (ref "C166") (pin "2") (pinfunction "2_2") (pintype "passive"))
      (node (ref "C167") (pin "2") (pinfunction "2_2") (pintype "passive"))
      (node (ref "C168") (pin "2") (pinfunction "2_2") (pintype "passive"))
      (node (ref "C169") (pin "2") (pinfunction "2_2") (pintype "passive"))
      (node (ref "C17") (pin "-") (pinfunction "-_-") (pintype "passive"))
      (node (ref "C18") (pin "-") (pinfunction "-_-") (pintype "passive"))
      (node (ref "C19") (pin "-") (pinfunction "-_-") (pintype "passive"))
      (node (ref "C2") (pin "-") (pinfunction "-_-") (pintype "passive"))
      (node (ref "C20") (pin "-") (pinfunction "-_-") (pintype "passive"))
      (node (ref "C21") (pin "-") (pinfunction "-_-") (pintype "passive"))
      (node (ref "C22") (pin "-") (pinfunction "-_-") (pintype "passive"))
      (node (ref "C23") (pin "-") (pinfunction "-_-") (pintype "passive"))
      (node (ref "C24") (pin "-") (pinfunction "-_-") (pintype "passive"))
      (node (ref "C25") (pin "2") (pinfunction "2_2") (pintype "passive"))
      (node (ref "C26") (pin "2") (pinfunction "2_2") (pintype "passive"))
      (node (ref "C27") (pin "2") (pinfunction "2_2") (pintype "passive"))
      (node (ref "C28") (pin "2") (pinfunction "2_2") (pintype "passive"))
      (node (ref "C29") (pin "2") (pinfunction "2_2") (pintype "passive"))
      (node (ref "C3") (pin "-") (pinfunction "-_-") (pintype "passive"))
      (node (ref "C30") (pin "2") (pinfunction "2_2") (pintype "passive"))
      (node (ref "C31") (pin "2") (pinfunction "2_2") (pintype "passive"))
      (node (ref "C32") (pin "2") (pinfunction "2_2") (pintype "passive"))
      (node (ref "C33") (pin "2") (pinfunction "2_2") (pintype "passive"))
      (node (ref "C34") (pin "2") (pinfunction "2_2") (pintype "passive"))
      (node (ref "C35") (pin "2") (pinfunction "2_2") (pintype "passive"))
      (node (ref "C36") (pin "2") (pinfunction "2_2") (pintype "passive"))
      (node (ref "C37") (pin "2") (pinfunction "2_2") (pintype "passive"))
      (node (ref "C38") (pin "2") (pinfunction "2_2") (pintype "passive"))
      (node (ref "C39") (pin "2") (pinfunction "2_2") (pintype "passive"))
      (node (ref "C4") (pin "-") (pinfunction "-_-") (pintype "passive"))
      (node (ref "C40") (pin "2") (pinfunction "2_2") (pintype "passive"))
      (node (ref "C41") (pin "2") (pinfunction "2_2") (pintype "passive"))
      (node (ref "C42") (pin "2") (pinfunction "2_2") (pintype "passive"))
      (node (ref "C43") (pin "2") (pinfunction "2_2") (pintype "passive"))
      (node (ref "C44") (pin "2") (pinfunction "2_2") (pintype "passive"))
      (node (ref "C45") (pin "2") (pinfunction "2_2") (pintype "passive"))
      (node (ref "C46") (pin "2") (pinfunction "2_2") (pintype "passive"))
      (node (ref "C47") (pin "2") (pinfunction "2_2") (pintype "passive"))
      (node (ref "C48") (pin "2") (pinfunction "2_2") (pintype "passive"))
      (node (ref "C49") (pin "2") (pinfunction "2_2") (pintype "passive"))
      (node (ref "C5") (pin "-") (pinfunction "-_-") (pintype "passive"))
      (node (ref "C50") (pin "2") (pinfunction "2_2") (pintype "passive"))
      (node (ref "C51") (pin "2") (pinfunction "2_2") (pintype "passive"))
      (node (ref "C52") (pin "2") (pinfunction "2_2") (pintype "passive"))
      (node (ref "C53") (pin "2") (pinfunction "2_2") (pintype "passive"))
      (node (ref "C54") (pin "2") (pinfunction "2_2") (pintype "passive"))
      (node (ref "C55") (pin "2") (pinfunction "2_2") (pintype "passive"))
      (node (ref "C56") (pin "2") (pinfunction "2_2") (pintype "passive"))
      (node (ref "C57") (pin "2") (pinfunction "2_2") (pintype "passive"))
      (node (ref "C58") (pin "2") (pinfunction "2_2") (pintype "passive"))
      (node (ref "C59") (pin "2") (pinfunction "2_2") (pintype "passive"))
      (node (ref "C6") (pin "-") (pinfunction "-_-") (pintype "passive"))
      (node (ref "C60") (pin "2") (pinfunction "2_2") (pintype "passive"))
      (node (ref "C61") (pin "2") (pinfunction "2_2") (pintype "passive"))
      (node (ref "C62") (pin "2") (pinfunction "2_2") (pintype "passive"))
      (node (ref "C63") (pin "2") (pinfunction "2_2") (pintype "passive"))
      (node (ref "C64") (pin "2") (pinfunction "2_2") (pintype "passive"))
      (node (ref "C65") (pin "2") (pinfunction "2_2") (pintype "passive"))
      (node (ref "C66") (pin "2") (pinfunction "2_2") (pintype "passive"))
      (node (ref "C67") (pin "2") (pinfunction "2_2") (pintype "passive"))
      (node (ref "C68") (pin "2") (pinfunction "2_2") (pintype "passive"))
      (node (ref "C69") (pin "2") (pinfunction "2_2") (pintype "passive"))
      (node (ref "C7") (pin "-") (pinfunction "-_-") (pintype "passive"))
      (node (ref "C70") (pin "2") (pinfunction "2_2") (pintype "passive"))
      (node (ref "C71") (pin "2") (pinfunction "2_2") (pintype "passive"))
      (node (ref "C72") (pin "2") (pinfunction "2_2") (pintype "passive"))
      (node (ref "C73") (pin "2") (pinfunction "2_2") (pintype "passive"))
      (node (ref "C74") (pin "2") (pinfunction "2_2") (pintype "passive"))
      (node (ref "C75") (pin "2") (pinfunction "2_2") (pintype "passive"))
      (node (ref "C76") (pin "2") (pinfunction "2_2") (pintype "passive"))
      (node (ref "C77") (pin "2") (pinfunction "2_2") (pintype "passive"))
      (node (ref "C78") (pin "2") (pinfunction "2_2") (pintype "passive"))
      (node (ref "C79") (pin "2") (pinfunction "2_2") (pintype "passive"))
      (node (ref "C8") (pin "-") (pinfunction "-_-") (pintype "passive"))
      (node (ref "C80") (pin "2") (pinfunction "2_2") (pintype "passive"))
      (node (ref "C81") (pin "2") (pinfunction "2_2") (pintype "passive"))
      (node (ref "C82") (pin "2") (pinfunction "2_2") (pintype "passive"))
      (node (ref "C83") (pin "2") (pinfunction "2_2") (pintype "passive"))
      (node (ref "C84") (pin "2") (pinfunction "2_2") (pintype "passive"))
      (node (ref "C85") (pin "2") (pinfunction "2_2") (pintype "passive"))
      (node (ref "C86") (pin "2") (pinfunction "2_2") (pintype "passive"))
      (node (ref "C87") (pin "2") (pinfunction "2_2") (pintype "passive"))
      (node (ref "C88") (pin "2") (pinfunction "2_2") (pintype "passive"))
      (node (ref "C89") (pin "2") (pinfunction "2_2") (pintype "passive"))
      (node (ref "C9") (pin "-") (pinfunction "-_-") (pintype "passive"))
      (node (ref "C90") (pin "2") (pinfunction "2_2") (pintype "passive"))
      (node (ref "C91") (pin "2") (pinfunction "2_2") (pintype "passive"))
      (node (ref "C92") (pin "2") (pinfunction "2_2") (pintype "passive"))
      (node (ref "C93") (pin "2") (pinfunction "2_2") (pintype "passive"))
      (node (ref "C94") (pin "2") (pinfunction "2_2") (pintype "passive"))
      (node (ref "C95") (pin "2") (pinfunction "2_2") (pintype "passive"))
      (node (ref "C96") (pin "2") (pinfunction "2_2") (pintype "passive"))
      (node (ref "C97") (pin "2") (pinfunction "2_2") (pintype "passive"))
      (node (ref "C98") (pin "2") (pinfunction "2_2") (pintype "passive"))
      (node (ref "C99") (pin "2") (pinfunction "2_2") (pintype "passive"))
      (node (ref "D1") (pin "GND") (pinfunction "GND_GND") (pintype "power_in"))
      (node (ref "D10") (pin "GND") (pinfunction "GND_GND") (pintype "power_in"))
      (node (ref "D100") (pin "GND") (pinfunction "GND_GND") (pintype "power_in"))
      (node (ref "D101") (pin "GND") (pinfunction "GND_GND") (pintype "power_in"))
      (node (ref "D102") (pin "GND") (pinfunction "GND_GND") (pintype "power_in"))
      (node (ref "D103") (pin "GND") (pinfunction "GND_GND") (pintype "power_in"))
      (node (ref "D104") (pin "GND") (pinfunction "GND_GND") (pintype "power_in"))
      (node (ref "D105") (pin "GND") (pinfunction "GND_GND") (pintype "power_in"))
      (node (ref "D106") (pin "GND") (pinfunction "GND_GND") (pintype "power_in"))
      (node (ref "D107") (pin "GND") (pinfunction "GND_GND") (pintype "power_in"))
      (node (ref "D108") (pin "GND") (pinfunction "GND_GND") (pintype "power_in"))
      (node (ref "D109") (pin "GND") (pinfunction "GND_GND") (pintype "power_in"))
      (node (ref "D11") (pin "GND") (pinfunction "GND_GND") (pintype "power_in"))
      (node (ref "D110") (pin "GND") (pinfunction "GND_GND") (pintype "power_in"))
      (node (ref "D111") (pin "GND") (pinfunction "GND_GND") (pintype "power_in"))
      (node (ref "D112") (pin "GND") (pinfunction "GND_GND") (pintype "power_in"))
      (node (ref "D113") (pin "GND") (pinfunction "GND_GND") (pintype "power_in"))
      (node (ref "D114") (pin "GND") (pinfunction "GND_GND") (pintype "power_in"))
      (node (ref "D115") (pin "GND") (pinfunction "GND_GND") (pintype "power_in"))
      (node (ref "D116") (pin "GND") (pinfunction "GND_GND") (pintype "power_in"))
      (node (ref "D117") (pin "GND") (pinfunction "GND_GND") (pintype "power_in"))
      (node (ref "D118") (pin "GND") (pinfunction "GND_GND") (pintype "power_in"))
      (node (ref "D119") (pin "GND") (pinfunction "GND_GND") (pintype "power_in"))
      (node (ref "D12") (pin "GND") (pinfunction "GND_GND") (pintype "power_in"))
      (node (ref "D120") (pin "GND") (pinfunction "GND_GND") (pintype "power_in"))
      (node (ref "D121") (pin "GND") (pinfunction "GND_GND") (pintype "power_in"))
      (node (ref "D122") (pin "GND") (pinfunction "GND_GND") (pintype "power_in"))
      (node (ref "D123") (pin "GND") (pinfunction "GND_GND") (pintype "power_in"))
      (node (ref "D124") (pin "GND") (pinfunction "GND_GND") (pintype "power_in"))
      (node (ref "D125") (pin "GND") (pinfunction "GND_GND") (pintype "power_in"))
      (node (ref "D126") (pin "GND") (pinfunction "GND_GND") (pintype "power_in"))
      (node (ref "D127") (pin "GND") (pinfunction "GND_GND") (pintype "power_in"))
      (node (ref "D128") (pin "GND") (pinfunction "GND_GND") (pintype "power_in"))
      (node (ref "D129") (pin "GND") (pinfunction "GND_GND") (pintype "power_in"))
      (node (ref "D13") (pin "GND") (pinfunction "GND_GND") (pintype "power_in"))
      (node (ref "D130") (pin "GND") (pinfunction "GND_GND") (pintype "power_in"))
      (node (ref "D131") (pin "GND") (pinfunction "GND_GND") (pintype "power_in"))
      (node (ref "D132") (pin "GND") (pinfunction "GND_GND") (pintype "power_in"))
      (node (ref "D133") (pin "GND") (pinfunction "GND_GND") (pintype "power_in"))
      (node (ref "D134") (pin "GND") (pinfunction "GND_GND") (pintype "power_in"))
      (node (ref "D135") (pin "GND") (pinfunction "GND_GND") (pintype "power_in"))
      (node (ref "D136") (pin "GND") (pinfunction "GND_GND") (pintype "power_in"))
      (node (ref "D137") (pin "GND") (pinfunction "GND_GND") (pintype "power_in"))
      (node (ref "D138") (pin "GND") (pinfunction "GND_GND") (pintype "power_in"))
      (node (ref "D139") (pin "GND") (pinfunction "GND_GND") (pintype "power_in"))
      (node (ref "D14") (pin "GND") (pinfunction "GND_GND") (pintype "power_in"))
      (node (ref "D140") (pin "GND") (pinfunction "GND_GND") (pintype "power_in"))
      (node (ref "D141") (pin "GND") (pinfunction "GND_GND") (pintype "power_in"))
      (node (ref "D142") (pin "GND") (pinfunction "GND_GND") (pintype "power_in"))
      (node (ref "D143") (pin "GND") (pinfunction "GND_GND") (pintype "power_in"))
      (node (ref "D144") (pin "GND") (pinfunction "GND_GND") (pintype "power_in"))
      (node (ref "D145") (pin "GND") (pinfunction "GND_GND") (pintype "power_in"))
      (node (ref "D146") (pin "GND") (pinfunction "GND_GND") (pintype "power_in"))
      (node (ref "D147") (pin "GND") (pinfunction "GND_GND") (pintype "power_in"))
      (node (ref "D148") (pin "GND") (pinfunction "GND_GND") (pintype "power_in"))
      (node (ref "D149") (pin "GND") (pinfunction "GND_GND") (pintype "power_in"))
      (node (ref "D15") (pin "GND") (pinfunction "GND_GND") (pintype "power_in"))
      (node (ref "D150") (pin "GND") (pinfunction "GND_GND") (pintype "power_in"))
      (node (ref "D151") (pin "GND") (pinfunction "GND_GND") (pintype "power_in"))
      (node (ref "D152") (pin "GND") (pinfunction "GND_GND") (pintype "power_in"))
      (node (ref "D153") (pin "GND") (pinfunction "GND_GND") (pintype "power_in"))
      (node (ref "D154") (pin "GND") (pinfunction "GND_GND") (pintype "power_in"))
      (node (ref "D155") (pin "GND") (pinfunction "GND_GND") (pintype "power_in"))
      (node (ref "D156") (pin "GND") (pinfunction "GND_GND") (pintype "power_in"))
      (node (ref "D157") (pin "GND") (pinfunction "GND_GND") (pintype "power_in"))
      (node (ref "D158") (pin "GND") (pinfunction "GND_GND") (pintype "power_in"))
      (node (ref "D159") (pin "GND") (pinfunction "GND_GND") (pintype "power_in"))
      (node (ref "D16") (pin "GND") (pinfunction "GND_GND") (pintype "power_in"))
      (node (ref "D160") (pin "GND") (pinfunction "GND_GND") (pintype "power_in"))
      (node (ref "D161") (pin "GND") (pinfunction "GND_GND") (pintype "power_in"))
      (node (ref "D162") (pin "GND") (pinfunction "GND_GND") (pintype "power_in"))
      (node (ref "D163") (pin "GND") (pinfunction "GND_GND") (pintype "power_in"))
      (node (ref "D164") (pin "GND") (pinfunction "GND_GND") (pintype "power_in"))
      (node (ref "D165") (pin "GND") (pinfunction "GND_GND") (pintype "power_in"))
      (node (ref "D166") (pin "GND") (pinfunction "GND_GND") (pintype "power_in"))
      (node (ref "D167") (pin "GND") (pinfunction "GND_GND") (pintype "power_in"))
      (node (ref "D168") (pin "GND") (pinfunction "GND_GND") (pintype "power_in"))
      (node (ref "D169") (pin "GND") (pinfunction "GND_GND") (pintype "power_in"))
      (node (ref "D17") (pin "GND") (pinfunction "GND_GND") (pintype "power_in"))
      (node (ref "D170") (pin "GND") (pinfunction "GND_GND") (pintype "power_in"))
      (node (ref "D171") (pin "GND") (pinfunction "GND_GND") (pintype "power_in"))
      (node (ref "D172") (pin "GND") (pinfunction "GND_GND") (pintype "power_in"))
      (node (ref "D173") (pin "GND") (pinfunction "GND_GND") (pintype "power_in"))
      (node (ref "D174") (pin "GND") (pinfunction "GND_GND") (pintype "power_in"))
      (node (ref "D175") (pin "GND") (pinfunction "GND_GND") (pintype "power_in"))
      (node (ref "D176") (pin "GND") (pinfunction "GND_GND") (pintype "power_in"))
      (node (ref "D177") (pin "GND") (pinfunction "GND_GND") (pintype "power_in"))
      (node (ref "D178") (pin "GND") (pinfunction "GND_GND") (pintype "power_in"))
      (node (ref "D179") (pin "GND") (pinfunction "GND_GND") (pintype "power_in"))
      (node (ref "D18") (pin "GND") (pinfunction "GND_GND") (pintype "power_in"))
      (node (ref "D180") (pin "GND") (pinfunction "GND_GND") (pintype "power_in"))
      (node (ref "D181") (pin "GND") (pinfunction "GND_GND") (pintype "power_in"))
      (node (ref "D182") (pin "GND") (pinfunction "GND_GND") (pintype "power_in"))
      (node (ref "D183") (pin "GND") (pinfunction "GND_GND") (pintype "power_in"))
      (node (ref "D184") (pin "GND") (pinfunction "GND_GND") (pintype "power_in"))
      (node (ref "D185") (pin "GND") (pinfunction "GND_GND") (pintype "power_in"))
      (node (ref "D186") (pin "GND") (pinfunction "GND_GND") (pintype "power_in"))
      (node (ref "D187") (pin "GND") (pinfunction "GND_GND") (pintype "power_in"))
      (node (ref "D188") (pin "GND") (pinfunction "GND_GND") (pintype "power_in"))
      (node (ref "D189") (pin "GND") (pinfunction "GND_GND") (pintype "power_in"))
      (node (ref "D19") (pin "GND") (pinfunction "GND_GND") (pintype "power_in"))
      (node (ref "D190") (pin "GND") (pinfunction "GND_GND") (pintype "power_in"))
      (node (ref "D191") (pin "GND") (pinfunction "GND_GND") (pintype "power_in"))
      (node (ref "D192") (pin "GND") (pinfunction "GND_GND") (pintype "power_in"))
      (node (ref "D193") (pin "GND") (pinfunction "GND_GND") (pintype "power_in"))
      (node (ref "D194") (pin "GND") (pinfunction "GND_GND") (pintype "power_in"))
      (node (ref "D195") (pin "GND") (pinfunction "GND_GND") (pintype "power_in"))
      (node (ref "D196") (pin "GND") (pinfunction "GND_GND") (pintype "power_in"))
      (node (ref "D197") (pin "GND") (pinfunction "GND_GND") (pintype "power_in"))
      (node (ref "D198") (pin "GND") (pinfunction "GND_GND") (pintype "power_in"))
      (node (ref "D199") (pin "GND") (pinfunction "GND_GND") (pintype "power_in"))
      (node (ref "D2") (pin "GND") (pinfunction "GND_GND") (pintype "power_in"))
      (node (ref "D20") (pin "GND") (pinfunction "GND_GND") (pintype "power_in"))
      (node (ref "D200") (pin "GND") (pinfunction "GND_GND") (pintype "power_in"))
      (node (ref "D201") (pin "GND") (pinfunction "GND_GND") (pintype "power_in"))
      (node (ref "D202") (pin "GND") (pinfunction "GND_GND") (pintype "power_in"))
      (node (ref "D203") (pin "GND") (pinfunction "GND_GND") (pintype "power_in"))
      (node (ref "D204") (pin "GND") (pinfunction "GND_GND") (pintype "power_in"))
      (node (ref "D205") (pin "GND") (pinfunction "GND_GND") (pintype "power_in"))
      (node (ref "D206") (pin "GND") (pinfunction "GND_GND") (pintype "power_in"))
      (node (ref "D207") (pin "GND") (pinfunction "GND_GND") (pintype "power_in"))
      (node (ref "D208") (pin "GND") (pinfunction "GND_GND") (pintype "power_in"))
      (node (ref "D209") (pin "GND") (pinfunction "GND_GND") (pintype "power_in"))
      (node (ref "D21") (pin "GND") (pinfunction "GND_GND") (pintype "power_in"))
      (node (ref "D210") (pin "GND") (pinfunction "GND_GND") (pintype "power_in"))
      (node (ref "D211") (pin "GND") (pinfunction "GND_GND") (pintype "power_in"))
      (node (ref "D212") (pin "GND") (pinfunction "GND_GND") (pintype "power_in"))
      (node (ref "D213") (pin "GND") (pinfunction "GND_GND") (pintype "power_in"))
      (node (ref "D214") (pin "GND") (pinfunction "GND_GND") (pintype "power_in"))
      (node (ref "D215") (pin "GND") (pinfunction "GND_GND") (pintype "power_in"))
      (node (ref "D216") (pin "GND") (pinfunction "GND_GND") (pintype "power_in"))
      (node (ref "D217") (pin "GND") (pinfunction "GND_GND") (pintype "power_in"))
      (node (ref "D218") (pin "GND") (pinfunction "GND_GND") (pintype "power_in"))
      (node (ref "D219") (pin "GND") (pinfunction "GND_GND") (pintype "power_in"))
      (node (ref "D22") (pin "GND") (pinfunction "GND_GND") (pintype "power_in"))
      (node (ref "D220") (pin "GND") (pinfunction "GND_GND") (pintype "power_in"))
      (node (ref "D221") (pin "GND") (pinfunction "GND_GND") (pintype "power_in"))
      (node (ref "D222") (pin "GND") (pinfunction "GND_GND") (pintype "power_in"))
      (node (ref "D223") (pin "GND") (pinfunction "GND_GND") (pintype "power_in"))
      (node (ref "D224") (pin "GND") (pinfunction "GND_GND") (pintype "power_in"))
      (node (ref "D225") (pin "GND") (pinfunction "GND_GND") (pintype "power_in"))
      (node (ref "D226") (pin "GND") (pinfunction "GND_GND") (pintype "power_in"))
      (node (ref "D227") (pin "GND") (pinfunction "GND_GND") (pintype "power_in"))
      (node (ref "D228") (pin "GND") (pinfunction "GND_GND") (pintype "power_in"))
      (node (ref "D229") (pin "GND") (pinfunction "GND_GND") (pintype "power_in"))
      (node (ref "D23") (pin "GND") (pinfunction "GND_GND") (pintype "power_in"))
      (node (ref "D230") (pin "GND") (pinfunction "GND_GND") (pintype "power_in"))
      (node (ref "D231") (pin "GND") (pinfunction "GND_GND") (pintype "power_in"))
      (node (ref "D232") (pin "GND") (pinfunction "GND_GND") (pintype "power_in"))
      (node (ref "D233") (pin "GND") (pinfunction "GND_GND") (pintype "power_in"))
      (node (ref "D234") (pin "GND") (pinfunction "GND_GND") (pintype "power_in"))
      (node (ref "D235") (pin "GND") (pinfunction "GND_GND") (pintype "power_in"))
      (node (ref "D236") (pin "GND") (pinfunction "GND_GND") (pintype "power_in"))
      (node (ref "D237") (pin "GND") (pinfunction "GND_GND") (pintype "power_in"))
      (node (ref "D238") (pin "GND") (pinfunction "GND_GND") (pintype "power_in"))
      (node (ref "D239") (pin "GND") (pinfunction "GND_GND") (pintype "power_in"))
      (node (ref "D24") (pin "GND") (pinfunction "GND_GND") (pintype "power_in"))
      (node (ref "D240") (pin "GND") (pinfunction "GND_GND") (pintype "power_in"))
      (node (ref "D241") (pin "GND") (pinfunction "GND_GND") (pintype "power_in"))
      (node (ref "D242") (pin "GND") (pinfunction "GND_GND") (pintype "power_in"))
      (node (ref "D243") (pin "GND") (pinfunction "GND_GND") (pintype "power_in"))
      (node (ref "D244") (pin "GND") (pinfunction "GND_GND") (pintype "power_in"))
      (node (ref "D245") (pin "GND") (pinfunction "GND_GND") (pintype "power_in"))
      (node (ref "D246") (pin "GND") (pinfunction "GND_GND") (pintype "power_in"))
      (node (ref "D247") (pin "GND") (pinfunction "GND_GND") (pintype "power_in"))
      (node (ref "D248") (pin "GND") (pinfunction "GND_GND") (pintype "power_in"))
      (node (ref "D249") (pin "GND") (pinfunction "GND_GND") (pintype "power_in"))
      (node (ref "D25") (pin "GND") (pinfunction "GND_GND") (pintype "power_in"))
      (node (ref "D250") (pin "GND") (pinfunction "GND_GND") (pintype "power_in"))
      (node (ref "D251") (pin "GND") (pinfunction "GND_GND") (pintype "power_in"))
      (node (ref "D252") (pin "GND") (pinfunction "GND_GND") (pintype "power_in"))
      (node (ref "D253") (pin "GND") (pinfunction "GND_GND") (pintype "power_in"))
      (node (ref "D254") (pin "GND") (pinfunction "GND_GND") (pintype "power_in"))
      (node (ref "D255") (pin "GND") (pinfunction "GND_GND") (pintype "power_in"))
      (node (ref "D256") (pin "GND") (pinfunction "GND_GND") (pintype "power_in"))
      (node (ref "D257") (pin "GND") (pinfunction "GND_GND") (pintype "power_in"))
      (node (ref "D258") (pin "GND") (pinfunction "GND_GND") (pintype "power_in"))
      (node (ref "D259") (pin "GND") (pinfunction "GND_GND") (pintype "power_in"))
      (node (ref "D26") (pin "GND") (pinfunction "GND_GND") (pintype "power_in"))
      (node (ref "D260") (pin "GND") (pinfunction "GND_GND") (pintype "power_in"))
      (node (ref "D261") (pin "GND") (pinfunction "GND_GND") (pintype "power_in"))
      (node (ref "D262") (pin "GND") (pinfunction "GND_GND") (pintype "power_in"))
      (node (ref "D263") (pin "GND") (pinfunction "GND_GND") (pintype "power_in"))
      (node (ref "D264") (pin "GND") (pinfunction "GND_GND") (pintype "power_in"))
      (node (ref "D265") (pin "GND") (pinfunction "GND_GND") (pintype "power_in"))
      (node (ref "D266") (pin "GND") (pinfunction "GND_GND") (pintype "power_in"))
      (node (ref "D267") (pin "GND") (pinfunction "GND_GND") (pintype "power_in"))
      (node (ref "D268") (pin "GND") (pinfunction "GND_GND") (pintype "power_in"))
      (node (ref "D269") (pin "GND") (pinfunction "GND_GND") (pintype "power_in"))
      (node (ref "D27") (pin "GND") (pinfunction "GND_GND") (pintype "power_in"))
      (node (ref "D270") (pin "GND") (pinfunction "GND_GND") (pintype "power_in"))
      (node (ref "D271") (pin "GND") (pinfunction "GND_GND") (pintype "power_in"))
      (node (ref "D272") (pin "GND") (pinfunction "GND_GND") (pintype "power_in"))
      (node (ref "D273") (pin "GND") (pinfunction "GND_GND") (pintype "power_in"))
      (node (ref "D274") (pin "GND") (pinfunction "GND_GND") (pintype "power_in"))
      (node (ref "D275") (pin "GND") (pinfunction "GND_GND") (pintype "power_in"))
      (node (ref "D276") (pin "GND") (pinfunction "GND_GND") (pintype "power_in"))
      (node (ref "D277") (pin "GND") (pinfunction "GND_GND") (pintype "power_in"))
      (node (ref "D278") (pin "GND") (pinfunction "GND_GND") (pintype "power_in"))
      (node (ref "D279") (pin "GND") (pinfunction "GND_GND") (pintype "power_in"))
      (node (ref "D28") (pin "GND") (pinfunction "GND_GND") (pintype "power_in"))
      (node (ref "D280") (pin "GND") (pinfunction "GND_GND") (pintype "power_in"))
      (node (ref "D281") (pin "GND") (pinfunction "GND_GND") (pintype "power_in"))
      (node (ref "D282") (pin "GND") (pinfunction "GND_GND") (pintype "power_in"))
      (node (ref "D283") (pin "GND") (pinfunction "GND_GND") (pintype "power_in"))
      (node (ref "D284") (pin "GND") (pinfunction "GND_GND") (pintype "power_in"))
      (node (ref "D285") (pin "GND") (pinfunction "GND_GND") (pintype "power_in"))
      (node (ref "D286") (pin "GND") (pinfunction "GND_GND") (pintype "power_in"))
      (node (ref "D287") (pin "GND") (pinfunction "GND_GND") (pintype "power_in"))
      (node (ref "D288") (pin "GND") (pinfunction "GND_GND") (pintype "power_in"))
      (node (ref "D289") (pin "GND") (pinfunction "GND_GND") (pintype "power_in"))
      (node (ref "D29") (pin "GND") (pinfunction "GND_GND") (pintype "power_in"))
      (node (ref "D290") (pin "GND") (pinfunction "GND_GND") (pintype "power_in"))
      (node (ref "D291") (pin "GND") (pinfunction "GND_GND") (pintype "power_in"))
      (node (ref "D292") (pin "GND") (pinfunction "GND_GND") (pintype "power_in"))
      (node (ref "D293") (pin "GND") (pinfunction "GND_GND") (pintype "power_in"))
      (node (ref "D294") (pin "GND") (pinfunction "GND_GND") (pintype "power_in"))
      (node (ref "D295") (pin "GND") (pinfunction "GND_GND") (pintype "power_in"))
      (node (ref "D296") (pin "GND") (pinfunction "GND_GND") (pintype "power_in"))
      (node (ref "D297") (pin "GND") (pinfunction "GND_GND") (pintype "power_in"))
      (node (ref "D298") (pin "GND") (pinfunction "GND_GND") (pintype "power_in"))
      (node (ref "D299") (pin "GND") (pinfunction "GND_GND") (pintype "power_in"))
      (node (ref "D3") (pin "GND") (pinfunction "GND_GND") (pintype "power_in"))
      (node (ref "D30") (pin "GND") (pinfunction "GND_GND") (pintype "power_in"))
      (node (ref "D300") (pin "GND") (pinfunction "GND_GND") (pintype "power_in"))
      (node (ref "D301") (pin "GND") (pinfunction "GND_GND") (pintype "power_in"))
      (node (ref "D302") (pin "GND") (pinfunction "GND_GND") (pintype "power_in"))
      (node (ref "D303") (pin "GND") (pinfunction "GND_GND") (pintype "power_in"))
      (node (ref "D304") (pin "GND") (pinfunction "GND_GND") (pintype "power_in"))
      (node (ref "D305") (pin "GND") (pinfunction "GND_GND") (pintype "power_in"))
      (node (ref "D306") (pin "GND") (pinfunction "GND_GND") (pintype "power_in"))
      (node (ref "D307") (pin "GND") (pinfunction "GND_GND") (pintype "power_in"))
      (node (ref "D308") (pin "GND") (pinfunction "GND_GND") (pintype "power_in"))
      (node (ref "D309") (pin "GND") (pinfunction "GND_GND") (pintype "power_in"))
      (node (ref "D31") (pin "GND") (pinfunction "GND_GND") (pintype "power_in"))
      (node (ref "D310") (pin "GND") (pinfunction "GND_GND") (pintype "power_in"))
      (node (ref "D311") (pin "GND") (pinfunction "GND_GND") (pintype "power_in"))
      (node (ref "D312") (pin "GND") (pinfunction "GND_GND") (pintype "power_in"))
      (node (ref "D313") (pin "GND") (pinfunction "GND_GND") (pintype "power_in"))
      (node (ref "D314") (pin "GND") (pinfunction "GND_GND") (pintype "power_in"))
      (node (ref "D315") (pin "GND") (pinfunction "GND_GND") (pintype "power_in"))
      (node (ref "D316") (pin "GND") (pinfunction "GND_GND") (pintype "power_in"))
      (node (ref "D317") (pin "GND") (pinfunction "GND_GND") (pintype "power_in"))
      (node (ref "D318") (pin "GND") (pinfunction "GND_GND") (pintype "power_in"))
      (node (ref "D319") (pin "GND") (pinfunction "GND_GND") (pintype "power_in"))
      (node (ref "D32") (pin "GND") (pinfunction "GND_GND") (pintype "power_in"))
      (node (ref "D320") (pin "GND") (pinfunction "GND_GND") (pintype "power_in"))
      (node (ref "D321") (pin "GND") (pinfunction "GND_GND") (pintype "power_in"))
      (node (ref "D322") (pin "GND") (pinfunction "GND_GND") (pintype "power_in"))
      (node (ref "D323") (pin "GND") (pinfunction "GND_GND") (pintype "power_in"))
      (node (ref "D324") (pin "GND") (pinfunction "GND_GND") (pintype "power_in"))
      (node (ref "D325") (pin "GND") (pinfunction "GND_GND") (pintype "power_in"))
      (node (ref "D326") (pin "GND") (pinfunction "GND_GND") (pintype "power_in"))
      (node (ref "D327") (pin "GND") (pinfunction "GND_GND") (pintype "power_in"))
      (node (ref "D328") (pin "GND") (pinfunction "GND_GND") (pintype "power_in"))
      (node (ref "D329") (pin "GND") (pinfunction "GND_GND") (pintype "power_in"))
      (node (ref "D33") (pin "GND") (pinfunction "GND_GND") (pintype "power_in"))
      (node (ref "D330") (pin "GND") (pinfunction "GND_GND") (pintype "power_in"))
      (node (ref "D331") (pin "GND") (pinfunction "GND_GND") (pintype "power_in"))
      (node (ref "D332") (pin "GND") (pinfunction "GND_GND") (pintype "power_in"))
      (node (ref "D333") (pin "GND") (pinfunction "GND_GND") (pintype "power_in"))
      (node (ref "D334") (pin "GND") (pinfunction "GND_GND") (pintype "power_in"))
      (node (ref "D335") (pin "GND") (pinfunction "GND_GND") (pintype "power_in"))
      (node (ref "D336") (pin "GND") (pinfunction "GND_GND") (pintype "power_in"))
      (node (ref "D337") (pin "GND") (pinfunction "GND_GND") (pintype "power_in"))
      (node (ref "D338") (pin "GND") (pinfunction "GND_GND") (pintype "power_in"))
      (node (ref "D339") (pin "GND") (pinfunction "GND_GND") (pintype "power_in"))
      (node (ref "D34") (pin "GND") (pinfunction "GND_GND") (pintype "power_in"))
      (node (ref "D340") (pin "GND") (pinfunction "GND_GND") (pintype "power_in"))
      (node (ref "D341") (pin "GND") (pinfunction "GND_GND") (pintype "power_in"))
      (node (ref "D342") (pin "GND") (pinfunction "GND_GND") (pintype "power_in"))
      (node (ref "D343") (pin "GND") (pinfunction "GND_GND") (pintype "power_in"))
      (node (ref "D344") (pin "GND") (pinfunction "GND_GND") (pintype "power_in"))
      (node (ref "D345") (pin "GND") (pinfunction "GND_GND") (pintype "power_in"))
      (node (ref "D346") (pin "GND") (pinfunction "GND_GND") (pintype "power_in"))
      (node (ref "D347") (pin "GND") (pinfunction "GND_GND") (pintype "power_in"))
      (node (ref "D348") (pin "GND") (pinfunction "GND_GND") (pintype "power_in"))
      (node (ref "D349") (pin "GND") (pinfunction "GND_GND") (pintype "power_in"))
      (node (ref "D35") (pin "GND") (pinfunction "GND_GND") (pintype "power_in"))
      (node (ref "D350") (pin "GND") (pinfunction "GND_GND") (pintype "power_in"))
      (node (ref "D351") (pin "GND") (pinfunction "GND_GND") (pintype "power_in"))
      (node (ref "D352") (pin "GND") (pinfunction "GND_GND") (pintype "power_in"))
      (node (ref "D353") (pin "GND") (pinfunction "GND_GND") (pintype "power_in"))
      (node (ref "D354") (pin "GND") (pinfunction "GND_GND") (pintype "power_in"))
      (node (ref "D355") (pin "GND") (pinfunction "GND_GND") (pintype "power_in"))
      (node (ref "D356") (pin "GND") (pinfunction "GND_GND") (pintype "power_in"))
      (node (ref "D357") (pin "GND") (pinfunction "GND_GND") (pintype "power_in"))
      (node (ref "D358") (pin "GND") (pinfunction "GND_GND") (pintype "power_in"))
      (node (ref "D359") (pin "GND") (pinfunction "GND_GND") (pintype "power_in"))
      (node (ref "D36") (pin "GND") (pinfunction "GND_GND") (pintype "power_in"))
      (node (ref "D360") (pin "GND") (pinfunction "GND_GND") (pintype "power_in"))
      (node (ref "D361") (pin "GND") (pinfunction "GND_GND") (pintype "power_in"))
      (node (ref "D362") (pin "GND") (pinfunction "GND_GND") (pintype "power_in"))
      (node (ref "D363") (pin "GND") (pinfunction "GND_GND") (pintype "power_in"))
      (node (ref "D364") (pin "GND") (pinfunction "GND_GND") (pintype "power_in"))
      (node (ref "D365") (pin "GND") (pinfunction "GND_GND") (pintype "power_in"))
      (node (ref "D366") (pin "GND") (pinfunction "GND_GND") (pintype "power_in"))
      (node (ref "D367") (pin "GND") (pinfunction "GND_GND") (pintype "power_in"))
      (node (ref "D368") (pin "GND") (pinfunction "GND_GND") (pintype "power_in"))
      (node (ref "D369") (pin "GND") (pinfunction "GND_GND") (pintype "power_in"))
      (node (ref "D37") (pin "GND") (pinfunction "GND_GND") (pintype "power_in"))
      (node (ref "D370") (pin "GND") (pinfunction "GND_GND") (pintype "power_in"))
      (node (ref "D371") (pin "GND") (pinfunction "GND_GND") (pintype "power_in"))
      (node (ref "D372") (pin "GND") (pinfunction "GND_GND") (pintype "power_in"))
      (node (ref "D373") (pin "GND") (pinfunction "GND_GND") (pintype "power_in"))
      (node (ref "D374") (pin "GND") (pinfunction "GND_GND") (pintype "power_in"))
      (node (ref "D375") (pin "GND") (pinfunction "GND_GND") (pintype "power_in"))
      (node (ref "D376") (pin "GND") (pinfunction "GND_GND") (pintype "power_in"))
      (node (ref "D377") (pin "GND") (pinfunction "GND_GND") (pintype "power_in"))
      (node (ref "D378") (pin "GND") (pinfunction "GND_GND") (pintype "power_in"))
      (node (ref "D379") (pin "GND") (pinfunction "GND_GND") (pintype "power_in"))
      (node (ref "D38") (pin "GND") (pinfunction "GND_GND") (pintype "power_in"))
      (node (ref "D380") (pin "GND") (pinfunction "GND_GND") (pintype "power_in"))
      (node (ref "D381") (pin "GND") (pinfunction "GND_GND") (pintype "power_in"))
      (node (ref "D382") (pin "GND") (pinfunction "GND_GND") (pintype "power_in"))
      (node (ref "D383") (pin "GND") (pinfunction "GND_GND") (pintype "power_in"))
      (node (ref "D384") (pin "GND") (pinfunction "GND_GND") (pintype "power_in"))
      (node (ref "D385") (pin "GND") (pinfunction "GND_GND") (pintype "power_in"))
      (node (ref "D386") (pin "GND") (pinfunction "GND_GND") (pintype "power_in"))
      (node (ref "D387") (pin "GND") (pinfunction "GND_GND") (pintype "power_in"))
      (node (ref "D388") (pin "GND") (pinfunction "GND_GND") (pintype "power_in"))
      (node (ref "D389") (pin "GND") (pinfunction "GND_GND") (pintype "power_in"))
      (node (ref "D39") (pin "GND") (pinfunction "GND_GND") (pintype "power_in"))
      (node (ref "D390") (pin "GND") (pinfunction "GND_GND") (pintype "power_in"))
      (node (ref "D391") (pin "GND") (pinfunction "GND_GND") (pintype "power_in"))
      (node (ref "D392") (pin "GND") (pinfunction "GND_GND") (pintype "power_in"))
      (node (ref "D393") (pin "GND") (pinfunction "GND_GND") (pintype "power_in"))
      (node (ref "D394") (pin "GND") (pinfunction "GND_GND") (pintype "power_in"))
      (node (ref "D395") (pin "GND") (pinfunction "GND_GND") (pintype "power_in"))
      (node (ref "D396") (pin "GND") (pinfunction "GND_GND") (pintype "power_in"))
      (node (ref "D397") (pin "GND") (pinfunction "GND_GND") (pintype "power_in"))
      (node (ref "D398") (pin "GND") (pinfunction "GND_GND") (pintype "power_in"))
      (node (ref "D399") (pin "GND") (pinfunction "GND_GND") (pintype "power_in"))
      (node (ref "D4") (pin "GND") (pinfunction "GND_GND") (pintype "power_in"))
      (node (ref "D40") (pin "GND") (pinfunction "GND_GND") (pintype "power_in"))
      (node (ref "D400") (pin "GND") (pinfunction "GND_GND") (pintype "power_in"))
      (node (ref "D401") (pin "GND") (pinfunction "GND_GND") (pintype "power_in"))
      (node (ref "D402") (pin "GND") (pinfunction "GND_GND") (pintype "power_in"))
      (node (ref "D403") (pin "GND") (pinfunction "GND_GND") (pintype "power_in"))
      (node (ref "D404") (pin "GND") (pinfunction "GND_GND") (pintype "power_in"))
      (node (ref "D405") (pin "GND") (pinfunction "GND_GND") (pintype "power_in"))
      (node (ref "D41") (pin "GND") (pinfunction "GND_GND") (pintype "power_in"))
      (node (ref "D42") (pin "GND") (pinfunction "GND_GND") (pintype "power_in"))
      (node (ref "D43") (pin "GND") (pinfunction "GND_GND") (pintype "power_in"))
      (node (ref "D44") (pin "GND") (pinfunction "GND_GND") (pintype "power_in"))
      (node (ref "D45") (pin "GND") (pinfunction "GND_GND") (pintype "power_in"))
      (node (ref "D46") (pin "GND") (pinfunction "GND_GND") (pintype "power_in"))
      (node (ref "D47") (pin "GND") (pinfunction "GND_GND") (pintype "power_in"))
      (node (ref "D48") (pin "GND") (pinfunction "GND_GND") (pintype "power_in"))
      (node (ref "D49") (pin "GND") (pinfunction "GND_GND") (pintype "power_in"))
      (node (ref "D5") (pin "GND") (pinfunction "GND_GND") (pintype "power_in"))
      (node (ref "D50") (pin "GND") (pinfunction "GND_GND") (pintype "power_in"))
      (node (ref "D51") (pin "GND") (pinfunction "GND_GND") (pintype "power_in"))
      (node (ref "D52") (pin "GND") (pinfunction "GND_GND") (pintype "power_in"))
      (node (ref "D53") (pin "GND") (pinfunction "GND_GND") (pintype "power_in"))
      (node (ref "D54") (pin "GND") (pinfunction "GND_GND") (pintype "power_in"))
      (node (ref "D55") (pin "GND") (pinfunction "GND_GND") (pintype "power_in"))
      (node (ref "D56") (pin "GND") (pinfunction "GND_GND") (pintype "power_in"))
      (node (ref "D57") (pin "GND") (pinfunction "GND_GND") (pintype "power_in"))
      (node (ref "D58") (pin "GND") (pinfunction "GND_GND") (pintype "power_in"))
      (node (ref "D59") (pin "GND") (pinfunction "GND_GND") (pintype "power_in"))
      (node (ref "D6") (pin "GND") (pinfunction "GND_GND") (pintype "power_in"))
      (node (ref "D60") (pin "GND") (pinfunction "GND_GND") (pintype "power_in"))
      (node (ref "D61") (pin "GND") (pinfunction "GND_GND") (pintype "power_in"))
      (node (ref "D62") (pin "GND") (pinfunction "GND_GND") (pintype "power_in"))
      (node (ref "D63") (pin "GND") (pinfunction "GND_GND") (pintype "power_in"))
      (node (ref "D64") (pin "GND") (pinfunction "GND_GND") (pintype "power_in"))
      (node (ref "D65") (pin "GND") (pinfunction "GND_GND") (pintype "power_in"))
      (node (ref "D66") (pin "GND") (pinfunction "GND_GND") (pintype "power_in"))
      (node (ref "D67") (pin "GND") (pinfunction "GND_GND") (pintype "power_in"))
      (node (ref "D68") (pin "GND") (pinfunction "GND_GND") (pintype "power_in"))
      (node (ref "D69") (pin "GND") (pinfunction "GND_GND") (pintype "power_in"))
      (node (ref "D7") (pin "GND") (pinfunction "GND_GND") (pintype "power_in"))
      (node (ref "D70") (pin "GND") (pinfunction "GND_GND") (pintype "power_in"))
      (node (ref "D71") (pin "GND") (pinfunction "GND_GND") (pintype "power_in"))
      (node (ref "D72") (pin "GND") (pinfunction "GND_GND") (pintype "power_in"))
      (node (ref "D73") (pin "GND") (pinfunction "GND_GND") (pintype "power_in"))
      (node (ref "D74") (pin "GND") (pinfunction "GND_GND") (pintype "power_in"))
      (node (ref "D75") (pin "GND") (pinfunction "GND_GND") (pintype "power_in"))
      (node (ref "D76") (pin "GND") (pinfunction "GND_GND") (pintype "power_in"))
      (node (ref "D77") (pin "GND") (pinfunction "GND_GND") (pintype "power_in"))
      (node (ref "D78") (pin "GND") (pinfunction "GND_GND") (pintype "power_in"))
      (node (ref "D79") (pin "GND") (pinfunction "GND_GND") (pintype "power_in"))
      (node (ref "D8") (pin "GND") (pinfunction "GND_GND") (pintype "power_in"))
      (node (ref "D80") (pin "GND") (pinfunction "GND_GND") (pintype "power_in"))
      (node (ref "D81") (pin "GND") (pinfunction "GND_GND") (pintype "power_in"))
      (node (ref "D82") (pin "GND") (pinfunction "GND_GND") (pintype "power_in"))
      (node (ref "D83") (pin "GND") (pinfunction "GND_GND") (pintype "power_in"))
      (node (ref "D84") (pin "GND") (pinfunction "GND_GND") (pintype "power_in"))
      (node (ref "D85") (pin "GND") (pinfunction "GND_GND") (pintype "power_in"))
      (node (ref "D86") (pin "GND") (pinfunction "GND_GND") (pintype "power_in"))
      (node (ref "D87") (pin "GND") (pinfunction "GND_GND") (pintype "power_in"))
      (node (ref "D88") (pin "GND") (pinfunction "GND_GND") (pintype "power_in"))
      (node (ref "D89") (pin "GND") (pinfunction "GND_GND") (pintype "power_in"))
      (node (ref "D9") (pin "GND") (pinfunction "GND_GND") (pintype "power_in"))
      (node (ref "D90") (pin "GND") (pinfunction "GND_GND") (pintype "power_in"))
      (node (ref "D91") (pin "GND") (pinfunction "GND_GND") (pintype "power_in"))
      (node (ref "D92") (pin "GND") (pinfunction "GND_GND") (pintype "power_in"))
      (node (ref "D93") (pin "GND") (pinfunction "GND_GND") (pintype "power_in"))
      (node (ref "D94") (pin "GND") (pinfunction "GND_GND") (pintype "power_in"))
      (node (ref "D95") (pin "GND") (pinfunction "GND_GND") (pintype "power_in"))
      (node (ref "D96") (pin "GND") (pinfunction "GND_GND") (pintype "power_in"))
      (node (ref "D97") (pin "GND") (pinfunction "GND_GND") (pintype "power_in"))
      (node (ref "D98") (pin "GND") (pinfunction "GND_GND") (pintype "power_in"))
      (node (ref "D99") (pin "GND") (pinfunction "GND_GND") (pintype "power_in"))
      (node (ref "JP1") (pin "5") (pinfunction "5_5") (pintype "passive"))
      (node (ref "JP1") (pin "6") (pinfunction "6_6") (pintype "passive"))
      (node (ref "JP1") (pin "7") (pinfunction "7_7") (pintype "passive"))
      (node (ref "JP2") (pin "5") (pinfunction "5_5") (pintype "passive"))
      (node (ref "JP2") (pin "6") (pinfunction "6_6") (pintype "passive"))
      (node (ref "JP2") (pin "7") (pinfunction "7_7") (pintype "passive"))
      (node (ref "Z1") (pin "2") (pinfunction "2_2") (pintype "passive"))
    )
    (net (code "155") (name "Net-(D76-PadDI)") (class "Default")
      (node (ref "D76") (pin "DI") (pinfunction "DI_DI") (pintype "input"))
      (node (ref "D77") (pin "DO") (pinfunction "DO_DO") (pintype "output"))
    )
    (net (code "156") (name "Net-(D77-PadDI)") (class "Default")
      (node (ref "D77") (pin "DI") (pinfunction "DI_DI") (pintype "input"))
      (node (ref "D78") (pin "DO") (pinfunction "DO_DO") (pintype "output"))
    )
    (net (code "157") (name "Net-(D78-PadDI)") (class "Default")
      (node (ref "D78") (pin "DI") (pinfunction "DI_DI") (pintype "input"))
      (node (ref "D79") (pin "DO") (pinfunction "DO_DO") (pintype "output"))
    )
    (net (code "158") (name "Net-(D79-PadDI)") (class "Default")
      (node (ref "D79") (pin "DI") (pinfunction "DI_DI") (pintype "input"))
      (node (ref "D80") (pin "DO") (pinfunction "DO_DO") (pintype "output"))
    )
    (net (code "159") (name "Net-(D80-PadDI)") (class "Default")
      (node (ref "D80") (pin "DI") (pinfunction "DI_DI") (pintype "input"))
      (node (ref "D81") (pin "DO") (pinfunction "DO_DO") (pintype "output"))
    )
    (net (code "160") (name "Net-(D81-PadDI)") (class "Default")
      (node (ref "D81") (pin "DI") (pinfunction "DI_DI") (pintype "input"))
      (node (ref "D82") (pin "DO") (pinfunction "DO_DO") (pintype "output"))
    )
    (net (code "161") (name "Net-(D82-PadDI)") (class "Default")
      (node (ref "D82") (pin "DI") (pinfunction "DI_DI") (pintype "input"))
      (node (ref "D83") (pin "DO") (pinfunction "DO_DO") (pintype "output"))
    )
    (net (code "162") (name "Net-(D83-PadDI)") (class "Default")
      (node (ref "D83") (pin "DI") (pinfunction "DI_DI") (pintype "input"))
      (node (ref "D84") (pin "DO") (pinfunction "DO_DO") (pintype "output"))
    )
    (net (code "163") (name "Net-(D84-PadDI)") (class "Default")
      (node (ref "D84") (pin "DI") (pinfunction "DI_DI") (pintype "input"))
      (node (ref "D85") (pin "DO") (pinfunction "DO_DO") (pintype "output"))
    )
    (net (code "164") (name "Net-(D85-PadDI)") (class "Default")
      (node (ref "D85") (pin "DI") (pinfunction "DI_DI") (pintype "input"))
      (node (ref "D86") (pin "DO") (pinfunction "DO_DO") (pintype "output"))
    )
    (net (code "165") (name "Net-(D86-PadDI)") (class "Default")
      (node (ref "D86") (pin "DI") (pinfunction "DI_DI") (pintype "input"))
      (node (ref "D87") (pin "DO") (pinfunction "DO_DO") (pintype "output"))
    )
    (net (code "166") (name "Net-(D87-PadDI)") (class "Default")
      (node (ref "D87") (pin "DI") (pinfunction "DI_DI") (pintype "input"))
      (node (ref "D88") (pin "DO") (pinfunction "DO_DO") (pintype "output"))
    )
    (net (code "167") (name "Net-(D88-PadDI)") (class "Default")
      (node (ref "D88") (pin "DI") (pinfunction "DI_DI") (pintype "input"))
      (node (ref "D89") (pin "DO") (pinfunction "DO_DO") (pintype "output"))
    )
    (net (code "168") (name "Net-(D89-PadDI)") (class "Default")
      (node (ref "D89") (pin "DI") (pinfunction "DI_DI") (pintype "input"))
      (node (ref "D90") (pin "DO") (pinfunction "DO_DO") (pintype "output"))
    )
    (net (code "169") (name "Net-(D91-PadDI)") (class "Default")
      (node (ref "D91") (pin "DI") (pinfunction "DI_DI") (pintype "input"))
      (node (ref "D92") (pin "DO") (pinfunction "DO_DO") (pintype "output"))
    )
    (net (code "170") (name "Net-(D92-PadDI)") (class "Default")
      (node (ref "D92") (pin "DI") (pinfunction "DI_DI") (pintype "input"))
      (node (ref "D93") (pin "DO") (pinfunction "DO_DO") (pintype "output"))
    )
    (net (code "171") (name "Net-(D93-PadDI)") (class "Default")
      (node (ref "D93") (pin "DI") (pinfunction "DI_DI") (pintype "input"))
      (node (ref "D94") (pin "DO") (pinfunction "DO_DO") (pintype "output"))
    )
    (net (code "172") (name "Net-(D94-PadDI)") (class "Default")
      (node (ref "D94") (pin "DI") (pinfunction "DI_DI") (pintype "input"))
      (node (ref "D95") (pin "DO") (pinfunction "DO_DO") (pintype "output"))
    )
    (net (code "173") (name "Net-(D95-PadDI)") (class "Default")
      (node (ref "D95") (pin "DI") (pinfunction "DI_DI") (pintype "input"))
      (node (ref "D96") (pin "DO") (pinfunction "DO_DO") (pintype "output"))
    )
    (net (code "174") (name "Net-(D96-PadDI)") (class "Default")
      (node (ref "D96") (pin "DI") (pinfunction "DI_DI") (pintype "input"))
      (node (ref "D97") (pin "DO") (pinfunction "DO_DO") (pintype "output"))
    )
    (net (code "175") (name "Net-(D97-PadDI)") (class "Default")
      (node (ref "D97") (pin "DI") (pinfunction "DI_DI") (pintype "input"))
      (node (ref "D98") (pin "DO") (pinfunction "DO_DO") (pintype "output"))
    )
    (net (code "176") (name "Net-(D98-PadDI)") (class "Default")
      (node (ref "D98") (pin "DI") (pinfunction "DI_DI") (pintype "input"))
      (node (ref "D99") (pin "DO") (pinfunction "DO_DO") (pintype "output"))
    )
    (net (code "177") (name "Net-(D100-PadDI)") (class "Default")
      (node (ref "D100") (pin "DI") (pinfunction "DI_DI") (pintype "input"))
      (node (ref "D101") (pin "DO") (pinfunction "DO_DO") (pintype "output"))
    )
    (net (code "178") (name "Net-(D100-PadDO)") (class "Default")
      (node (ref "D100") (pin "DO") (pinfunction "DO_DO") (pintype "output"))
      (node (ref "D99") (pin "DI") (pinfunction "DI_DI") (pintype "input"))
    )
    (net (code "179") (name "Net-(D101-PadDI)") (class "Default")
      (node (ref "D101") (pin "DI") (pinfunction "DI_DI") (pintype "input"))
      (node (ref "D102") (pin "DO") (pinfunction "DO_DO") (pintype "output"))
    )
    (net (code "180") (name "Net-(D102-PadDI)") (class "Default")
      (node (ref "D102") (pin "DI") (pinfunction "DI_DI") (pintype "input"))
      (node (ref "D103") (pin "DO") (pinfunction "DO_DO") (pintype "output"))
    )
    (net (code "181") (name "Net-(D103-PadDI)") (class "Default")
      (node (ref "D103") (pin "DI") (pinfunction "DI_DI") (pintype "input"))
      (node (ref "D104") (pin "DO") (pinfunction "DO_DO") (pintype "output"))
    )
    (net (code "182") (name "Net-(D104-PadDI)") (class "Default")
      (node (ref "D104") (pin "DI") (pinfunction "DI_DI") (pintype "input"))
      (node (ref "D105") (pin "DO") (pinfunction "DO_DO") (pintype "output"))
    )
    (net (code "183") (name "Net-(D106-PadDI)") (class "Default")
      (node (ref "D106") (pin "DI") (pinfunction "DI_DI") (pintype "input"))
      (node (ref "D107") (pin "DO") (pinfunction "DO_DO") (pintype "output"))
    )
    (net (code "184") (name "Net-(D107-PadDI)") (class "Default")
      (node (ref "D107") (pin "DI") (pinfunction "DI_DI") (pintype "input"))
      (node (ref "D108") (pin "DO") (pinfunction "DO_DO") (pintype "output"))
    )
    (net (code "185") (name "Net-(D108-PadDI)") (class "Default")
      (node (ref "D108") (pin "DI") (pinfunction "DI_DI") (pintype "input"))
      (node (ref "D109") (pin "DO") (pinfunction "DO_DO") (pintype "output"))
    )
    (net (code "186") (name "Net-(D109-PadDI)") (class "Default")
      (node (ref "D109") (pin "DI") (pinfunction "DI_DI") (pintype "input"))
      (node (ref "D110") (pin "DO") (pinfunction "DO_DO") (pintype "output"))
    )
    (net (code "187") (name "Net-(D110-PadDI)") (class "Default")
      (node (ref "D110") (pin "DI") (pinfunction "DI_DI") (pintype "input"))
      (node (ref "D111") (pin "DO") (pinfunction "DO_DO") (pintype "output"))
    )
    (net (code "188") (name "Net-(D111-PadDI)") (class "Default")
      (node (ref "D111") (pin "DI") (pinfunction "DI_DI") (pintype "input"))
      (node (ref "D112") (pin "DO") (pinfunction "DO_DO") (pintype "output"))
    )
    (net (code "189") (name "Net-(D112-PadDI)") (class "Default")
      (node (ref "D112") (pin "DI") (pinfunction "DI_DI") (pintype "input"))
      (node (ref "D113") (pin "DO") (pinfunction "DO_DO") (pintype "output"))
    )
    (net (code "190") (name "Net-(D113-PadDI)") (class "Default")
      (node (ref "D113") (pin "DI") (pinfunction "DI_DI") (pintype "input"))
      (node (ref "D114") (pin "DO") (pinfunction "DO_DO") (pintype "output"))
    )
    (net (code "191") (name "Net-(D114-PadDI)") (class "Default")
      (node (ref "D114") (pin "DI") (pinfunction "DI_DI") (pintype "input"))
      (node (ref "D115") (pin "DO") (pinfunction "DO_DO") (pintype "output"))
    )
    (net (code "192") (name "Net-(D115-PadDI)") (class "Default")
      (node (ref "D115") (pin "DI") (pinfunction "DI_DI") (pintype "input"))
      (node (ref "D116") (pin "DO") (pinfunction "DO_DO") (pintype "output"))
    )
    (net (code "193") (name "Net-(D116-PadDI)") (class "Default")
      (node (ref "D116") (pin "DI") (pinfunction "DI_DI") (pintype "input"))
      (node (ref "D117") (pin "DO") (pinfunction "DO_DO") (pintype "output"))
    )
    (net (code "194") (name "Net-(D117-PadDI)") (class "Default")
      (node (ref "D117") (pin "DI") (pinfunction "DI_DI") (pintype "input"))
      (node (ref "D118") (pin "DO") (pinfunction "DO_DO") (pintype "output"))
    )
    (net (code "195") (name "Net-(D118-PadDI)") (class "Default")
      (node (ref "D118") (pin "DI") (pinfunction "DI_DI") (pintype "input"))
      (node (ref "D119") (pin "DO") (pinfunction "DO_DO") (pintype "output"))
    )
    (net (code "196") (name "Net-(D119-PadDI)") (class "Default")
      (node (ref "D119") (pin "DI") (pinfunction "DI_DI") (pintype "input"))
      (node (ref "D120") (pin "DO") (pinfunction "DO_DO") (pintype "output"))
    )
    (net (code "197") (name "Net-(D121-PadDI)") (class "Default")
      (node (ref "D121") (pin "DI") (pinfunction "DI_DI") (pintype "input"))
      (node (ref "D122") (pin "DO") (pinfunction "DO_DO") (pintype "output"))
    )
    (net (code "198") (name "Net-(D122-PadDI)") (class "Default")
      (node (ref "D122") (pin "DI") (pinfunction "DI_DI") (pintype "input"))
      (node (ref "D123") (pin "DO") (pinfunction "DO_DO") (pintype "output"))
    )
    (net (code "199") (name "Net-(D123-PadDI)") (class "Default")
      (node (ref "D123") (pin "DI") (pinfunction "DI_DI") (pintype "input"))
      (node (ref "D124") (pin "DO") (pinfunction "DO_DO") (pintype "output"))
    )
    (net (code "200") (name "Net-(D124-PadDI)") (class "Default")
      (node (ref "D124") (pin "DI") (pinfunction "DI_DI") (pintype "input"))
      (node (ref "D125") (pin "DO") (pinfunction "DO_DO") (pintype "output"))
    )
    (net (code "201") (name "Net-(D125-PadDI)") (class "Default")
      (node (ref "D125") (pin "DI") (pinfunction "DI_DI") (pintype "input"))
      (node (ref "D126") (pin "DO") (pinfunction "DO_DO") (pintype "output"))
    )
    (net (code "202") (name "Net-(D126-PadDI)") (class "Default")
      (node (ref "D126") (pin "DI") (pinfunction "DI_DI") (pintype "input"))
      (node (ref "D127") (pin "DO") (pinfunction "DO_DO") (pintype "output"))
    )
    (net (code "203") (name "Net-(D127-PadDI)") (class "Default")
      (node (ref "D127") (pin "DI") (pinfunction "DI_DI") (pintype "input"))
      (node (ref "D128") (pin "DO") (pinfunction "DO_DO") (pintype "output"))
    )
    (net (code "204") (name "Net-(D128-PadDI)") (class "Default")
      (node (ref "D128") (pin "DI") (pinfunction "DI_DI") (pintype "input"))
      (node (ref "D129") (pin "DO") (pinfunction "DO_DO") (pintype "output"))
    )
    (net (code "205") (name "Net-(D129-PadDI)") (class "Default")
      (node (ref "D129") (pin "DI") (pinfunction "DI_DI") (pintype "input"))
      (node (ref "D130") (pin "DO") (pinfunction "DO_DO") (pintype "output"))
    )
    (net (code "206") (name "Net-(D130-PadDI)") (class "Default")
      (node (ref "D130") (pin "DI") (pinfunction "DI_DI") (pintype "input"))
      (node (ref "D131") (pin "DO") (pinfunction "DO_DO") (pintype "output"))
    )
    (net (code "207") (name "Net-(D131-PadDI)") (class "Default")
      (node (ref "D131") (pin "DI") (pinfunction "DI_DI") (pintype "input"))
      (node (ref "D132") (pin "DO") (pinfunction "DO_DO") (pintype "output"))
    )
    (net (code "208") (name "Net-(D132-PadDI)") (class "Default")
      (node (ref "D132") (pin "DI") (pinfunction "DI_DI") (pintype "input"))
      (node (ref "D133") (pin "DO") (pinfunction "DO_DO") (pintype "output"))
    )
    (net (code "209") (name "Net-(D133-PadDI)") (class "Default")
      (node (ref "D133") (pin "DI") (pinfunction "DI_DI") (pintype "input"))
      (node (ref "D134") (pin "DO") (pinfunction "DO_DO") (pintype "output"))
    )
    (net (code "210") (name "Net-(D134-PadDI)") (class "Default")
      (node (ref "D134") (pin "DI") (pinfunction "DI_DI") (pintype "input"))
      (node (ref "D135") (pin "DO") (pinfunction "DO_DO") (pintype "output"))
    )
    (net (code "211") (name "Net-(D136-PadDI)") (class "Default")
      (node (ref "D136") (pin "DI") (pinfunction "DI_DI") (pintype "input"))
      (node (ref "D137") (pin "DO") (pinfunction "DO_DO") (pintype "output"))
    )
    (net (code "212") (name "Net-(D137-PadDI)") (class "Default")
      (node (ref "D137") (pin "DI") (pinfunction "DI_DI") (pintype "input"))
      (node (ref "D138") (pin "DO") (pinfunction "DO_DO") (pintype "output"))
    )
    (net (code "213") (name "Net-(D138-PadDI)") (class "Default")
      (node (ref "D138") (pin "DI") (pinfunction "DI_DI") (pintype "input"))
      (node (ref "D139") (pin "DO") (pinfunction "DO_DO") (pintype "output"))
    )
    (net (code "214") (name "Net-(D139-PadDI)") (class "Default")
      (node (ref "D139") (pin "DI") (pinfunction "DI_DI") (pintype "input"))
      (node (ref "D140") (pin "DO") (pinfunction "DO_DO") (pintype "output"))
    )
    (net (code "215") (name "Net-(D140-PadDI)") (class "Default")
      (node (ref "D140") (pin "DI") (pinfunction "DI_DI") (pintype "input"))
      (node (ref "D141") (pin "DO") (pinfunction "DO_DO") (pintype "output"))
    )
    (net (code "216") (name "Net-(D141-PadDI)") (class "Default")
      (node (ref "D141") (pin "DI") (pinfunction "DI_DI") (pintype "input"))
      (node (ref "D142") (pin "DO") (pinfunction "DO_DO") (pintype "output"))
    )
    (net (code "217") (name "Net-(D142-PadDI)") (class "Default")
      (node (ref "D142") (pin "DI") (pinfunction "DI_DI") (pintype "input"))
      (node (ref "D143") (pin "DO") (pinfunction "DO_DO") (pintype "output"))
    )
    (net (code "218") (name "Net-(D143-PadDI)") (class "Default")
      (node (ref "D143") (pin "DI") (pinfunction "DI_DI") (pintype "input"))
      (node (ref "D144") (pin "DO") (pinfunction "DO_DO") (pintype "output"))
    )
    (net (code "219") (name "Net-(D144-PadDI)") (class "Default")
      (node (ref "D144") (pin "DI") (pinfunction "DI_DI") (pintype "input"))
      (node (ref "D145") (pin "DO") (pinfunction "DO_DO") (pintype "output"))
    )
    (net (code "220") (name "Net-(D145-PadDI)") (class "Default")
      (node (ref "D145") (pin "DI") (pinfunction "DI_DI") (pintype "input"))
      (node (ref "D146") (pin "DO") (pinfunction "DO_DO") (pintype "output"))
    )
    (net (code "221") (name "Net-(D146-PadDI)") (class "Default")
      (node (ref "D146") (pin "DI") (pinfunction "DI_DI") (pintype "input"))
      (node (ref "D147") (pin "DO") (pinfunction "DO_DO") (pintype "output"))
    )
    (net (code "222") (name "Net-(D147-PadDI)") (class "Default")
      (node (ref "D147") (pin "DI") (pinfunction "DI_DI") (pintype "input"))
      (node (ref "D148") (pin "DO") (pinfunction "DO_DO") (pintype "output"))
    )
    (net (code "223") (name "Net-(D148-PadDI)") (class "Default")
      (node (ref "D148") (pin "DI") (pinfunction "DI_DI") (pintype "input"))
      (node (ref "D149") (pin "DO") (pinfunction "DO_DO") (pintype "output"))
    )
    (net (code "224") (name "Net-(D149-PadDI)") (class "Default")
      (node (ref "D149") (pin "DI") (pinfunction "DI_DI") (pintype "input"))
      (node (ref "D150") (pin "DO") (pinfunction "DO_DO") (pintype "output"))
    )
    (net (code "225") (name "Net-(D151-PadDI)") (class "Default")
      (node (ref "D151") (pin "DI") (pinfunction "DI_DI") (pintype "input"))
      (node (ref "D152") (pin "DO") (pinfunction "DO_DO") (pintype "output"))
    )
    (net (code "226") (name "Net-(D152-PadDI)") (class "Default")
      (node (ref "D152") (pin "DI") (pinfunction "DI_DI") (pintype "input"))
      (node (ref "D153") (pin "DO") (pinfunction "DO_DO") (pintype "output"))
    )
    (net (code "227") (name "Net-(D153-PadDI)") (class "Default")
      (node (ref "D153") (pin "DI") (pinfunction "DI_DI") (pintype "input"))
      (node (ref "D154") (pin "DO") (pinfunction "DO_DO") (pintype "output"))
    )
    (net (code "228") (name "Net-(D154-PadDI)") (class "Default")
      (node (ref "D154") (pin "DI") (pinfunction "DI_DI") (pintype "input"))
      (node (ref "D155") (pin "DO") (pinfunction "DO_DO") (pintype "output"))
    )
    (net (code "229") (name "Net-(D155-PadDI)") (class "Default")
      (node (ref "D155") (pin "DI") (pinfunction "DI_DI") (pintype "input"))
      (node (ref "D156") (pin "DO") (pinfunction "DO_DO") (pintype "output"))
    )
    (net (code "230") (name "Net-(D156-PadDI)") (class "Default")
      (node (ref "D156") (pin "DI") (pinfunction "DI_DI") (pintype "input"))
      (node (ref "D157") (pin "DO") (pinfunction "DO_DO") (pintype "output"))
    )
    (net (code "231") (name "Net-(D157-PadDI)") (class "Default")
      (node (ref "D157") (pin "DI") (pinfunction "DI_DI") (pintype "input"))
      (node (ref "D158") (pin "DO") (pinfunction "DO_DO") (pintype "output"))
    )
    (net (code "232") (name "Net-(D158-PadDI)") (class "Default")
      (node (ref "D158") (pin "DI") (pinfunction "DI_DI") (pintype "input"))
      (node (ref "D159") (pin "DO") (pinfunction "DO_DO") (pintype "output"))
    )
    (net (code "233") (name "Net-(D159-PadDI)") (class "Default")
      (node (ref "D159") (pin "DI") (pinfunction "DI_DI") (pintype "input"))
      (node (ref "D160") (pin "DO") (pinfunction "DO_DO") (pintype "output"))
    )
    (net (code "234") (name "Net-(D160-PadDI)") (class "Default")
      (node (ref "D160") (pin "DI") (pinfunction "DI_DI") (pintype "input"))
      (node (ref "D161") (pin "DO") (pinfunction "DO_DO") (pintype "output"))
    )
    (net (code "235") (name "Net-(D161-PadDI)") (class "Default")
      (node (ref "D161") (pin "DI") (pinfunction "DI_DI") (pintype "input"))
      (node (ref "D162") (pin "DO") (pinfunction "DO_DO") (pintype "output"))
    )
    (net (code "236") (name "Net-(D162-PadDI)") (class "Default")
      (node (ref "D162") (pin "DI") (pinfunction "DI_DI") (pintype "input"))
      (node (ref "D163") (pin "DO") (pinfunction "DO_DO") (pintype "output"))
    )
    (net (code "237") (name "Net-(D163-PadDI)") (class "Default")
      (node (ref "D163") (pin "DI") (pinfunction "DI_DI") (pintype "input"))
      (node (ref "D164") (pin "DO") (pinfunction "DO_DO") (pintype "output"))
    )
    (net (code "238") (name "Net-(D164-PadDI)") (class "Default")
      (node (ref "D164") (pin "DI") (pinfunction "DI_DI") (pintype "input"))
      (node (ref "D165") (pin "DO") (pinfunction "DO_DO") (pintype "output"))
    )
    (net (code "239") (name "Net-(D166-PadDI)") (class "Default")
      (node (ref "D166") (pin "DI") (pinfunction "DI_DI") (pintype "input"))
      (node (ref "D167") (pin "DO") (pinfunction "DO_DO") (pintype "output"))
    )
    (net (code "240") (name "Net-(D167-PadDI)") (class "Default")
      (node (ref "D167") (pin "DI") (pinfunction "DI_DI") (pintype "input"))
      (node (ref "D168") (pin "DO") (pinfunction "DO_DO") (pintype "output"))
    )
    (net (code "241") (name "Net-(D168-PadDI)") (class "Default")
      (node (ref "D168") (pin "DI") (pinfunction "DI_DI") (pintype "input"))
      (node (ref "D169") (pin "DO") (pinfunction "DO_DO") (pintype "output"))
    )
    (net (code "242") (name "Net-(D169-PadDI)") (class "Default")
      (node (ref "D169") (pin "DI") (pinfunction "DI_DI") (pintype "input"))
      (node (ref "D170") (pin "DO") (pinfunction "DO_DO") (pintype "output"))
    )
    (net (code "243") (name "Net-(D170-PadDI)") (class "Default")
      (node (ref "D170") (pin "DI") (pinfunction "DI_DI") (pintype "input"))
      (node (ref "D171") (pin "DO") (pinfunction "DO_DO") (pintype "output"))
    )
    (net (code "244") (name "Net-(D171-PadDI)") (class "Default")
      (node (ref "D171") (pin "DI") (pinfunction "DI_DI") (pintype "input"))
      (node (ref "D172") (pin "DO") (pinfunction "DO_DO") (pintype "output"))
    )
    (net (code "245") (name "Net-(D172-PadDI)") (class "Default")
      (node (ref "D172") (pin "DI") (pinfunction "DI_DI") (pintype "input"))
      (node (ref "D173") (pin "DO") (pinfunction "DO_DO") (pintype "output"))
    )
    (net (code "246") (name "Net-(D173-PadDI)") (class "Default")
      (node (ref "D173") (pin "DI") (pinfunction "DI_DI") (pintype "input"))
      (node (ref "D174") (pin "DO") (pinfunction "DO_DO") (pintype "output"))
    )
    (net (code "247") (name "Net-(D174-PadDI)") (class "Default")
      (node (ref "D174") (pin "DI") (pinfunction "DI_DI") (pintype "input"))
      (node (ref "D175") (pin "DO") (pinfunction "DO_DO") (pintype "output"))
    )
    (net (code "248") (name "Net-(D175-PadDI)") (class "Default")
      (node (ref "D175") (pin "DI") (pinfunction "DI_DI") (pintype "input"))
      (node (ref "D176") (pin "DO") (pinfunction "DO_DO") (pintype "output"))
    )
    (net (code "249") (name "Net-(D176-PadDI)") (class "Default")
      (node (ref "D176") (pin "DI") (pinfunction "DI_DI") (pintype "input"))
      (node (ref "D177") (pin "DO") (pinfunction "DO_DO") (pintype "output"))
    )
    (net (code "250") (name "Net-(D177-PadDI)") (class "Default")
      (node (ref "D177") (pin "DI") (pinfunction "DI_DI") (pintype "input"))
      (node (ref "D178") (pin "DO") (pinfunction "DO_DO") (pintype "output"))
    )
    (net (code "251") (name "Net-(D178-PadDI)") (class "Default")
      (node (ref "D178") (pin "DI") (pinfunction "DI_DI") (pintype "input"))
      (node (ref "D179") (pin "DO") (pinfunction "DO_DO") (pintype "output"))
    )
    (net (code "252") (name "Net-(D179-PadDI)") (class "Default")
      (node (ref "D179") (pin "DI") (pinfunction "DI_DI") (pintype "input"))
      (node (ref "D180") (pin "DO") (pinfunction "DO_DO") (pintype "output"))
    )
    (net (code "253") (name "Net-(D181-PadDI)") (class "Default")
      (node (ref "D181") (pin "DI") (pinfunction "DI_DI") (pintype "input"))
      (node (ref "D182") (pin "DO") (pinfunction "DO_DO") (pintype "output"))
    )
    (net (code "254") (name "Net-(D182-PadDI)") (class "Default")
      (node (ref "D182") (pin "DI") (pinfunction "DI_DI") (pintype "input"))
      (node (ref "D183") (pin "DO") (pinfunction "DO_DO") (pintype "output"))
    )
    (net (code "255") (name "Net-(D183-PadDI)") (class "Default")
      (node (ref "D183") (pin "DI") (pinfunction "DI_DI") (pintype "input"))
      (node (ref "D184") (pin "DO") (pinfunction "DO_DO") (pintype "output"))
    )
    (net (code "256") (name "Net-(D184-PadDI)") (class "Default")
      (node (ref "D184") (pin "DI") (pinfunction "DI_DI") (pintype "input"))
      (node (ref "D185") (pin "DO") (pinfunction "DO_DO") (pintype "output"))
    )
    (net (code "257") (name "Net-(D185-PadDI)") (class "Default")
      (node (ref "D185") (pin "DI") (pinfunction "DI_DI") (pintype "input"))
      (node (ref "D186") (pin "DO") (pinfunction "DO_DO") (pintype "output"))
    )
    (net (code "258") (name "Net-(D186-PadDI)") (class "Default")
      (node (ref "D186") (pin "DI") (pinfunction "DI_DI") (pintype "input"))
      (node (ref "D187") (pin "DO") (pinfunction "DO_DO") (pintype "output"))
    )
    (net (code "259") (name "Net-(D187-PadDI)") (class "Default")
      (node (ref "D187") (pin "DI") (pinfunction "DI_DI") (pintype "input"))
      (node (ref "D188") (pin "DO") (pinfunction "DO_DO") (pintype "output"))
    )
    (net (code "260") (name "Net-(D188-PadDI)") (class "Default")
      (node (ref "D188") (pin "DI") (pinfunction "DI_DI") (pintype "input"))
      (node (ref "D189") (pin "DO") (pinfunction "DO_DO") (pintype "output"))
    )
    (net (code "261") (name "Net-(D189-PadDI)") (class "Default")
      (node (ref "D189") (pin "DI") (pinfunction "DI_DI") (pintype "input"))
      (node (ref "D190") (pin "DO") (pinfunction "DO_DO") (pintype "output"))
    )
    (net (code "262") (name "Net-(D190-PadDI)") (class "Default")
      (node (ref "D190") (pin "DI") (pinfunction "DI_DI") (pintype "input"))
      (node (ref "D191") (pin "DO") (pinfunction "DO_DO") (pintype "output"))
    )
    (net (code "263") (name "Net-(D191-PadDI)") (class "Default")
      (node (ref "D191") (pin "DI") (pinfunction "DI_DI") (pintype "input"))
      (node (ref "D192") (pin "DO") (pinfunction "DO_DO") (pintype "output"))
    )
    (net (code "264") (name "Net-(D192-PadDI)") (class "Default")
      (node (ref "D192") (pin "DI") (pinfunction "DI_DI") (pintype "input"))
      (node (ref "D193") (pin "DO") (pinfunction "DO_DO") (pintype "output"))
    )
    (net (code "265") (name "Net-(D193-PadDI)") (class "Default")
      (node (ref "D193") (pin "DI") (pinfunction "DI_DI") (pintype "input"))
      (node (ref "D194") (pin "DO") (pinfunction "DO_DO") (pintype "output"))
    )
    (net (code "266") (name "Net-(D194-PadDI)") (class "Default")
      (node (ref "D194") (pin "DI") (pinfunction "DI_DI") (pintype "input"))
      (node (ref "D195") (pin "DO") (pinfunction "DO_DO") (pintype "output"))
    )
    (net (code "267") (name "Net-(D196-PadDI)") (class "Default")
      (node (ref "D196") (pin "DI") (pinfunction "DI_DI") (pintype "input"))
      (node (ref "D197") (pin "DO") (pinfunction "DO_DO") (pintype "output"))
    )
    (net (code "268") (name "Net-(D197-PadDI)") (class "Default")
      (node (ref "D197") (pin "DI") (pinfunction "DI_DI") (pintype "input"))
      (node (ref "D198") (pin "DO") (pinfunction "DO_DO") (pintype "output"))
    )
    (net (code "269") (name "Net-(D198-PadDI)") (class "Default")
      (node (ref "D198") (pin "DI") (pinfunction "DI_DI") (pintype "input"))
      (node (ref "D199") (pin "DO") (pinfunction "DO_DO") (pintype "output"))
    )
    (net (code "270") (name "Net-(D199-PadDI)") (class "Default")
      (node (ref "D199") (pin "DI") (pinfunction "DI_DI") (pintype "input"))
      (node (ref "D200") (pin "DO") (pinfunction "DO_DO") (pintype "output"))
    )
    (net (code "271") (name "Net-(D200-PadDI)") (class "Default")
      (node (ref "D200") (pin "DI") (pinfunction "DI_DI") (pintype "input"))
      (node (ref "D201") (pin "DO") (pinfunction "DO_DO") (pintype "output"))
    )
    (net (code "272") (name "Net-(D201-PadDI)") (class "Default")
      (node (ref "D201") (pin "DI") (pinfunction "DI_DI") (pintype "input"))
      (node (ref "D202") (pin "DO") (pinfunction "DO_DO") (pintype "output"))
    )
    (net (code "273") (name "Net-(D202-PadDI)") (class "Default")
      (node (ref "D202") (pin "DI") (pinfunction "DI_DI") (pintype "input"))
      (node (ref "D203") (pin "DO") (pinfunction "DO_DO") (pintype "output"))
    )
    (net (code "274") (name "Net-(D203-PadDI)") (class "Default")
      (node (ref "D203") (pin "DI") (pinfunction "DI_DI") (pintype "input"))
      (node (ref "D204") (pin "DO") (pinfunction "DO_DO") (pintype "output"))
    )
    (net (code "275") (name "Net-(D204-PadDI)") (class "Default")
      (node (ref "D204") (pin "DI") (pinfunction "DI_DI") (pintype "input"))
      (node (ref "D205") (pin "DO") (pinfunction "DO_DO") (pintype "output"))
    )
    (net (code "276") (name "Net-(D205-PadDI)") (class "Default")
      (node (ref "D205") (pin "DI") (pinfunction "DI_DI") (pintype "input"))
      (node (ref "D206") (pin "DO") (pinfunction "DO_DO") (pintype "output"))
    )
    (net (code "277") (name "Net-(D206-PadDI)") (class "Default")
      (node (ref "D206") (pin "DI") (pinfunction "DI_DI") (pintype "input"))
      (node (ref "D207") (pin "DO") (pinfunction "DO_DO") (pintype "output"))
    )
    (net (code "278") (name "Net-(D207-PadDI)") (class "Default")
      (node (ref "D207") (pin "DI") (pinfunction "DI_DI") (pintype "input"))
      (node (ref "D208") (pin "DO") (pinfunction "DO_DO") (pintype "output"))
    )
    (net (code "279") (name "Net-(D208-PadDI)") (class "Default")
      (node (ref "D208") (pin "DI") (pinfunction "DI_DI") (pintype "input"))
      (node (ref "D209") (pin "DO") (pinfunction "DO_DO") (pintype "output"))
    )
    (net (code "280") (name "Net-(D209-PadDI)") (class "Default")
      (node (ref "D209") (pin "DI") (pinfunction "DI_DI") (pintype "input"))
      (node (ref "D210") (pin "DO") (pinfunction "DO_DO") (pintype "output"))
    )
    (net (code "281") (name "Net-(D211-PadDI)") (class "Default")
      (node (ref "D211") (pin "DI") (pinfunction "DI_DI") (pintype "input"))
      (node (ref "D212") (pin "DO") (pinfunction "DO_DO") (pintype "output"))
    )
    (net (code "282") (name "Net-(D212-PadDI)") (class "Default")
      (node (ref "D212") (pin "DI") (pinfunction "DI_DI") (pintype "input"))
      (node (ref "D213") (pin "DO") (pinfunction "DO_DO") (pintype "output"))
    )
    (net (code "283") (name "Net-(D213-PadDI)") (class "Default")
      (node (ref "D213") (pin "DI") (pinfunction "DI_DI") (pintype "input"))
      (node (ref "D214") (pin "DO") (pinfunction "DO_DO") (pintype "output"))
    )
    (net (code "284") (name "Net-(D214-PadDI)") (class "Default")
      (node (ref "D214") (pin "DI") (pinfunction "DI_DI") (pintype "input"))
      (node (ref "D215") (pin "DO") (pinfunction "DO_DO") (pintype "output"))
    )
    (net (code "285") (name "Net-(D215-PadDI)") (class "Default")
      (node (ref "D215") (pin "DI") (pinfunction "DI_DI") (pintype "input"))
      (node (ref "D216") (pin "DO") (pinfunction "DO_DO") (pintype "output"))
    )
    (net (code "286") (name "Net-(D216-PadDI)") (class "Default")
      (node (ref "D216") (pin "DI") (pinfunction "DI_DI") (pintype "input"))
      (node (ref "D217") (pin "DO") (pinfunction "DO_DO") (pintype "output"))
    )
    (net (code "287") (name "Net-(D217-PadDI)") (class "Default")
      (node (ref "D217") (pin "DI") (pinfunction "DI_DI") (pintype "input"))
      (node (ref "D218") (pin "DO") (pinfunction "DO_DO") (pintype "output"))
    )
    (net (code "288") (name "Net-(D218-PadDI)") (class "Default")
      (node (ref "D218") (pin "DI") (pinfunction "DI_DI") (pintype "input"))
      (node (ref "D219") (pin "DO") (pinfunction "DO_DO") (pintype "output"))
    )
    (net (code "289") (name "Net-(D219-PadDI)") (class "Default")
      (node (ref "D219") (pin "DI") (pinfunction "DI_DI") (pintype "input"))
      (node (ref "D220") (pin "DO") (pinfunction "DO_DO") (pintype "output"))
    )
    (net (code "290") (name "Net-(D220-PadDI)") (class "Default")
      (node (ref "D220") (pin "DI") (pinfunction "DI_DI") (pintype "input"))
      (node (ref "D221") (pin "DO") (pinfunction "DO_DO") (pintype "output"))
    )
    (net (code "291") (name "Net-(D221-PadDI)") (class "Default")
      (node (ref "D221") (pin "DI") (pinfunction "DI_DI") (pintype "input"))
      (node (ref "D222") (pin "DO") (pinfunction "DO_DO") (pintype "output"))
    )
    (net (code "292") (name "Net-(D222-PadDI)") (class "Default")
      (node (ref "D222") (pin "DI") (pinfunction "DI_DI") (pintype "input"))
      (node (ref "D223") (pin "DO") (pinfunction "DO_DO") (pintype "output"))
    )
    (net (code "293") (name "Net-(D223-PadDI)") (class "Default")
      (node (ref "D223") (pin "DI") (pinfunction "DI_DI") (pintype "input"))
      (node (ref "D224") (pin "DO") (pinfunction "DO_DO") (pintype "output"))
    )
    (net (code "294") (name "Net-(D224-PadDI)") (class "Default")
      (node (ref "D224") (pin "DI") (pinfunction "DI_DI") (pintype "input"))
      (node (ref "D225") (pin "DO") (pinfunction "DO_DO") (pintype "output"))
    )
    (net (code "295") (name "Net-(D226-PadDI)") (class "Default")
      (node (ref "D226") (pin "DI") (pinfunction "DI_DI") (pintype "input"))
      (node (ref "D227") (pin "DO") (pinfunction "DO_DO") (pintype "output"))
    )
    (net (code "296") (name "Net-(D227-PadDI)") (class "Default")
      (node (ref "D227") (pin "DI") (pinfunction "DI_DI") (pintype "input"))
      (node (ref "D228") (pin "DO") (pinfunction "DO_DO") (pintype "output"))
    )
    (net (code "297") (name "Net-(D228-PadDI)") (class "Default")
      (node (ref "D228") (pin "DI") (pinfunction "DI_DI") (pintype "input"))
      (node (ref "D229") (pin "DO") (pinfunction "DO_DO") (pintype "output"))
    )
    (net (code "298") (name "Net-(D229-PadDI)") (class "Default")
      (node (ref "D229") (pin "DI") (pinfunction "DI_DI") (pintype "input"))
      (node (ref "D230") (pin "DO") (pinfunction "DO_DO") (pintype "output"))
    )
    (net (code "299") (name "Net-(D230-PadDI)") (class "Default")
      (node (ref "D230") (pin "DI") (pinfunction "DI_DI") (pintype "input"))
      (node (ref "D231") (pin "DO") (pinfunction "DO_DO") (pintype "output"))
    )
    (net (code "300") (name "Net-(D231-PadDI)") (class "Default")
      (node (ref "D231") (pin "DI") (pinfunction "DI_DI") (pintype "input"))
      (node (ref "D232") (pin "DO") (pinfunction "DO_DO") (pintype "output"))
    )
    (net (code "301") (name "Net-(D232-PadDI)") (class "Default")
      (node (ref "D232") (pin "DI") (pinfunction "DI_DI") (pintype "input"))
      (node (ref "D233") (pin "DO") (pinfunction "DO_DO") (pintype "output"))
    )
    (net (code "302") (name "Net-(D233-PadDI)") (class "Default")
      (node (ref "D233") (pin "DI") (pinfunction "DI_DI") (pintype "input"))
      (node (ref "D234") (pin "DO") (pinfunction "DO_DO") (pintype "output"))
    )
    (net (code "303") (name "Net-(D234-PadDI)") (class "Default")
      (node (ref "D234") (pin "DI") (pinfunction "DI_DI") (pintype "input"))
      (node (ref "D235") (pin "DO") (pinfunction "DO_DO") (pintype "output"))
    )
    (net (code "304") (name "Net-(D235-PadDI)") (class "Default")
      (node (ref "D235") (pin "DI") (pinfunction "DI_DI") (pintype "input"))
      (node (ref "D236") (pin "DO") (pinfunction "DO_DO") (pintype "output"))
    )
    (net (code "305") (name "Net-(D236-PadDI)") (class "Default")
      (node (ref "D236") (pin "DI") (pinfunction "DI_DI") (pintype "input"))
      (node (ref "D237") (pin "DO") (pinfunction "DO_DO") (pintype "output"))
    )
    (net (code "306") (name "Net-(D237-PadDI)") (class "Default")
      (node (ref "D237") (pin "DI") (pinfunction "DI_DI") (pintype "input"))
      (node (ref "D238") (pin "DO") (pinfunction "DO_DO") (pintype "output"))
    )
    (net (code "307") (name "Net-(D238-PadDI)") (class "Default")
      (node (ref "D238") (pin "DI") (pinfunction "DI_DI") (pintype "input"))
      (node (ref "D239") (pin "DO") (pinfunction "DO_DO") (pintype "output"))
    )
    (net (code "308") (name "Net-(D239-PadDI)") (class "Default")
      (node (ref "D239") (pin "DI") (pinfunction "DI_DI") (pintype "input"))
      (node (ref "D240") (pin "DO") (pinfunction "DO_DO") (pintype "output"))
    )
    (net (code "309") (name "Net-(D241-PadDI)") (class "Default")
      (node (ref "D241") (pin "DI") (pinfunction "DI_DI") (pintype "input"))
      (node (ref "D242") (pin "DO") (pinfunction "DO_DO") (pintype "output"))
    )
    (net (code "310") (name "Net-(D242-PadDI)") (class "Default")
      (node (ref "D242") (pin "DI") (pinfunction "DI_DI") (pintype "input"))
      (node (ref "D243") (pin "DO") (pinfunction "DO_DO") (pintype "output"))
    )
    (net (code "311") (name "Net-(D243-PadDI)") (class "Default")
      (node (ref "D243") (pin "DI") (pinfunction "DI_DI") (pintype "input"))
      (node (ref "D244") (pin "DO") (pinfunction "DO_DO") (pintype "output"))
    )
    (net (code "312") (name "Net-(D244-PadDI)") (class "Default")
      (node (ref "D244") (pin "DI") (pinfunction "DI_DI") (pintype "input"))
      (node (ref "D245") (pin "DO") (pinfunction "DO_DO") (pintype "output"))
    )
    (net (code "313") (name "Net-(D245-PadDI)") (class "Default")
      (node (ref "D245") (pin "DI") (pinfunction "DI_DI") (pintype "input"))
      (node (ref "D246") (pin "DO") (pinfunction "DO_DO") (pintype "output"))
    )
    (net (code "314") (name "Net-(D246-PadDI)") (class "Default")
      (node (ref "D246") (pin "DI") (pinfunction "DI_DI") (pintype "input"))
      (node (ref "D247") (pin "DO") (pinfunction "DO_DO") (pintype "output"))
    )
    (net (code "315") (name "Net-(D247-PadDI)") (class "Default")
      (node (ref "D247") (pin "DI") (pinfunction "DI_DI") (pintype "input"))
      (node (ref "D248") (pin "DO") (pinfunction "DO_DO") (pintype "output"))
    )
    (net (code "316") (name "Net-(D248-PadDI)") (class "Default")
      (node (ref "D248") (pin "DI") (pinfunction "DI_DI") (pintype "input"))
      (node (ref "D249") (pin "DO") (pinfunction "DO_DO") (pintype "output"))
    )
    (net (code "317") (name "Net-(D249-PadDI)") (class "Default")
      (node (ref "D249") (pin "DI") (pinfunction "DI_DI") (pintype "input"))
      (node (ref "D250") (pin "DO") (pinfunction "DO_DO") (pintype "output"))
    )
    (net (code "318") (name "Net-(D250-PadDI)") (class "Default")
      (node (ref "D250") (pin "DI") (pinfunction "DI_DI") (pintype "input"))
      (node (ref "D251") (pin "DO") (pinfunction "DO_DO") (pintype "output"))
    )
    (net (code "319") (name "Net-(D251-PadDI)") (class "Default")
      (node (ref "D251") (pin "DI") (pinfunction "DI_DI") (pintype "input"))
      (node (ref "D252") (pin "DO") (pinfunction "DO_DO") (pintype "output"))
    )
    (net (code "320") (name "Net-(D252-PadDI)") (class "Default")
      (node (ref "D252") (pin "DI") (pinfunction "DI_DI") (pintype "input"))
      (node (ref "D253") (pin "DO") (pinfunction "DO_DO") (pintype "output"))
    )
    (net (code "321") (name "Net-(D253-PadDI)") (class "Default")
      (node (ref "D253") (pin "DI") (pinfunction "DI_DI") (pintype "input"))
      (node (ref "D254") (pin "DO") (pinfunction "DO_DO") (pintype "output"))
    )
    (net (code "322") (name "Net-(D254-PadDI)") (class "Default")
      (node (ref "D254") (pin "DI") (pinfunction "DI_DI") (pintype "input"))
      (node (ref "D255") (pin "DO") (pinfunction "DO_DO") (pintype "output"))
    )
    (net (code "323") (name "Net-(D316-PadDI)") (class "Default")
      (node (ref "D316") (pin "DI") (pinfunction "DI_DI") (pintype "input"))
      (node (ref "D317") (pin "DO") (pinfunction "DO_DO") (pintype "output"))
    )
    (net (code "324") (name "Net-(D317-PadDI)") (class "Default")
      (node (ref "D317") (pin "DI") (pinfunction "DI_DI") (pintype "input"))
      (node (ref "D318") (pin "DO") (pinfunction "DO_DO") (pintype "output"))
    )
    (net (code "325") (name "Net-(D318-PadDI)") (class "Default")
      (node (ref "D318") (pin "DI") (pinfunction "DI_DI") (pintype "input"))
      (node (ref "D319") (pin "DO") (pinfunction "DO_DO") (pintype "output"))
    )
    (net (code "326") (name "Net-(D319-PadDI)") (class "Default")
      (node (ref "D319") (pin "DI") (pinfunction "DI_DI") (pintype "input"))
      (node (ref "D320") (pin "DO") (pinfunction "DO_DO") (pintype "output"))
    )
    (net (code "327") (name "Net-(D320-PadDI)") (class "Default")
      (node (ref "D320") (pin "DI") (pinfunction "DI_DI") (pintype "input"))
      (node (ref "D321") (pin "DO") (pinfunction "DO_DO") (pintype "output"))
    )
    (net (code "328") (name "Net-(D321-PadDI)") (class "Default")
      (node (ref "D321") (pin "DI") (pinfunction "DI_DI") (pintype "input"))
      (node (ref "D322") (pin "DO") (pinfunction "DO_DO") (pintype "output"))
    )
    (net (code "329") (name "Net-(D322-PadDI)") (class "Default")
      (node (ref "D322") (pin "DI") (pinfunction "DI_DI") (pintype "input"))
      (node (ref "D323") (pin "DO") (pinfunction "DO_DO") (pintype "output"))
    )
    (net (code "330") (name "Net-(D323-PadDI)") (class "Default")
      (node (ref "D323") (pin "DI") (pinfunction "DI_DI") (pintype "input"))
      (node (ref "D324") (pin "DO") (pinfunction "DO_DO") (pintype "output"))
    )
    (net (code "331") (name "Net-(D324-PadDI)") (class "Default")
      (node (ref "D324") (pin "DI") (pinfunction "DI_DI") (pintype "input"))
      (node (ref "D325") (pin "DO") (pinfunction "DO_DO") (pintype "output"))
    )
    (net (code "332") (name "Net-(D325-PadDI)") (class "Default")
      (node (ref "D325") (pin "DI") (pinfunction "DI_DI") (pintype "input"))
      (node (ref "D326") (pin "DO") (pinfunction "DO_DO") (pintype "output"))
    )
    (net (code "333") (name "Net-(D326-PadDI)") (class "Default")
      (node (ref "D326") (pin "DI") (pinfunction "DI_DI") (pintype "input"))
      (node (ref "D327") (pin "DO") (pinfunction "DO_DO") (pintype "output"))
    )
    (net (code "334") (name "Net-(D327-PadDI)") (class "Default")
      (node (ref "D327") (pin "DI") (pinfunction "DI_DI") (pintype "input"))
      (node (ref "D328") (pin "DO") (pinfunction "DO_DO") (pintype "output"))
    )
    (net (code "335") (name "Net-(D328-PadDI)") (class "Default")
      (node (ref "D328") (pin "DI") (pinfunction "DI_DI") (pintype "input"))
      (node (ref "D329") (pin "DO") (pinfunction "DO_DO") (pintype "output"))
    )
    (net (code "336") (name "Net-(D329-PadDI)") (class "Default")
      (node (ref "D329") (pin "DI") (pinfunction "DI_DI") (pintype "input"))
      (node (ref "D330") (pin "DO") (pinfunction "DO_DO") (pintype "output"))
    )
    (net (code "337") (name "Net-(D331-PadDI)") (class "Default")
      (node (ref "D331") (pin "DI") (pinfunction "DI_DI") (pintype "input"))
      (node (ref "D332") (pin "DO") (pinfunction "DO_DO") (pintype "output"))
    )
    (net (code "338") (name "Net-(D332-PadDI)") (class "Default")
      (node (ref "D332") (pin "DI") (pinfunction "DI_DI") (pintype "input"))
      (node (ref "D333") (pin "DO") (pinfunction "DO_DO") (pintype "output"))
    )
    (net (code "339") (name "Net-(D333-PadDI)") (class "Default")
      (node (ref "D333") (pin "DI") (pinfunction "DI_DI") (pintype "input"))
      (node (ref "D334") (pin "DO") (pinfunction "DO_DO") (pintype "output"))
    )
    (net (code "340") (name "Net-(D334-PadDI)") (class "Default")
      (node (ref "D334") (pin "DI") (pinfunction "DI_DI") (pintype "input"))
      (node (ref "D335") (pin "DO") (pinfunction "DO_DO") (pintype "output"))
    )
    (net (code "341") (name "Net-(D335-PadDI)") (class "Default")
      (node (ref "D335") (pin "DI") (pinfunction "DI_DI") (pintype "input"))
      (node (ref "D336") (pin "DO") (pinfunction "DO_DO") (pintype "output"))
    )
    (net (code "342") (name "Net-(D336-PadDI)") (class "Default")
      (node (ref "D336") (pin "DI") (pinfunction "DI_DI") (pintype "input"))
      (node (ref "D337") (pin "DO") (pinfunction "DO_DO") (pintype "output"))
    )
    (net (code "343") (name "Net-(D337-PadDI)") (class "Default")
      (node (ref "D337") (pin "DI") (pinfunction "DI_DI") (pintype "input"))
      (node (ref "D338") (pin "DO") (pinfunction "DO_DO") (pintype "output"))
    )
    (net (code "344") (name "Net-(D338-PadDI)") (class "Default")
      (node (ref "D338") (pin "DI") (pinfunction "DI_DI") (pintype "input"))
      (node (ref "D339") (pin "DO") (pinfunction "DO_DO") (pintype "output"))
    )
    (net (code "345") (name "Net-(D339-PadDI)") (class "Default")
      (node (ref "D339") (pin "DI") (pinfunction "DI_DI") (pintype "input"))
      (node (ref "D340") (pin "DO") (pinfunction "DO_DO") (pintype "output"))
    )
    (net (code "346") (name "Net-(D340-PadDI)") (class "Default")
      (node (ref "D340") (pin "DI") (pinfunction "DI_DI") (pintype "input"))
      (node (ref "D341") (pin "DO") (pinfunction "DO_DO") (pintype "output"))
    )
    (net (code "347") (name "Net-(D341-PadDI)") (class "Default")
      (node (ref "D341") (pin "DI") (pinfunction "DI_DI") (pintype "input"))
      (node (ref "D342") (pin "DO") (pinfunction "DO_DO") (pintype "output"))
    )
    (net (code "348") (name "Net-(D342-PadDI)") (class "Default")
      (node (ref "D342") (pin "DI") (pinfunction "DI_DI") (pintype "input"))
      (node (ref "D343") (pin "DO") (pinfunction "DO_DO") (pintype "output"))
    )
    (net (code "349") (name "Net-(D343-PadDI)") (class "Default")
      (node (ref "D343") (pin "DI") (pinfunction "DI_DI") (pintype "input"))
      (node (ref "D344") (pin "DO") (pinfunction "DO_DO") (pintype "output"))
    )
    (net (code "350") (name "Net-(D344-PadDI)") (class "Default")
      (node (ref "D344") (pin "DI") (pinfunction "DI_DI") (pintype "input"))
      (node (ref "D345") (pin "DO") (pinfunction "DO_DO") (pintype "output"))
    )
    (net (code "351") (name "Net-(D346-PadDI)") (class "Default")
      (node (ref "D346") (pin "DI") (pinfunction "DI_DI") (pintype "input"))
      (node (ref "D347") (pin "DO") (pinfunction "DO_DO") (pintype "output"))
    )
    (net (code "352") (name "Net-(D347-PadDI)") (class "Default")
      (node (ref "D347") (pin "DI") (pinfunction "DI_DI") (pintype "input"))
      (node (ref "D348") (pin "DO") (pinfunction "DO_DO") (pintype "output"))
    )
    (net (code "353") (name "Net-(D348-PadDI)") (class "Default")
      (node (ref "D348") (pin "DI") (pinfunction "DI_DI") (pintype "input"))
      (node (ref "D349") (pin "DO") (pinfunction "DO_DO") (pintype "output"))
    )
    (net (code "354") (name "Net-(D349-PadDI)") (class "Default")
      (node (ref "D349") (pin "DI") (pinfunction "DI_DI") (pintype "input"))
      (node (ref "D350") (pin "DO") (pinfunction "DO_DO") (pintype "output"))
    )
    (net (code "355") (name "Net-(D350-PadDI)") (class "Default")
      (node (ref "D350") (pin "DI") (pinfunction "DI_DI") (pintype "input"))
      (node (ref "D351") (pin "DO") (pinfunction "DO_DO") (pintype "output"))
    )
    (net (code "356") (name "Net-(D351-PadDI)") (class "Default")
      (node (ref "D351") (pin "DI") (pinfunction "DI_DI") (pintype "input"))
      (node (ref "D352") (pin "DO") (pinfunction "DO_DO") (pintype "output"))
    )
    (net (code "357") (name "Net-(D352-PadDI)") (class "Default")
      (node (ref "D352") (pin "DI") (pinfunction "DI_DI") (pintype "input"))
      (node (ref "D353") (pin "DO") (pinfunction "DO_DO") (pintype "output"))
    )
    (net (code "358") (name "Net-(D353-PadDI)") (class "Default")
      (node (ref "D353") (pin "DI") (pinfunction "DI_DI") (pintype "input"))
      (node (ref "D354") (pin "DO") (pinfunction "DO_DO") (pintype "output"))
    )
    (net (code "359") (name "Net-(D354-PadDI)") (class "Default")
      (node (ref "D354") (pin "DI") (pinfunction "DI_DI") (pintype "input"))
      (node (ref "D355") (pin "DO") (pinfunction "DO_DO") (pintype "output"))
    )
    (net (code "360") (name "Net-(D355-PadDI)") (class "Default")
      (node (ref "D355") (pin "DI") (pinfunction "DI_DI") (pintype "input"))
      (node (ref "D356") (pin "DO") (pinfunction "DO_DO") (pintype "output"))
    )
    (net (code "361") (name "Net-(D356-PadDI)") (class "Default")
      (node (ref "D356") (pin "DI") (pinfunction "DI_DI") (pintype "input"))
      (node (ref "D357") (pin "DO") (pinfunction "DO_DO") (pintype "output"))
    )
    (net (code "362") (name "Net-(D357-PadDI)") (class "Default")
      (node (ref "D357") (pin "DI") (pinfunction "DI_DI") (pintype "input"))
      (node (ref "D358") (pin "DO") (pinfunction "DO_DO") (pintype "output"))
    )
    (net (code "363") (name "Net-(D358-PadDI)") (class "Default")
      (node (ref "D358") (pin "DI") (pinfunction "DI_DI") (pintype "input"))
      (node (ref "D359") (pin "DO") (pinfunction "DO_DO") (pintype "output"))
    )
    (net (code "364") (name "Net-(D359-PadDI)") (class "Default")
      (node (ref "D359") (pin "DI") (pinfunction "DI_DI") (pintype "input"))
      (node (ref "D360") (pin "DO") (pinfunction "DO_DO") (pintype "output"))
    )
    (net (code "365") (name "Net-(D361-PadDI)") (class "Default")
      (node (ref "D361") (pin "DI") (pinfunction "DI_DI") (pintype "input"))
      (node (ref "D362") (pin "DO") (pinfunction "DO_DO") (pintype "output"))
    )
    (net (code "366") (name "Net-(D362-PadDI)") (class "Default")
      (node (ref "D362") (pin "DI") (pinfunction "DI_DI") (pintype "input"))
      (node (ref "D363") (pin "DO") (pinfunction "DO_DO") (pintype "output"))
    )
    (net (code "367") (name "Net-(D363-PadDI)") (class "Default")
      (node (ref "D363") (pin "DI") (pinfunction "DI_DI") (pintype "input"))
      (node (ref "D364") (pin "DO") (pinfunction "DO_DO") (pintype "output"))
    )
    (net (code "368") (name "Net-(D364-PadDI)") (class "Default")
      (node (ref "D364") (pin "DI") (pinfunction "DI_DI") (pintype "input"))
      (node (ref "D365") (pin "DO") (pinfunction "DO_DO") (pintype "output"))
    )
    (net (code "369") (name "Net-(D365-PadDI)") (class "Default")
      (node (ref "D365") (pin "DI") (pinfunction "DI_DI") (pintype "input"))
      (node (ref "D366") (pin "DO") (pinfunction "DO_DO") (pintype "output"))
    )
    (net (code "370") (name "Net-(D366-PadDI)") (class "Default")
      (node (ref "D366") (pin "DI") (pinfunction "DI_DI") (pintype "input"))
      (node (ref "D367") (pin "DO") (pinfunction "DO_DO") (pintype "output"))
    )
    (net (code "371") (name "Net-(D367-PadDI)") (class "Default")
      (node (ref "D367") (pin "DI") (pinfunction "DI_DI") (pintype "input"))
      (node (ref "D368") (pin "DO") (pinfunction "DO_DO") (pintype "output"))
    )
    (net (code "372") (name "Net-(D368-PadDI)") (class "Default")
      (node (ref "D368") (pin "DI") (pinfunction "DI_DI") (pintype "input"))
      (node (ref "D369") (pin "DO") (pinfunction "DO_DO") (pintype "output"))
    )
    (net (code "373") (name "Net-(D369-PadDI)") (class "Default")
      (node (ref "D369") (pin "DI") (pinfunction "DI_DI") (pintype "input"))
      (node (ref "D370") (pin "DO") (pinfunction "DO_DO") (pintype "output"))
    )
    (net (code "374") (name "Net-(D370-PadDI)") (class "Default")
      (node (ref "D370") (pin "DI") (pinfunction "DI_DI") (pintype "input"))
      (node (ref "D371") (pin "DO") (pinfunction "DO_DO") (pintype "output"))
    )
    (net (code "375") (name "Net-(D371-PadDI)") (class "Default")
      (node (ref "D371") (pin "DI") (pinfunction "DI_DI") (pintype "input"))
      (node (ref "D372") (pin "DO") (pinfunction "DO_DO") (pintype "output"))
    )
    (net (code "376") (name "Net-(D372-PadDI)") (class "Default")
      (node (ref "D372") (pin "DI") (pinfunction "DI_DI") (pintype "input"))
      (node (ref "D373") (pin "DO") (pinfunction "DO_DO") (pintype "output"))
    )
    (net (code "377") (name "Net-(D373-PadDI)") (class "Default")
      (node (ref "D373") (pin "DI") (pinfunction "DI_DI") (pintype "input"))
      (node (ref "D374") (pin "DO") (pinfunction "DO_DO") (pintype "output"))
    )
    (net (code "378") (name "Net-(D374-PadDI)") (class "Default")
      (node (ref "D374") (pin "DI") (pinfunction "DI_DI") (pintype "input"))
      (node (ref "D375") (pin "DO") (pinfunction "DO_DO") (pintype "output"))
    )
    (net (code "379") (name "Net-(D376-PadDI)") (class "Default")
      (node (ref "D376") (pin "DI") (pinfunction "DI_DI") (pintype "input"))
      (node (ref "D377") (pin "DO") (pinfunction "DO_DO") (pintype "output"))
    )
    (net (code "380") (name "Net-(D377-PadDI)") (class "Default")
      (node (ref "D377") (pin "DI") (pinfunction "DI_DI") (pintype "input"))
      (node (ref "D378") (pin "DO") (pinfunction "DO_DO") (pintype "output"))
    )
    (net (code "381") (name "Net-(D378-PadDI)") (class "Default")
      (node (ref "D378") (pin "DI") (pinfunction "DI_DI") (pintype "input"))
      (node (ref "D379") (pin "DO") (pinfunction "DO_DO") (pintype "output"))
    )
    (net (code "382") (name "Net-(D379-PadDI)") (class "Default")
      (node (ref "D379") (pin "DI") (pinfunction "DI_DI") (pintype "input"))
      (node (ref "D380") (pin "DO") (pinfunction "DO_DO") (pintype "output"))
    )
    (net (code "383") (name "Net-(D380-PadDI)") (class "Default")
      (node (ref "D380") (pin "DI") (pinfunction "DI_DI") (pintype "input"))
      (node (ref "D381") (pin "DO") (pinfunction "DO_DO") (pintype "output"))
    )
    (net (code "384") (name "Net-(D381-PadDI)") (class "Default")
      (node (ref "D381") (pin "DI") (pinfunction "DI_DI") (pintype "input"))
      (node (ref "D382") (pin "DO") (pinfunction "DO_DO") (pintype "output"))
    )
    (net (code "385") (name "Net-(D382-PadDI)") (class "Default")
      (node (ref "D382") (pin "DI") (pinfunction "DI_DI") (pintype "input"))
      (node (ref "D383") (pin "DO") (pinfunction "DO_DO") (pintype "output"))
    )
    (net (code "386") (name "Net-(D383-PadDI)") (class "Default")
      (node (ref "D383") (pin "DI") (pinfunction "DI_DI") (pintype "input"))
      (node (ref "D384") (pin "DO") (pinfunction "DO_DO") (pintype "output"))
    )
    (net (code "387") (name "Net-(D384-PadDI)") (class "Default")
      (node (ref "D384") (pin "DI") (pinfunction "DI_DI") (pintype "input"))
      (node (ref "D385") (pin "DO") (pinfunction "DO_DO") (pintype "output"))
    )
    (net (code "388") (name "Net-(D385-PadDI)") (class "Default")
      (node (ref "D385") (pin "DI") (pinfunction "DI_DI") (pintype "input"))
      (node (ref "D386") (pin "DO") (pinfunction "DO_DO") (pintype "output"))
    )
    (net (code "389") (name "Net-(D386-PadDI)") (class "Default")
      (node (ref "D386") (pin "DI") (pinfunction "DI_DI") (pintype "input"))
      (node (ref "D387") (pin "DO") (pinfunction "DO_DO") (pintype "output"))
    )
    (net (code "390") (name "Net-(D387-PadDI)") (class "Default")
      (node (ref "D387") (pin "DI") (pinfunction "DI_DI") (pintype "input"))
      (node (ref "D388") (pin "DO") (pinfunction "DO_DO") (pintype "output"))
    )
    (net (code "391") (name "Net-(D388-PadDI)") (class "Default")
      (node (ref "D388") (pin "DI") (pinfunction "DI_DI") (pintype "input"))
      (node (ref "D389") (pin "DO") (pinfunction "DO_DO") (pintype "output"))
    )
    (net (code "392") (name "Net-(D389-PadDI)") (class "Default")
      (node (ref "D389") (pin "DI") (pinfunction "DI_DI") (pintype "input"))
      (node (ref "D390") (pin "DO") (pinfunction "DO_DO") (pintype "output"))
    )
    (net (code "393") (name "Net-(D391-PadDI)") (class "Default")
      (node (ref "D391") (pin "DI") (pinfunction "DI_DI") (pintype "input"))
      (node (ref "D392") (pin "DO") (pinfunction "DO_DO") (pintype "output"))
    )
    (net (code "394") (name "Net-(D392-PadDI)") (class "Default")
      (node (ref "D392") (pin "DI") (pinfunction "DI_DI") (pintype "input"))
      (node (ref "D393") (pin "DO") (pinfunction "DO_DO") (pintype "output"))
    )
    (net (code "395") (name "Net-(D393-PadDI)") (class "Default")
      (node (ref "D393") (pin "DI") (pinfunction "DI_DI") (pintype "input"))
      (node (ref "D394") (pin "DO") (pinfunction "DO_DO") (pintype "output"))
    )
    (net (code "396") (name "Net-(D394-PadDI)") (class "Default")
      (node (ref "D394") (pin "DI") (pinfunction "DI_DI") (pintype "input"))
      (node (ref "D395") (pin "DO") (pinfunction "DO_DO") (pintype "output"))
    )
    (net (code "397") (name "Net-(D395-PadDI)") (class "Default")
      (node (ref "D395") (pin "DI") (pinfunction "DI_DI") (pintype "input"))
      (node (ref "D396") (pin "DO") (pinfunction "DO_DO") (pintype "output"))
    )
    (net (code "398") (name "Net-(D396-PadDI)") (class "Default")
      (node (ref "D396") (pin "DI") (pinfunction "DI_DI") (pintype "input"))
      (node (ref "D397") (pin "DO") (pinfunction "DO_DO") (pintype "output"))
    )
    (net (code "399") (name "Net-(D397-PadDI)") (class "Default")
      (node (ref "D397") (pin "DI") (pinfunction "DI_DI") (pintype "input"))
      (node (ref "D398") (pin "DO") (pinfunction "DO_DO") (pintype "output"))
    )
    (net (code "400") (name "Net-(D398-PadDI)") (class "Default")
      (node (ref "D398") (pin "DI") (pinfunction "DI_DI") (pintype "input"))
      (node (ref "D399") (pin "DO") (pinfunction "DO_DO") (pintype "output"))
    )
    (net (code "401") (name "Net-(D399-PadDI)") (class "Default")
      (node (ref "D399") (pin "DI") (pinfunction "DI_DI") (pintype "input"))
      (node (ref "D400") (pin "DO") (pinfunction "DO_DO") (pintype "output"))
    )
    (net (code "402") (name "Net-(D400-PadDI)") (class "Default")
      (node (ref "D400") (pin "DI") (pinfunction "DI_DI") (pintype "input"))
      (node (ref "D401") (pin "DO") (pinfunction "DO_DO") (pintype "output"))
    )
    (net (code "403") (name "Net-(D401-PadDI)") (class "Default")
      (node (ref "D401") (pin "DI") (pinfunction "DI_DI") (pintype "input"))
      (node (ref "D402") (pin "DO") (pinfunction "DO_DO") (pintype "output"))
    )
    (net (code "404") (name "Net-(D402-PadDI)") (class "Default")
      (node (ref "D402") (pin "DI") (pinfunction "DI_DI") (pintype "input"))
      (node (ref "D403") (pin "DO") (pinfunction "DO_DO") (pintype "output"))
    )
    (net (code "405") (name "Net-(D403-PadDI)") (class "Default")
      (node (ref "D403") (pin "DI") (pinfunction "DI_DI") (pintype "input"))
      (node (ref "D404") (pin "DO") (pinfunction "DO_DO") (pintype "output"))
    )
    (net (code "406") (name "Net-(D404-PadDI)") (class "Default")
      (node (ref "D404") (pin "DI") (pinfunction "DI_DI") (pintype "input"))
      (node (ref "D405") (pin "DO") (pinfunction "DO_DO") (pintype "output"))
    )
    (net (code "407") (name "Net-(JP1-Pad4)") (class "Default")
      (node (ref "JP1") (pin "4") (pinfunction "4_4") (pintype "passive"))
      (node (ref "R1") (pin "1") (pinfunction "1_1") (pintype "passive"))
    )
    (net (code "408") (name "VCC") (class "Default")
      (node (ref "C1") (pin "+") (pinfunction "+_+") (pintype "passive"))
      (node (ref "C10") (pin "+") (pinfunction "+_+") (pintype "passive"))
      (node (ref "C100") (pin "1") (pinfunction "1_1") (pintype "passive"))
      (node (ref "C101") (pin "1") (pinfunction "1_1") (pintype "passive"))
      (node (ref "C102") (pin "1") (pinfunction "1_1") (pintype "passive"))
      (node (ref "C103") (pin "1") (pinfunction "1_1") (pintype "passive"))
      (node (ref "C104") (pin "1") (pinfunction "1_1") (pintype "passive"))
      (node (ref "C105") (pin "1") (pinfunction "1_1") (pintype "passive"))
      (node (ref "C106") (pin "1") (pinfunction "1_1") (pintype "passive"))
      (node (ref "C107") (pin "1") (pinfunction "1_1") (pintype "passive"))
      (node (ref "C108") (pin "1") (pinfunction "1_1") (pintype "passive"))
      (node (ref "C109") (pin "1") (pinfunction "1_1") (pintype "passive"))
      (node (ref "C11") (pin "+") (pinfunction "+_+") (pintype "passive"))
      (node (ref "C110") (pin "1") (pinfunction "1_1") (pintype "passive"))
      (node (ref "C111") (pin "1") (pinfunction "1_1") (pintype "passive"))
      (node (ref "C112") (pin "1") (pinfunction "1_1") (pintype "passive"))
      (node (ref "C113") (pin "1") (pinfunction "1_1") (pintype "passive"))
      (node (ref "C114") (pin "1") (pinfunction "1_1") (pintype "passive"))
      (node (ref "C115") (pin "1") (pinfunction "1_1") (pintype "passive"))
      (node (ref "C116") (pin "1") (pinfunction "1_1") (pintype "passive"))
      (node (ref "C117") (pin "1") (pinfunction "1_1") (pintype "passive"))
      (node (ref "C118") (pin "1") (pinfunction "1_1") (pintype "passive"))
      (node (ref "C119") (pin "1") (pinfunction "1_1") (pintype "passive"))
      (node (ref "C12") (pin "+") (pinfunction "+_+") (pintype "passive"))
      (node (ref "C120") (pin "1") (pinfunction "1_1") (pintype "passive"))
      (node (ref "C121") (pin "1") (pinfunction "1_1") (pintype "passive"))
      (node (ref "C122") (pin "1") (pinfunction "1_1") (pintype "passive"))
      (node (ref "C123") (pin "1") (pinfunction "1_1") (pintype "passive"))
      (node (ref "C124") (pin "1") (pinfunction "1_1") (pintype "passive"))
      (node (ref "C125") (pin "1") (pinfunction "1_1") (pintype "passive"))
      (node (ref "C126") (pin "1") (pinfunction "1_1") (pintype "passive"))
      (node (ref "C127") (pin "1") (pinfunction "1_1") (pintype "passive"))
      (node (ref "C128") (pin "1") (pinfunction "1_1") (pintype "passive"))
      (node (ref "C129") (pin "1") (pinfunction "1_1") (pintype "passive"))
      (node (ref "C13") (pin "+") (pinfunction "+_+") (pintype "passive"))
      (node (ref "C130") (pin "1") (pinfunction "1_1") (pintype "passive"))
      (node (ref "C131") (pin "1") (pinfunction "1_1") (pintype "passive"))
      (node (ref "C132") (pin "1") (pinfunction "1_1") (pintype "passive"))
      (node (ref "C133") (pin "1") (pinfunction "1_1") (pintype "passive"))
      (node (ref "C134") (pin "1") (pinfunction "1_1") (pintype "passive"))
      (node (ref "C135") (pin "1") (pinfunction "1_1") (pintype "passive"))
      (node (ref "C136") (pin "1") (pinfunction "1_1") (pintype "passive"))
      (node (ref "C137") (pin "1") (pinfunction "1_1") (pintype "passive"))
      (node (ref "C138") (pin "1") (pinfunction "1_1") (pintype "passive"))
      (node (ref "C139") (pin "1") (pinfunction "1_1") (pintype "passive"))
      (node (ref "C14") (pin "+") (pinfunction "+_+") (pintype "passive"))
      (node (ref "C140") (pin "1") (pinfunction "1_1") (pintype "passive"))
      (node (ref "C141") (pin "1") (pinfunction "1_1") (pintype "passive"))
      (node (ref "C142") (pin "1") (pinfunction "1_1") (pintype "passive"))
      (node (ref "C143") (pin "1") (pinfunction "1_1") (pintype "passive"))
      (node (ref "C144") (pin "1") (pinfunction "1_1") (pintype "passive"))
      (node (ref "C145") (pin "1") (pinfunction "1_1") (pintype "passive"))
      (node (ref "C146") (pin "1") (pinfunction "1_1") (pintype "passive"))
      (node (ref "C147") (pin "1") (pinfunction "1_1") (pintype "passive"))
      (node (ref "C148") (pin "1") (pinfunction "1_1") (pintype "passive"))
      (node (ref "C149") (pin "1") (pinfunction "1_1") (pintype "passive"))
      (node (ref "C15") (pin "+") (pinfunction "+_+") (pintype "passive"))
      (node (ref "C150") (pin "1") (pinfunction "1_1") (pintype "passive"))
      (node (ref "C151") (pin "1") (pinfunction "1_1") (pintype "passive"))
      (node (ref "C152") (pin "1") (pinfunction "1_1") (pintype "passive"))
      (node (ref "C153") (pin "1") (pinfunction "1_1") (pintype "passive"))
      (node (ref "C154") (pin "1") (pinfunction "1_1") (pintype "passive"))
      (node (ref "C155") (pin "1") (pinfunction "1_1") (pintype "passive"))
      (node (ref "C156") (pin "1") (pinfunction "1_1") (pintype "passive"))
      (node (ref "C157") (pin "1") (pinfunction "1_1") (pintype "passive"))
      (node (ref "C158") (pin "1") (pinfunction "1_1") (pintype "passive"))
      (node (ref "C159") (pin "1") (pinfunction "1_1") (pintype "passive"))
      (node (ref "C16") (pin "+") (pinfunction "+_+") (pintype "passive"))
      (node (ref "C160") (pin "1") (pinfunction "1_1") (pintype "passive"))
      (node (ref "C161") (pin "1") (pinfunction "1_1") (pintype "passive"))
      (node (ref "C162") (pin "1") (pinfunction "1_1") (pintype "passive"))
      (node (ref "C163") (pin "1") (pinfunction "1_1") (pintype "passive"))
      (node (ref "C164") (pin "1") (pinfunction "1_1") (pintype "passive"))
      (node (ref "C165") (pin "1") (pinfunction "1_1") (pintype "passive"))
      (node (ref "C166") (pin "1") (pinfunction "1_1") (pintype "passive"))
      (node (ref "C167") (pin "1") (pinfunction "1_1") (pintype "passive"))
      (node (ref "C168") (pin "1") (pinfunction "1_1") (pintype "passive"))
      (node (ref "C169") (pin "1") (pinfunction "1_1") (pintype "passive"))
      (node (ref "C17") (pin "+") (pinfunction "+_+") (pintype "passive"))
      (node (ref "C18") (pin "+") (pinfunction "+_+") (pintype "passive"))
      (node (ref "C19") (pin "+") (pinfunction "+_+") (pintype "passive"))
      (node (ref "C2") (pin "+") (pinfunction "+_+") (pintype "passive"))
      (node (ref "C20") (pin "+") (pinfunction "+_+") (pintype "passive"))
      (node (ref "C21") (pin "+") (pinfunction "+_+") (pintype "passive"))
      (node (ref "C22") (pin "+") (pinfunction "+_+") (pintype "passive"))
      (node (ref "C23") (pin "+") (pinfunction "+_+") (pintype "passive"))
      (node (ref "C24") (pin "+") (pinfunction "+_+") (pintype "passive"))
      (node (ref "C25") (pin "1") (pinfunction "1_1") (pintype "passive"))
      (node (ref "C26") (pin "1") (pinfunction "1_1") (pintype "passive"))
      (node (ref "C27") (pin "1") (pinfunction "1_1") (pintype "passive"))
      (node (ref "C28") (pin "1") (pinfunction "1_1") (pintype "passive"))
      (node (ref "C29") (pin "1") (pinfunction "1_1") (pintype "passive"))
      (node (ref "C3") (pin "+") (pinfunction "+_+") (pintype "passive"))
      (node (ref "C30") (pin "1") (pinfunction "1_1") (pintype "passive"))
      (node (ref "C31") (pin "1") (pinfunction "1_1") (pintype "passive"))
      (node (ref "C32") (pin "1") (pinfunction "1_1") (pintype "passive"))
      (node (ref "C33") (pin "1") (pinfunction "1_1") (pintype "passive"))
      (node (ref "C34") (pin "1") (pinfunction "1_1") (pintype "passive"))
      (node (ref "C35") (pin "1") (pinfunction "1_1") (pintype "passive"))
      (node (ref "C36") (pin "1") (pinfunction "1_1") (pintype "passive"))
      (node (ref "C37") (pin "1") (pinfunction "1_1") (pintype "passive"))
      (node (ref "C38") (pin "1") (pinfunction "1_1") (pintype "passive"))
      (node (ref "C39") (pin "1") (pinfunction "1_1") (pintype "passive"))
      (node (ref "C4") (pin "+") (pinfunction "+_+") (pintype "passive"))
      (node (ref "C40") (pin "1") (pinfunction "1_1") (pintype "passive"))
      (node (ref "C41") (pin "1") (pinfunction "1_1") (pintype "passive"))
      (node (ref "C42") (pin "1") (pinfunction "1_1") (pintype "passive"))
      (node (ref "C43") (pin "1") (pinfunction "1_1") (pintype "passive"))
      (node (ref "C44") (pin "1") (pinfunction "1_1") (pintype "passive"))
      (node (ref "C45") (pin "1") (pinfunction "1_1") (pintype "passive"))
      (node (ref "C46") (pin "1") (pinfunction "1_1") (pintype "passive"))
      (node (ref "C47") (pin "1") (pinfunction "1_1") (pintype "passive"))
      (node (ref "C48") (pin "1") (pinfunction "1_1") (pintype "passive"))
      (node (ref "C49") (pin "1") (pinfunction "1_1") (pintype "passive"))
      (node (ref "C5") (pin "+") (pinfunction "+_+") (pintype "passive"))
      (node (ref "C50") (pin "1") (pinfunction "1_1") (pintype "passive"))
      (node (ref "C51") (pin "1") (pinfunction "1_1") (pintype "passive"))
      (node (ref "C52") (pin "1") (pinfunction "1_1") (pintype "passive"))
      (node (ref "C53") (pin "1") (pinfunction "1_1") (pintype "passive"))
      (node (ref "C54") (pin "1") (pinfunction "1_1") (pintype "passive"))
      (node (ref "C55") (pin "1") (pinfunction "1_1") (pintype "passive"))
      (node (ref "C56") (pin "1") (pinfunction "1_1") (pintype "passive"))
      (node (ref "C57") (pin "1") (pinfunction "1_1") (pintype "passive"))
      (node (ref "C58") (pin "1") (pinfunction "1_1") (pintype "passive"))
      (node (ref "C59") (pin "1") (pinfunction "1_1") (pintype "passive"))
      (node (ref "C6") (pin "+") (pinfunction "+_+") (pintype "passive"))
      (node (ref "C60") (pin "1") (pinfunction "1_1") (pintype "passive"))
      (node (ref "C61") (pin "1") (pinfunction "1_1") (pintype "passive"))
      (node (ref "C62") (pin "1") (pinfunction "1_1") (pintype "passive"))
      (node (ref "C63") (pin "1") (pinfunction "1_1") (pintype "passive"))
      (node (ref "C64") (pin "1") (pinfunction "1_1") (pintype "passive"))
      (node (ref "C65") (pin "1") (pinfunction "1_1") (pintype "passive"))
      (node (ref "C66") (pin "1") (pinfunction "1_1") (pintype "passive"))
      (node (ref "C67") (pin "1") (pinfunction "1_1") (pintype "passive"))
      (node (ref "C68") (pin "1") (pinfunction "1_1") (pintype "passive"))
      (node (ref "C69") (pin "1") (pinfunction "1_1") (pintype "passive"))
      (node (ref "C7") (pin "+") (pinfunction "+_+") (pintype "passive"))
      (node (ref "C70") (pin "1") (pinfunction "1_1") (pintype "passive"))
      (node (ref "C71") (pin "1") (pinfunction "1_1") (pintype "passive"))
      (node (ref "C72") (pin "1") (pinfunction "1_1") (pintype "passive"))
      (node (ref "C73") (pin "1") (pinfunction "1_1") (pintype "passive"))
      (node (ref "C74") (pin "1") (pinfunction "1_1") (pintype "passive"))
      (node (ref "C75") (pin "1") (pinfunction "1_1") (pintype "passive"))
      (node (ref "C76") (pin "1") (pinfunction "1_1") (pintype "passive"))
      (node (ref "C77") (pin "1") (pinfunction "1_1") (pintype "passive"))
      (node (ref "C78") (pin "1") (pinfunction "1_1") (pintype "passive"))
      (node (ref "C79") (pin "1") (pinfunction "1_1") (pintype "passive"))
      (node (ref "C8") (pin "+") (pinfunction "+_+") (pintype "passive"))
      (node (ref "C80") (pin "1") (pinfunction "1_1") (pintype "passive"))
      (node (ref "C81") (pin "1") (pinfunction "1_1") (pintype "passive"))
      (node (ref "C82") (pin "1") (pinfunction "1_1") (pintype "passive"))
      (node (ref "C83") (pin "1") (pinfunction "1_1") (pintype "passive"))
      (node (ref "C84") (pin "1") (pinfunction "1_1") (pintype "passive"))
      (node (ref "C85") (pin "1") (pinfunction "1_1") (pintype "passive"))
      (node (ref "C86") (pin "1") (pinfunction "1_1") (pintype "passive"))
      (node (ref "C87") (pin "1") (pinfunction "1_1") (pintype "passive"))
      (node (ref "C88") (pin "1") (pinfunction "1_1") (pintype "passive"))
      (node (ref "C89") (pin "1") (pinfunction "1_1") (pintype "passive"))
      (node (ref "C9") (pin "+") (pinfunction "+_+") (pintype "passive"))
      (node (ref "C90") (pin "1") (pinfunction "1_1") (pintype "passive"))
      (node (ref "C91") (pin "1") (pinfunction "1_1") (pintype "passive"))
      (node (ref "C92") (pin "1") (pinfunction "1_1") (pintype "passive"))
      (node (ref "C93") (pin "1") (pinfunction "1_1") (pintype "passive"))
      (node (ref "C94") (pin "1") (pinfunction "1_1") (pintype "passive"))
      (node (ref "C95") (pin "1") (pinfunction "1_1") (pintype "passive"))
      (node (ref "C96") (pin "1") (pinfunction "1_1") (pintype "passive"))
      (node (ref "C97") (pin "1") (pinfunction "1_1") (pintype "passive"))
      (node (ref "C98") (pin "1") (pinfunction "1_1") (pintype "passive"))
      (node (ref "C99") (pin "1") (pinfunction "1_1") (pintype "passive"))
      (node (ref "D1") (pin "VCC") (pinfunction "VCC_VCC") (pintype "power_in"))
      (node (ref "D10") (pin "VCC") (pinfunction "VCC_VCC") (pintype "power_in"))
      (node (ref "D100") (pin "VCC") (pinfunction "VCC_VCC") (pintype "power_in"))
      (node (ref "D101") (pin "VCC") (pinfunction "VCC_VCC") (pintype "power_in"))
      (node (ref "D102") (pin "VCC") (pinfunction "VCC_VCC") (pintype "power_in"))
      (node (ref "D103") (pin "VCC") (pinfunction "VCC_VCC") (pintype "power_in"))
      (node (ref "D104") (pin "VCC") (pinfunction "VCC_VCC") (pintype "power_in"))
      (node (ref "D105") (pin "VCC") (pinfunction "VCC_VCC") (pintype "power_in"))
      (node (ref "D106") (pin "VCC") (pinfunction "VCC_VCC") (pintype "power_in"))
      (node (ref "D107") (pin "VCC") (pinfunction "VCC_VCC") (pintype "power_in"))
      (node (ref "D108") (pin "VCC") (pinfunction "VCC_VCC") (pintype "power_in"))
      (node (ref "D109") (pin "VCC") (pinfunction "VCC_VCC") (pintype "power_in"))
      (node (ref "D11") (pin "VCC") (pinfunction "VCC_VCC") (pintype "power_in"))
      (node (ref "D110") (pin "VCC") (pinfunction "VCC_VCC") (pintype "power_in"))
      (node (ref "D111") (pin "VCC") (pinfunction "VCC_VCC") (pintype "power_in"))
      (node (ref "D112") (pin "VCC") (pinfunction "VCC_VCC") (pintype "power_in"))
      (node (ref "D113") (pin "VCC") (pinfunction "VCC_VCC") (pintype "power_in"))
      (node (ref "D114") (pin "VCC") (pinfunction "VCC_VCC") (pintype "power_in"))
      (node (ref "D115") (pin "VCC") (pinfunction "VCC_VCC") (pintype "power_in"))
      (node (ref "D116") (pin "VCC") (pinfunction "VCC_VCC") (pintype "power_in"))
      (node (ref "D117") (pin "VCC") (pinfunction "VCC_VCC") (pintype "power_in"))
      (node (ref "D118") (pin "VCC") (pinfunction "VCC_VCC") (pintype "power_in"))
      (node (ref "D119") (pin "VCC") (pinfunction "VCC_VCC") (pintype "power_in"))
      (node (ref "D12") (pin "VCC") (pinfunction "VCC_VCC") (pintype "power_in"))
      (node (ref "D120") (pin "VCC") (pinfunction "VCC_VCC") (pintype "power_in"))
      (node (ref "D121") (pin "VCC") (pinfunction "VCC_VCC") (pintype "power_in"))
      (node (ref "D122") (pin "VCC") (pinfunction "VCC_VCC") (pintype "power_in"))
      (node (ref "D123") (pin "VCC") (pinfunction "VCC_VCC") (pintype "power_in"))
      (node (ref "D124") (pin "VCC") (pinfunction "VCC_VCC") (pintype "power_in"))
      (node (ref "D125") (pin "VCC") (pinfunction "VCC_VCC") (pintype "power_in"))
      (node (ref "D126") (pin "VCC") (pinfunction "VCC_VCC") (pintype "power_in"))
      (node (ref "D127") (pin "VCC") (pinfunction "VCC_VCC") (pintype "power_in"))
      (node (ref "D128") (pin "VCC") (pinfunction "VCC_VCC") (pintype "power_in"))
      (node (ref "D129") (pin "VCC") (pinfunction "VCC_VCC") (pintype "power_in"))
      (node (ref "D13") (pin "VCC") (pinfunction "VCC_VCC") (pintype "power_in"))
      (node (ref "D130") (pin "VCC") (pinfunction "VCC_VCC") (pintype "power_in"))
      (node (ref "D131") (pin "VCC") (pinfunction "VCC_VCC") (pintype "power_in"))
      (node (ref "D132") (pin "VCC") (pinfunction "VCC_VCC") (pintype "power_in"))
      (node (ref "D133") (pin "VCC") (pinfunction "VCC_VCC") (pintype "power_in"))
      (node (ref "D134") (pin "VCC") (pinfunction "VCC_VCC") (pintype "power_in"))
      (node (ref "D135") (pin "VCC") (pinfunction "VCC_VCC") (pintype "power_in"))
      (node (ref "D136") (pin "VCC") (pinfunction "VCC_VCC") (pintype "power_in"))
      (node (ref "D137") (pin "VCC") (pinfunction "VCC_VCC") (pintype "power_in"))
      (node (ref "D138") (pin "VCC") (pinfunction "VCC_VCC") (pintype "power_in"))
      (node (ref "D139") (pin "VCC") (pinfunction "VCC_VCC") (pintype "power_in"))
      (node (ref "D14") (pin "VCC") (pinfunction "VCC_VCC") (pintype "power_in"))
      (node (ref "D140") (pin "VCC") (pinfunction "VCC_VCC") (pintype "power_in"))
      (node (ref "D141") (pin "VCC") (pinfunction "VCC_VCC") (pintype "power_in"))
      (node (ref "D142") (pin "VCC") (pinfunction "VCC_VCC") (pintype "power_in"))
      (node (ref "D143") (pin "VCC") (pinfunction "VCC_VCC") (pintype "power_in"))
      (node (ref "D144") (pin "VCC") (pinfunction "VCC_VCC") (pintype "power_in"))
      (node (ref "D145") (pin "VCC") (pinfunction "VCC_VCC") (pintype "power_in"))
      (node (ref "D146") (pin "VCC") (pinfunction "VCC_VCC") (pintype "power_in"))
      (node (ref "D147") (pin "VCC") (pinfunction "VCC_VCC") (pintype "power_in"))
      (node (ref "D148") (pin "VCC") (pinfunction "VCC_VCC") (pintype "power_in"))
      (node (ref "D149") (pin "VCC") (pinfunction "VCC_VCC") (pintype "power_in"))
      (node (ref "D15") (pin "VCC") (pinfunction "VCC_VCC") (pintype "power_in"))
      (node (ref "D150") (pin "VCC") (pinfunction "VCC_VCC") (pintype "power_in"))
      (node (ref "D151") (pin "VCC") (pinfunction "VCC_VCC") (pintype "power_in"))
      (node (ref "D152") (pin "VCC") (pinfunction "VCC_VCC") (pintype "power_in"))
      (node (ref "D153") (pin "VCC") (pinfunction "VCC_VCC") (pintype "power_in"))
      (node (ref "D154") (pin "VCC") (pinfunction "VCC_VCC") (pintype "power_in"))
      (node (ref "D155") (pin "VCC") (pinfunction "VCC_VCC") (pintype "power_in"))
      (node (ref "D156") (pin "VCC") (pinfunction "VCC_VCC") (pintype "power_in"))
      (node (ref "D157") (pin "VCC") (pinfunction "VCC_VCC") (pintype "power_in"))
      (node (ref "D158") (pin "VCC") (pinfunction "VCC_VCC") (pintype "power_in"))
      (node (ref "D159") (pin "VCC") (pinfunction "VCC_VCC") (pintype "power_in"))
      (node (ref "D16") (pin "VCC") (pinfunction "VCC_VCC") (pintype "power_in"))
      (node (ref "D160") (pin "VCC") (pinfunction "VCC_VCC") (pintype "power_in"))
      (node (ref "D161") (pin "VCC") (pinfunction "VCC_VCC") (pintype "power_in"))
      (node (ref "D162") (pin "VCC") (pinfunction "VCC_VCC") (pintype "power_in"))
      (node (ref "D163") (pin "VCC") (pinfunction "VCC_VCC") (pintype "power_in"))
      (node (ref "D164") (pin "VCC") (pinfunction "VCC_VCC") (pintype "power_in"))
      (node (ref "D165") (pin "VCC") (pinfunction "VCC_VCC") (pintype "power_in"))
      (node (ref "D166") (pin "VCC") (pinfunction "VCC_VCC") (pintype "power_in"))
      (node (ref "D167") (pin "VCC") (pinfunction "VCC_VCC") (pintype "power_in"))
      (node (ref "D168") (pin "VCC") (pinfunction "VCC_VCC") (pintype "power_in"))
      (node (ref "D169") (pin "VCC") (pinfunction "VCC_VCC") (pintype "power_in"))
      (node (ref "D17") (pin "VCC") (pinfunction "VCC_VCC") (pintype "power_in"))
      (node (ref "D170") (pin "VCC") (pinfunction "VCC_VCC") (pintype "power_in"))
      (node (ref "D171") (pin "VCC") (pinfunction "VCC_VCC") (pintype "power_in"))
      (node (ref "D172") (pin "VCC") (pinfunction "VCC_VCC") (pintype "power_in"))
      (node (ref "D173") (pin "VCC") (pinfunction "VCC_VCC") (pintype "power_in"))
      (node (ref "D174") (pin "VCC") (pinfunction "VCC_VCC") (pintype "power_in"))
      (node (ref "D175") (pin "VCC") (pinfunction "VCC_VCC") (pintype "power_in"))
      (node (ref "D176") (pin "VCC") (pinfunction "VCC_VCC") (pintype "power_in"))
      (node (ref "D177") (pin "VCC") (pinfunction "VCC_VCC") (pintype "power_in"))
      (node (ref "D178") (pin "VCC") (pinfunction "VCC_VCC") (pintype "power_in"))
      (node (ref "D179") (pin "VCC") (pinfunction "VCC_VCC") (pintype "power_in"))
      (node (ref "D18") (pin "VCC") (pinfunction "VCC_VCC") (pintype "power_in"))
      (node (ref "D180") (pin "VCC") (pinfunction "VCC_VCC") (pintype "power_in"))
      (node (ref "D181") (pin "VCC") (pinfunction "VCC_VCC") (pintype "power_in"))
      (node (ref "D182") (pin "VCC") (pinfunction "VCC_VCC") (pintype "power_in"))
      (node (ref "D183") (pin "VCC") (pinfunction "VCC_VCC") (pintype "power_in"))
      (node (ref "D184") (pin "VCC") (pinfunction "VCC_VCC") (pintype "power_in"))
      (node (ref "D185") (pin "VCC") (pinfunction "VCC_VCC") (pintype "power_in"))
      (node (ref "D186") (pin "VCC") (pinfunction "VCC_VCC") (pintype "power_in"))
      (node (ref "D187") (pin "VCC") (pinfunction "VCC_VCC") (pintype "power_in"))
      (node (ref "D188") (pin "VCC") (pinfunction "VCC_VCC") (pintype "power_in"))
      (node (ref "D189") (pin "VCC") (pinfunction "VCC_VCC") (pintype "power_in"))
      (node (ref "D19") (pin "VCC") (pinfunction "VCC_VCC") (pintype "power_in"))
      (node (ref "D190") (pin "VCC") (pinfunction "VCC_VCC") (pintype "power_in"))
      (node (ref "D191") (pin "VCC") (pinfunction "VCC_VCC") (pintype "power_in"))
      (node (ref "D192") (pin "VCC") (pinfunction "VCC_VCC") (pintype "power_in"))
      (node (ref "D193") (pin "VCC") (pinfunction "VCC_VCC") (pintype "power_in"))
      (node (ref "D194") (pin "VCC") (pinfunction "VCC_VCC") (pintype "power_in"))
      (node (ref "D195") (pin "VCC") (pinfunction "VCC_VCC") (pintype "power_in"))
      (node (ref "D196") (pin "VCC") (pinfunction "VCC_VCC") (pintype "power_in"))
      (node (ref "D197") (pin "VCC") (pinfunction "VCC_VCC") (pintype "power_in"))
      (node (ref "D198") (pin "VCC") (pinfunction "VCC_VCC") (pintype "power_in"))
      (node (ref "D199") (pin "VCC") (pinfunction "VCC_VCC") (pintype "power_in"))
      (node (ref "D2") (pin "VCC") (pinfunction "VCC_VCC") (pintype "power_in"))
      (node (ref "D20") (pin "VCC") (pinfunction "VCC_VCC") (pintype "power_in"))
      (node (ref "D200") (pin "VCC") (pinfunction "VCC_VCC") (pintype "power_in"))
      (node (ref "D201") (pin "VCC") (pinfunction "VCC_VCC") (pintype "power_in"))
      (node (ref "D202") (pin "VCC") (pinfunction "VCC_VCC") (pintype "power_in"))
      (node (ref "D203") (pin "VCC") (pinfunction "VCC_VCC") (pintype "power_in"))
      (node (ref "D204") (pin "VCC") (pinfunction "VCC_VCC") (pintype "power_in"))
      (node (ref "D205") (pin "VCC") (pinfunction "VCC_VCC") (pintype "power_in"))
      (node (ref "D206") (pin "VCC") (pinfunction "VCC_VCC") (pintype "power_in"))
      (node (ref "D207") (pin "VCC") (pinfunction "VCC_VCC") (pintype "power_in"))
      (node (ref "D208") (pin "VCC") (pinfunction "VCC_VCC") (pintype "power_in"))
      (node (ref "D209") (pin "VCC") (pinfunction "VCC_VCC") (pintype "power_in"))
      (node (ref "D21") (pin "VCC") (pinfunction "VCC_VCC") (pintype "power_in"))
      (node (ref "D210") (pin "VCC") (pinfunction "VCC_VCC") (pintype "power_in"))
      (node (ref "D211") (pin "VCC") (pinfunction "VCC_VCC") (pintype "power_in"))
      (node (ref "D212") (pin "VCC") (pinfunction "VCC_VCC") (pintype "power_in"))
      (node (ref "D213") (pin "VCC") (pinfunction "VCC_VCC") (pintype "power_in"))
      (node (ref "D214") (pin "VCC") (pinfunction "VCC_VCC") (pintype "power_in"))
      (node (ref "D215") (pin "VCC") (pinfunction "VCC_VCC") (pintype "power_in"))
      (node (ref "D216") (pin "VCC") (pinfunction "VCC_VCC") (pintype "power_in"))
      (node (ref "D217") (pin "VCC") (pinfunction "VCC_VCC") (pintype "power_in"))
      (node (ref "D218") (pin "VCC") (pinfunction "VCC_VCC") (pintype "power_in"))
      (node (ref "D219") (pin "VCC") (pinfunction "VCC_VCC") (pintype "power_in"))
      (node (ref "D22") (pin "VCC") (pinfunction "VCC_VCC") (pintype "power_in"))
      (node (ref "D220") (pin "VCC") (pinfunction "VCC_VCC") (pintype "power_in"))
      (node (ref "D221") (pin "VCC") (pinfunction "VCC_VCC") (pintype "power_in"))
      (node (ref "D222") (pin "VCC") (pinfunction "VCC_VCC") (pintype "power_in"))
      (node (ref "D223") (pin "VCC") (pinfunction "VCC_VCC") (pintype "power_in"))
      (node (ref "D224") (pin "VCC") (pinfunction "VCC_VCC") (pintype "power_in"))
      (node (ref "D225") (pin "VCC") (pinfunction "VCC_VCC") (pintype "power_in"))
      (node (ref "D226") (pin "VCC") (pinfunction "VCC_VCC") (pintype "power_in"))
      (node (ref "D227") (pin "VCC") (pinfunction "VCC_VCC") (pintype "power_in"))
      (node (ref "D228") (pin "VCC") (pinfunction "VCC_VCC") (pintype "power_in"))
      (node (ref "D229") (pin "VCC") (pinfunction "VCC_VCC") (pintype "power_in"))
      (node (ref "D23") (pin "VCC") (pinfunction "VCC_VCC") (pintype "power_in"))
      (node (ref "D230") (pin "VCC") (pinfunction "VCC_VCC") (pintype "power_in"))
      (node (ref "D231") (pin "VCC") (pinfunction "VCC_VCC") (pintype "power_in"))
      (node (ref "D232") (pin "VCC") (pinfunction "VCC_VCC") (pintype "power_in"))
      (node (ref "D233") (pin "VCC") (pinfunction "VCC_VCC") (pintype "power_in"))
      (node (ref "D234") (pin "VCC") (pinfunction "VCC_VCC") (pintype "power_in"))
      (node (ref "D235") (pin "VCC") (pinfunction "VCC_VCC") (pintype "power_in"))
      (node (ref "D236") (pin "VCC") (pinfunction "VCC_VCC") (pintype "power_in"))
      (node (ref "D237") (pin "VCC") (pinfunction "VCC_VCC") (pintype "power_in"))
      (node (ref "D238") (pin "VCC") (pinfunction "VCC_VCC") (pintype "power_in"))
      (node (ref "D239") (pin "VCC") (pinfunction "VCC_VCC") (pintype "power_in"))
      (node (ref "D24") (pin "VCC") (pinfunction "VCC_VCC") (pintype "power_in"))
      (node (ref "D240") (pin "VCC") (pinfunction "VCC_VCC") (pintype "power_in"))
      (node (ref "D241") (pin "VCC") (pinfunction "VCC_VCC") (pintype "power_in"))
      (node (ref "D242") (pin "VCC") (pinfunction "VCC_VCC") (pintype "power_in"))
      (node (ref "D243") (pin "VCC") (pinfunction "VCC_VCC") (pintype "power_in"))
      (node (ref "D244") (pin "VCC") (pinfunction "VCC_VCC") (pintype "power_in"))
      (node (ref "D245") (pin "VCC") (pinfunction "VCC_VCC") (pintype "power_in"))
      (node (ref "D246") (pin "VCC") (pinfunction "VCC_VCC") (pintype "power_in"))
      (node (ref "D247") (pin "VCC") (pinfunction "VCC_VCC") (pintype "power_in"))
      (node (ref "D248") (pin "VCC") (pinfunction "VCC_VCC") (pintype "power_in"))
      (node (ref "D249") (pin "VCC") (pinfunction "VCC_VCC") (pintype "power_in"))
      (node (ref "D25") (pin "VCC") (pinfunction "VCC_VCC") (pintype "power_in"))
      (node (ref "D250") (pin "VCC") (pinfunction "VCC_VCC") (pintype "power_in"))
      (node (ref "D251") (pin "VCC") (pinfunction "VCC_VCC") (pintype "power_in"))
      (node (ref "D252") (pin "VCC") (pinfunction "VCC_VCC") (pintype "power_in"))
      (node (ref "D253") (pin "VCC") (pinfunction "VCC_VCC") (pintype "power_in"))
      (node (ref "D254") (pin "VCC") (pinfunction "VCC_VCC") (pintype "power_in"))
      (node (ref "D255") (pin "VCC") (pinfunction "VCC_VCC") (pintype "power_in"))
      (node (ref "D256") (pin "VCC") (pinfunction "VCC_VCC") (pintype "power_in"))
      (node (ref "D257") (pin "VCC") (pinfunction "VCC_VCC") (pintype "power_in"))
      (node (ref "D258") (pin "VCC") (pinfunction "VCC_VCC") (pintype "power_in"))
      (node (ref "D259") (pin "VCC") (pinfunction "VCC_VCC") (pintype "power_in"))
      (node (ref "D26") (pin "VCC") (pinfunction "VCC_VCC") (pintype "power_in"))
      (node (ref "D260") (pin "VCC") (pinfunction "VCC_VCC") (pintype "power_in"))
      (node (ref "D261") (pin "VCC") (pinfunction "VCC_VCC") (pintype "power_in"))
      (node (ref "D262") (pin "VCC") (pinfunction "VCC_VCC") (pintype "power_in"))
      (node (ref "D263") (pin "VCC") (pinfunction "VCC_VCC") (pintype "power_in"))
      (node (ref "D264") (pin "VCC") (pinfunction "VCC_VCC") (pintype "power_in"))
      (node (ref "D265") (pin "VCC") (pinfunction "VCC_VCC") (pintype "power_in"))
      (node (ref "D266") (pin "VCC") (pinfunction "VCC_VCC") (pintype "power_in"))
      (node (ref "D267") (pin "VCC") (pinfunction "VCC_VCC") (pintype "power_in"))
      (node (ref "D268") (pin "VCC") (pinfunction "VCC_VCC") (pintype "power_in"))
      (node (ref "D269") (pin "VCC") (pinfunction "VCC_VCC") (pintype "power_in"))
      (node (ref "D27") (pin "VCC") (pinfunction "VCC_VCC") (pintype "power_in"))
      (node (ref "D270") (pin "VCC") (pinfunction "VCC_VCC") (pintype "power_in"))
      (node (ref "D271") (pin "VCC") (pinfunction "VCC_VCC") (pintype "power_in"))
      (node (ref "D272") (pin "VCC") (pinfunction "VCC_VCC") (pintype "power_in"))
      (node (ref "D273") (pin "VCC") (pinfunction "VCC_VCC") (pintype "power_in"))
      (node (ref "D274") (pin "VCC") (pinfunction "VCC_VCC") (pintype "power_in"))
      (node (ref "D275") (pin "VCC") (pinfunction "VCC_VCC") (pintype "power_in"))
      (node (ref "D276") (pin "VCC") (pinfunction "VCC_VCC") (pintype "power_in"))
      (node (ref "D277") (pin "VCC") (pinfunction "VCC_VCC") (pintype "power_in"))
      (node (ref "D278") (pin "VCC") (pinfunction "VCC_VCC") (pintype "power_in"))
      (node (ref "D279") (pin "VCC") (pinfunction "VCC_VCC") (pintype "power_in"))
      (node (ref "D28") (pin "VCC") (pinfunction "VCC_VCC") (pintype "power_in"))
      (node (ref "D280") (pin "VCC") (pinfunction "VCC_VCC") (pintype "power_in"))
      (node (ref "D281") (pin "VCC") (pinfunction "VCC_VCC") (pintype "power_in"))
      (node (ref "D282") (pin "VCC") (pinfunction "VCC_VCC") (pintype "power_in"))
      (node (ref "D283") (pin "VCC") (pinfunction "VCC_VCC") (pintype "power_in"))
      (node (ref "D284") (pin "VCC") (pinfunction "VCC_VCC") (pintype "power_in"))
      (node (ref "D285") (pin "VCC") (pinfunction "VCC_VCC") (pintype "power_in"))
      (node (ref "D286") (pin "VCC") (pinfunction "VCC_VCC") (pintype "power_in"))
      (node (ref "D287") (pin "VCC") (pinfunction "VCC_VCC") (pintype "power_in"))
      (node (ref "D288") (pin "VCC") (pinfunction "VCC_VCC") (pintype "power_in"))
      (node (ref "D289") (pin "VCC") (pinfunction "VCC_VCC") (pintype "power_in"))
      (node (ref "D29") (pin "VCC") (pinfunction "VCC_VCC") (pintype "power_in"))
      (node (ref "D290") (pin "VCC") (pinfunction "VCC_VCC") (pintype "power_in"))
      (node (ref "D291") (pin "VCC") (pinfunction "VCC_VCC") (pintype "power_in"))
      (node (ref "D292") (pin "VCC") (pinfunction "VCC_VCC") (pintype "power_in"))
      (node (ref "D293") (pin "VCC") (pinfunction "VCC_VCC") (pintype "power_in"))
      (node (ref "D294") (pin "VCC") (pinfunction "VCC_VCC") (pintype "power_in"))
      (node (ref "D295") (pin "VCC") (pinfunction "VCC_VCC") (pintype "power_in"))
      (node (ref "D296") (pin "VCC") (pinfunction "VCC_VCC") (pintype "power_in"))
      (node (ref "D297") (pin "VCC") (pinfunction "VCC_VCC") (pintype "power_in"))
      (node (ref "D298") (pin "VCC") (pinfunction "VCC_VCC") (pintype "power_in"))
      (node (ref "D299") (pin "VCC") (pinfunction "VCC_VCC") (pintype "power_in"))
      (node (ref "D3") (pin "VCC") (pinfunction "VCC_VCC") (pintype "power_in"))
      (node (ref "D30") (pin "VCC") (pinfunction "VCC_VCC") (pintype "power_in"))
      (node (ref "D300") (pin "VCC") (pinfunction "VCC_VCC") (pintype "power_in"))
      (node (ref "D301") (pin "VCC") (pinfunction "VCC_VCC") (pintype "power_in"))
      (node (ref "D302") (pin "VCC") (pinfunction "VCC_VCC") (pintype "power_in"))
      (node (ref "D303") (pin "VCC") (pinfunction "VCC_VCC") (pintype "power_in"))
      (node (ref "D304") (pin "VCC") (pinfunction "VCC_VCC") (pintype "power_in"))
      (node (ref "D305") (pin "VCC") (pinfunction "VCC_VCC") (pintype "power_in"))
      (node (ref "D306") (pin "VCC") (pinfunction "VCC_VCC") (pintype "power_in"))
      (node (ref "D307") (pin "VCC") (pinfunction "VCC_VCC") (pintype "power_in"))
      (node (ref "D308") (pin "VCC") (pinfunction "VCC_VCC") (pintype "power_in"))
      (node (ref "D309") (pin "VCC") (pinfunction "VCC_VCC") (pintype "power_in"))
      (node (ref "D31") (pin "VCC") (pinfunction "VCC_VCC") (pintype "power_in"))
      (node (ref "D310") (pin "VCC") (pinfunction "VCC_VCC") (pintype "power_in"))
      (node (ref "D311") (pin "VCC") (pinfunction "VCC_VCC") (pintype "power_in"))
      (node (ref "D312") (pin "VCC") (pinfunction "VCC_VCC") (pintype "power_in"))
      (node (ref "D313") (pin "VCC") (pinfunction "VCC_VCC") (pintype "power_in"))
      (node (ref "D314") (pin "VCC") (pinfunction "VCC_VCC") (pintype "power_in"))
      (node (ref "D315") (pin "VCC") (pinfunction "VCC_VCC") (pintype "power_in"))
      (node (ref "D316") (pin "VCC") (pinfunction "VCC_VCC") (pintype "power_in"))
      (node (ref "D317") (pin "VCC") (pinfunction "VCC_VCC") (pintype "power_in"))
      (node (ref "D318") (pin "VCC") (pinfunction "VCC_VCC") (pintype "power_in"))
      (node (ref "D319") (pin "VCC") (pinfunction "VCC_VCC") (pintype "power_in"))
      (node (ref "D32") (pin "VCC") (pinfunction "VCC_VCC") (pintype "power_in"))
      (node (ref "D320") (pin "VCC") (pinfunction "VCC_VCC") (pintype "power_in"))
      (node (ref "D321") (pin "VCC") (pinfunction "VCC_VCC") (pintype "power_in"))
      (node (ref "D322") (pin "VCC") (pinfunction "VCC_VCC") (pintype "power_in"))
      (node (ref "D323") (pin "VCC") (pinfunction "VCC_VCC") (pintype "power_in"))
      (node (ref "D324") (pin "VCC") (pinfunction "VCC_VCC") (pintype "power_in"))
      (node (ref "D325") (pin "VCC") (pinfunction "VCC_VCC") (pintype "power_in"))
      (node (ref "D326") (pin "VCC") (pinfunction "VCC_VCC") (pintype "power_in"))
      (node (ref "D327") (pin "VCC") (pinfunction "VCC_VCC") (pintype "power_in"))
      (node (ref "D328") (pin "VCC") (pinfunction "VCC_VCC") (pintype "power_in"))
      (node (ref "D329") (pin "VCC") (pinfunction "VCC_VCC") (pintype "power_in"))
      (node (ref "D33") (pin "VCC") (pinfunction "VCC_VCC") (pintype "power_in"))
      (node (ref "D330") (pin "VCC") (pinfunction "VCC_VCC") (pintype "power_in"))
      (node (ref "D331") (pin "VCC") (pinfunction "VCC_VCC") (pintype "power_in"))
      (node (ref "D332") (pin "VCC") (pinfunction "VCC_VCC") (pintype "power_in"))
      (node (ref "D333") (pin "VCC") (pinfunction "VCC_VCC") (pintype "power_in"))
      (node (ref "D334") (pin "VCC") (pinfunction "VCC_VCC") (pintype "power_in"))
      (node (ref "D335") (pin "VCC") (pinfunction "VCC_VCC") (pintype "power_in"))
      (node (ref "D336") (pin "VCC") (pinfunction "VCC_VCC") (pintype "power_in"))
      (node (ref "D337") (pin "VCC") (pinfunction "VCC_VCC") (pintype "power_in"))
      (node (ref "D338") (pin "VCC") (pinfunction "VCC_VCC") (pintype "power_in"))
      (node (ref "D339") (pin "VCC") (pinfunction "VCC_VCC") (pintype "power_in"))
      (node (ref "D34") (pin "VCC") (pinfunction "VCC_VCC") (pintype "power_in"))
      (node (ref "D340") (pin "VCC") (pinfunction "VCC_VCC") (pintype "power_in"))
      (node (ref "D341") (pin "VCC") (pinfunction "VCC_VCC") (pintype "power_in"))
      (node (ref "D342") (pin "VCC") (pinfunction "VCC_VCC") (pintype "power_in"))
      (node (ref "D343") (pin "VCC") (pinfunction "VCC_VCC") (pintype "power_in"))
      (node (ref "D344") (pin "VCC") (pinfunction "VCC_VCC") (pintype "power_in"))
      (node (ref "D345") (pin "VCC") (pinfunction "VCC_VCC") (pintype "power_in"))
      (node (ref "D346") (pin "VCC") (pinfunction "VCC_VCC") (pintype "power_in"))
      (node (ref "D347") (pin "VCC") (pinfunction "VCC_VCC") (pintype "power_in"))
      (node (ref "D348") (pin "VCC") (pinfunction "VCC_VCC") (pintype "power_in"))
      (node (ref "D349") (pin "VCC") (pinfunction "VCC_VCC") (pintype "power_in"))
      (node (ref "D35") (pin "VCC") (pinfunction "VCC_VCC") (pintype "power_in"))
      (node (ref "D350") (pin "VCC") (pinfunction "VCC_VCC") (pintype "power_in"))
      (node (ref "D351") (pin "VCC") (pinfunction "VCC_VCC") (pintype "power_in"))
      (node (ref "D352") (pin "VCC") (pinfunction "VCC_VCC") (pintype "power_in"))
      (node (ref "D353") (pin "VCC") (pinfunction "VCC_VCC") (pintype "power_in"))
      (node (ref "D354") (pin "VCC") (pinfunction "VCC_VCC") (pintype "power_in"))
      (node (ref "D355") (pin "VCC") (pinfunction "VCC_VCC") (pintype "power_in"))
      (node (ref "D356") (pin "VCC") (pinfunction "VCC_VCC") (pintype "power_in"))
      (node (ref "D357") (pin "VCC") (pinfunction "VCC_VCC") (pintype "power_in"))
      (node (ref "D358") (pin "VCC") (pinfunction "VCC_VCC") (pintype "power_in"))
      (node (ref "D359") (pin "VCC") (pinfunction "VCC_VCC") (pintype "power_in"))
      (node (ref "D36") (pin "VCC") (pinfunction "VCC_VCC") (pintype "power_in"))
      (node (ref "D360") (pin "VCC") (pinfunction "VCC_VCC") (pintype "power_in"))
      (node (ref "D361") (pin "VCC") (pinfunction "VCC_VCC") (pintype "power_in"))
      (node (ref "D362") (pin "VCC") (pinfunction "VCC_VCC") (pintype "power_in"))
      (node (ref "D363") (pin "VCC") (pinfunction "VCC_VCC") (pintype "power_in"))
      (node (ref "D364") (pin "VCC") (pinfunction "VCC_VCC") (pintype "power_in"))
      (node (ref "D365") (pin "VCC") (pinfunction "VCC_VCC") (pintype "power_in"))
      (node (ref "D366") (pin "VCC") (pinfunction "VCC_VCC") (pintype "power_in"))
      (node (ref "D367") (pin "VCC") (pinfunction "VCC_VCC") (pintype "power_in"))
      (node (ref "D368") (pin "VCC") (pinfunction "VCC_VCC") (pintype "power_in"))
      (node (ref "D369") (pin "VCC") (pinfunction "VCC_VCC") (pintype "power_in"))
      (node (ref "D37") (pin "VCC") (pinfunction "VCC_VCC") (pintype "power_in"))
      (node (ref "D370") (pin "VCC") (pinfunction "VCC_VCC") (pintype "power_in"))
      (node (ref "D371") (pin "VCC") (pinfunction "VCC_VCC") (pintype "power_in"))
      (node (ref "D372") (pin "VCC") (pinfunction "VCC_VCC") (pintype "power_in"))
      (node (ref "D373") (pin "VCC") (pinfunction "VCC_VCC") (pintype "power_in"))
      (node (ref "D374") (pin "VCC") (pinfunction "VCC_VCC") (pintype "power_in"))
      (node (ref "D375") (pin "VCC") (pinfunction "VCC_VCC") (pintype "power_in"))
      (node (ref "D376") (pin "VCC") (pinfunction "VCC_VCC") (pintype "power_in"))
      (node (ref "D377") (pin "VCC") (pinfunction "VCC_VCC") (pintype "power_in"))
      (node (ref "D378") (pin "VCC") (pinfunction "VCC_VCC") (pintype "power_in"))
      (node (ref "D379") (pin "VCC") (pinfunction "VCC_VCC") (pintype "power_in"))
      (node (ref "D38") (pin "VCC") (pinfunction "VCC_VCC") (pintype "power_in"))
      (node (ref "D380") (pin "VCC") (pinfunction "VCC_VCC") (pintype "power_in"))
      (node (ref "D381") (pin "VCC") (pinfunction "VCC_VCC") (pintype "power_in"))
      (node (ref "D382") (pin "VCC") (pinfunction "VCC_VCC") (pintype "power_in"))
      (node (ref "D383") (pin "VCC") (pinfunction "VCC_VCC") (pintype "power_in"))
      (node (ref "D384") (pin "VCC") (pinfunction "VCC_VCC") (pintype "power_in"))
      (node (ref "D385") (pin "VCC") (pinfunction "VCC_VCC") (pintype "power_in"))
      (node (ref "D386") (pin "VCC") (pinfunction "VCC_VCC") (pintype "power_in"))
      (node (ref "D387") (pin "VCC") (pinfunction "VCC_VCC") (pintype "power_in"))
      (node (ref "D388") (pin "VCC") (pinfunction "VCC_VCC") (pintype "power_in"))
      (node (ref "D389") (pin "VCC") (pinfunction "VCC_VCC") (pintype "power_in"))
      (node (ref "D39") (pin "VCC") (pinfunction "VCC_VCC") (pintype "power_in"))
      (node (ref "D390") (pin "VCC") (pinfunction "VCC_VCC") (pintype "power_in"))
      (node (ref "D391") (pin "VCC") (pinfunction "VCC_VCC") (pintype "power_in"))
      (node (ref "D392") (pin "VCC") (pinfunction "VCC_VCC") (pintype "power_in"))
      (node (ref "D393") (pin "VCC") (pinfunction "VCC_VCC") (pintype "power_in"))
      (node (ref "D394") (pin "VCC") (pinfunction "VCC_VCC") (pintype "power_in"))
      (node (ref "D395") (pin "VCC") (pinfunction "VCC_VCC") (pintype "power_in"))
      (node (ref "D396") (pin "VCC") (pinfunction "VCC_VCC") (pintype "power_in"))
      (node (ref "D397") (pin "VCC") (pinfunction "VCC_VCC") (pintype "power_in"))
      (node (ref "D398") (pin "VCC") (pinfunction "VCC_VCC") (pintype "power_in"))
      (node (ref "D399") (pin "VCC") (pinfunction "VCC_VCC") (pintype "power_in"))
      (node (ref "D4") (pin "VCC") (pinfunction "VCC_VCC") (pintype "power_in"))
      (node (ref "D40") (pin "VCC") (pinfunction "VCC_VCC") (pintype "power_in"))
      (node (ref "D400") (pin "VCC") (pinfunction "VCC_VCC") (pintype "power_in"))
      (node (ref "D401") (pin "VCC") (pinfunction "VCC_VCC") (pintype "power_in"))
      (node (ref "D402") (pin "VCC") (pinfunction "VCC_VCC") (pintype "power_in"))
      (node (ref "D403") (pin "VCC") (pinfunction "VCC_VCC") (pintype "power_in"))
      (node (ref "D404") (pin "VCC") (pinfunction "VCC_VCC") (pintype "power_in"))
      (node (ref "D405") (pin "VCC") (pinfunction "VCC_VCC") (pintype "power_in"))
      (node (ref "D41") (pin "VCC") (pinfunction "VCC_VCC") (pintype "power_in"))
      (node (ref "D42") (pin "VCC") (pinfunction "VCC_VCC") (pintype "power_in"))
      (node (ref "D43") (pin "VCC") (pinfunction "VCC_VCC") (pintype "power_in"))
      (node (ref "D44") (pin "VCC") (pinfunction "VCC_VCC") (pintype "power_in"))
      (node (ref "D45") (pin "VCC") (pinfunction "VCC_VCC") (pintype "power_in"))
      (node (ref "D46") (pin "VCC") (pinfunction "VCC_VCC") (pintype "power_in"))
      (node (ref "D47") (pin "VCC") (pinfunction "VCC_VCC") (pintype "power_in"))
      (node (ref "D48") (pin "VCC") (pinfunction "VCC_VCC") (pintype "power_in"))
      (node (ref "D49") (pin "VCC") (pinfunction "VCC_VCC") (pintype "power_in"))
      (node (ref "D5") (pin "VCC") (pinfunction "VCC_VCC") (pintype "power_in"))
      (node (ref "D50") (pin "VCC") (pinfunction "VCC_VCC") (pintype "power_in"))
      (node (ref "D51") (pin "VCC") (pinfunction "VCC_VCC") (pintype "power_in"))
      (node (ref "D52") (pin "VCC") (pinfunction "VCC_VCC") (pintype "power_in"))
      (node (ref "D53") (pin "VCC") (pinfunction "VCC_VCC") (pintype "power_in"))
      (node (ref "D54") (pin "VCC") (pinfunction "VCC_VCC") (pintype "power_in"))
      (node (ref "D55") (pin "VCC") (pinfunction "VCC_VCC") (pintype "power_in"))
      (node (ref "D56") (pin "VCC") (pinfunction "VCC_VCC") (pintype "power_in"))
      (node (ref "D57") (pin "VCC") (pinfunction "VCC_VCC") (pintype "power_in"))
      (node (ref "D58") (pin "VCC") (pinfunction "VCC_VCC") (pintype "power_in"))
      (node (ref "D59") (pin "VCC") (pinfunction "VCC_VCC") (pintype "power_in"))
      (node (ref "D6") (pin "VCC") (pinfunction "VCC_VCC") (pintype "power_in"))
      (node (ref "D60") (pin "VCC") (pinfunction "VCC_VCC") (pintype "power_in"))
      (node (ref "D61") (pin "VCC") (pinfunction "VCC_VCC") (pintype "power_in"))
      (node (ref "D62") (pin "VCC") (pinfunction "VCC_VCC") (pintype "power_in"))
      (node (ref "D63") (pin "VCC") (pinfunction "VCC_VCC") (pintype "power_in"))
      (node (ref "D64") (pin "VCC") (pinfunction "VCC_VCC") (pintype "power_in"))
      (node (ref "D65") (pin "VCC") (pinfunction "VCC_VCC") (pintype "power_in"))
      (node (ref "D66") (pin "VCC") (pinfunction "VCC_VCC") (pintype "power_in"))
      (node (ref "D67") (pin "VCC") (pinfunction "VCC_VCC") (pintype "power_in"))
      (node (ref "D68") (pin "VCC") (pinfunction "VCC_VCC") (pintype "power_in"))
      (node (ref "D69") (pin "VCC") (pinfunction "VCC_VCC") (pintype "power_in"))
      (node (ref "D7") (pin "VCC") (pinfunction "VCC_VCC") (pintype "power_in"))
      (node (ref "D70") (pin "VCC") (pinfunction "VCC_VCC") (pintype "power_in"))
      (node (ref "D71") (pin "VCC") (pinfunction "VCC_VCC") (pintype "power_in"))
      (node (ref "D72") (pin "VCC") (pinfunction "VCC_VCC") (pintype "power_in"))
      (node (ref "D73") (pin "VCC") (pinfunction "VCC_VCC") (pintype "power_in"))
      (node (ref "D74") (pin "VCC") (pinfunction "VCC_VCC") (pintype "power_in"))
      (node (ref "D75") (pin "VCC") (pinfunction "VCC_VCC") (pintype "power_in"))
      (node (ref "D76") (pin "VCC") (pinfunction "VCC_VCC") (pintype "power_in"))
      (node (ref "D77") (pin "VCC") (pinfunction "VCC_VCC") (pintype "power_in"))
      (node (ref "D78") (pin "VCC") (pinfunction "VCC_VCC") (pintype "power_in"))
      (node (ref "D79") (pin "VCC") (pinfunction "VCC_VCC") (pintype "power_in"))
      (node (ref "D8") (pin "VCC") (pinfunction "VCC_VCC") (pintype "power_in"))
      (node (ref "D80") (pin "VCC") (pinfunction "VCC_VCC") (pintype "power_in"))
      (node (ref "D81") (pin "VCC") (pinfunction "VCC_VCC") (pintype "power_in"))
      (node (ref "D82") (pin "VCC") (pinfunction "VCC_VCC") (pintype "power_in"))
      (node (ref "D83") (pin "VCC") (pinfunction "VCC_VCC") (pintype "power_in"))
      (node (ref "D84") (pin "VCC") (pinfunction "VCC_VCC") (pintype "power_in"))
      (node (ref "D85") (pin "VCC") (pinfunction "VCC_VCC") (pintype "power_in"))
      (node (ref "D86") (pin "VCC") (pinfunction "VCC_VCC") (pintype "power_in"))
      (node (ref "D87") (pin "VCC") (pinfunction "VCC_VCC") (pintype "power_in"))
      (node (ref "D88") (pin "VCC") (pinfunction "VCC_VCC") (pintype "power_in"))
      (node (ref "D89") (pin "VCC") (pinfunction "VCC_VCC") (pintype "power_in"))
      (node (ref "D9") (pin "VCC") (pinfunction "VCC_VCC") (pintype "power_in"))
      (node (ref "D90") (pin "VCC") (pinfunction "VCC_VCC") (pintype "power_in"))
      (node (ref "D91") (pin "VCC") (pinfunction "VCC_VCC") (pintype "power_in"))
      (node (ref "D92") (pin "VCC") (pinfunction "VCC_VCC") (pintype "power_in"))
      (node (ref "D93") (pin "VCC") (pinfunction "VCC_VCC") (pintype "power_in"))
      (node (ref "D94") (pin "VCC") (pinfunction "VCC_VCC") (pintype "power_in"))
      (node (ref "D95") (pin "VCC") (pinfunction "VCC_VCC") (pintype "power_in"))
      (node (ref "D96") (pin "VCC") (pinfunction "VCC_VCC") (pintype "power_in"))
      (node (ref "D97") (pin "VCC") (pinfunction "VCC_VCC") (pintype "power_in"))
      (node (ref "D98") (pin "VCC") (pinfunction "VCC_VCC") (pintype "power_in"))
      (node (ref "D99") (pin "VCC") (pinfunction "VCC_VCC") (pintype "power_in"))
      (node (ref "JP1") (pin "1") (pinfunction "1_1") (pintype "passive"))
      (node (ref "JP1") (pin "2") (pinfunction "2_2") (pintype "passive"))
      (node (ref "JP1") (pin "3") (pinfunction "3_3") (pintype "passive"))
      (node (ref "JP2") (pin "1") (pinfunction "1_1") (pintype "passive"))
      (node (ref "JP2") (pin "2") (pinfunction "2_2") (pintype "passive"))
      (node (ref "JP2") (pin "3") (pinfunction "3_3") (pintype "passive"))
      (node (ref "Z1") (pin "1") (pinfunction "1_1") (pintype "passive"))
    )
    (net (code "409") (name "unconnected-(D1-PadDO)") (class "Default")
      (node (ref "D1") (pin "DO") (pinfunction "DO_DO") (pintype "output"))
    )
    (net (code "410") (name "unconnected-(JP2-Pad4)") (class "Default")
      (node (ref "JP2") (pin "4") (pinfunction "4_4") (pintype "passive"))
    )
  )
)
